# BeagleBone_Blue_3D.net
KiCad netlist of a schematic drawn in EAGLE
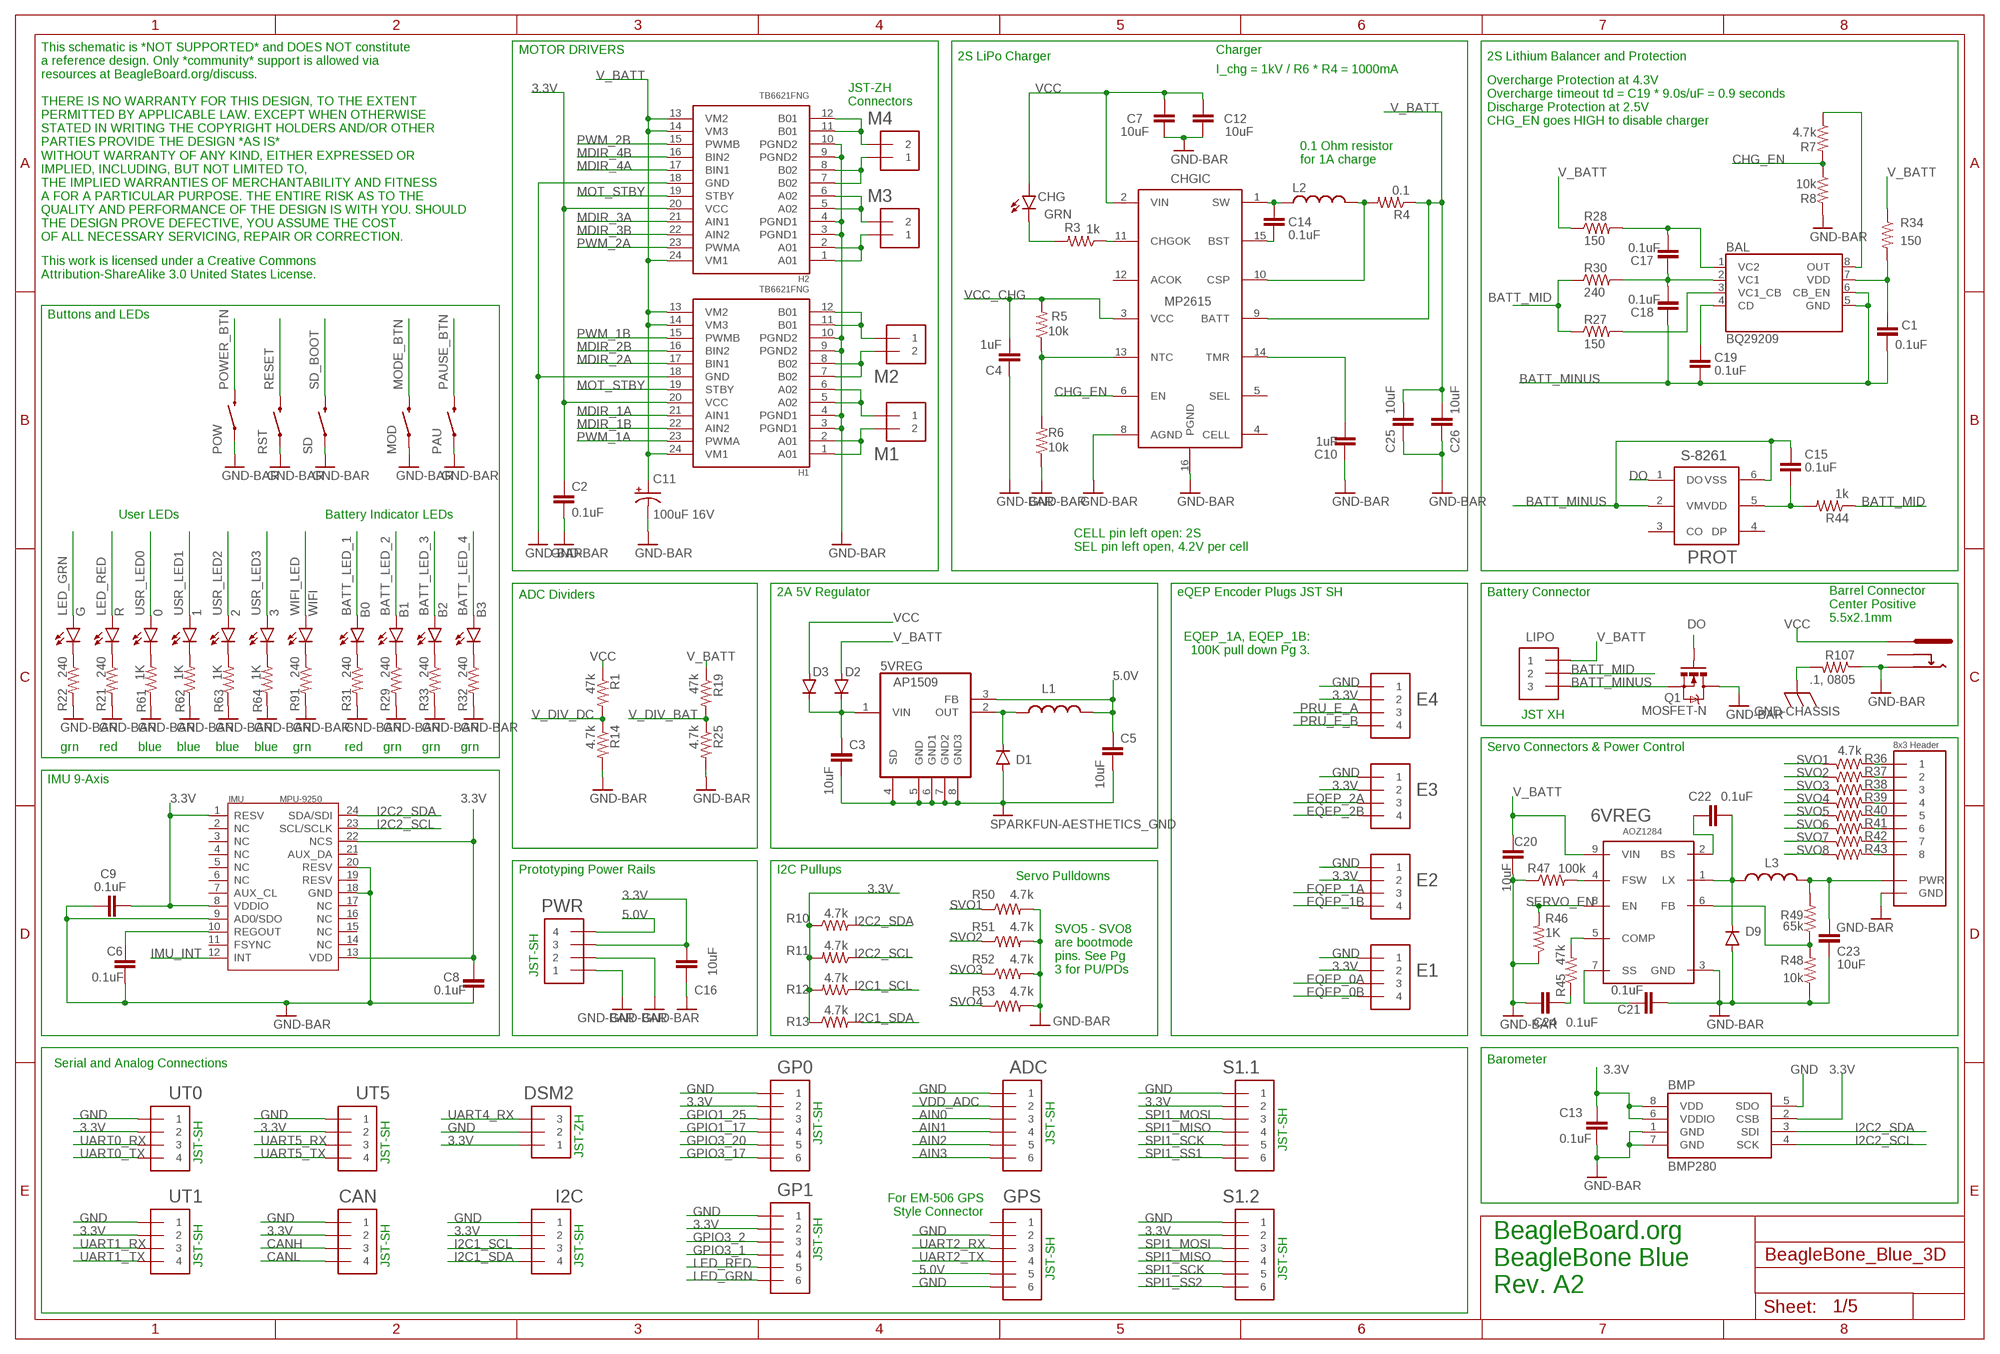
[diagram p0: schematic, sheet 1]
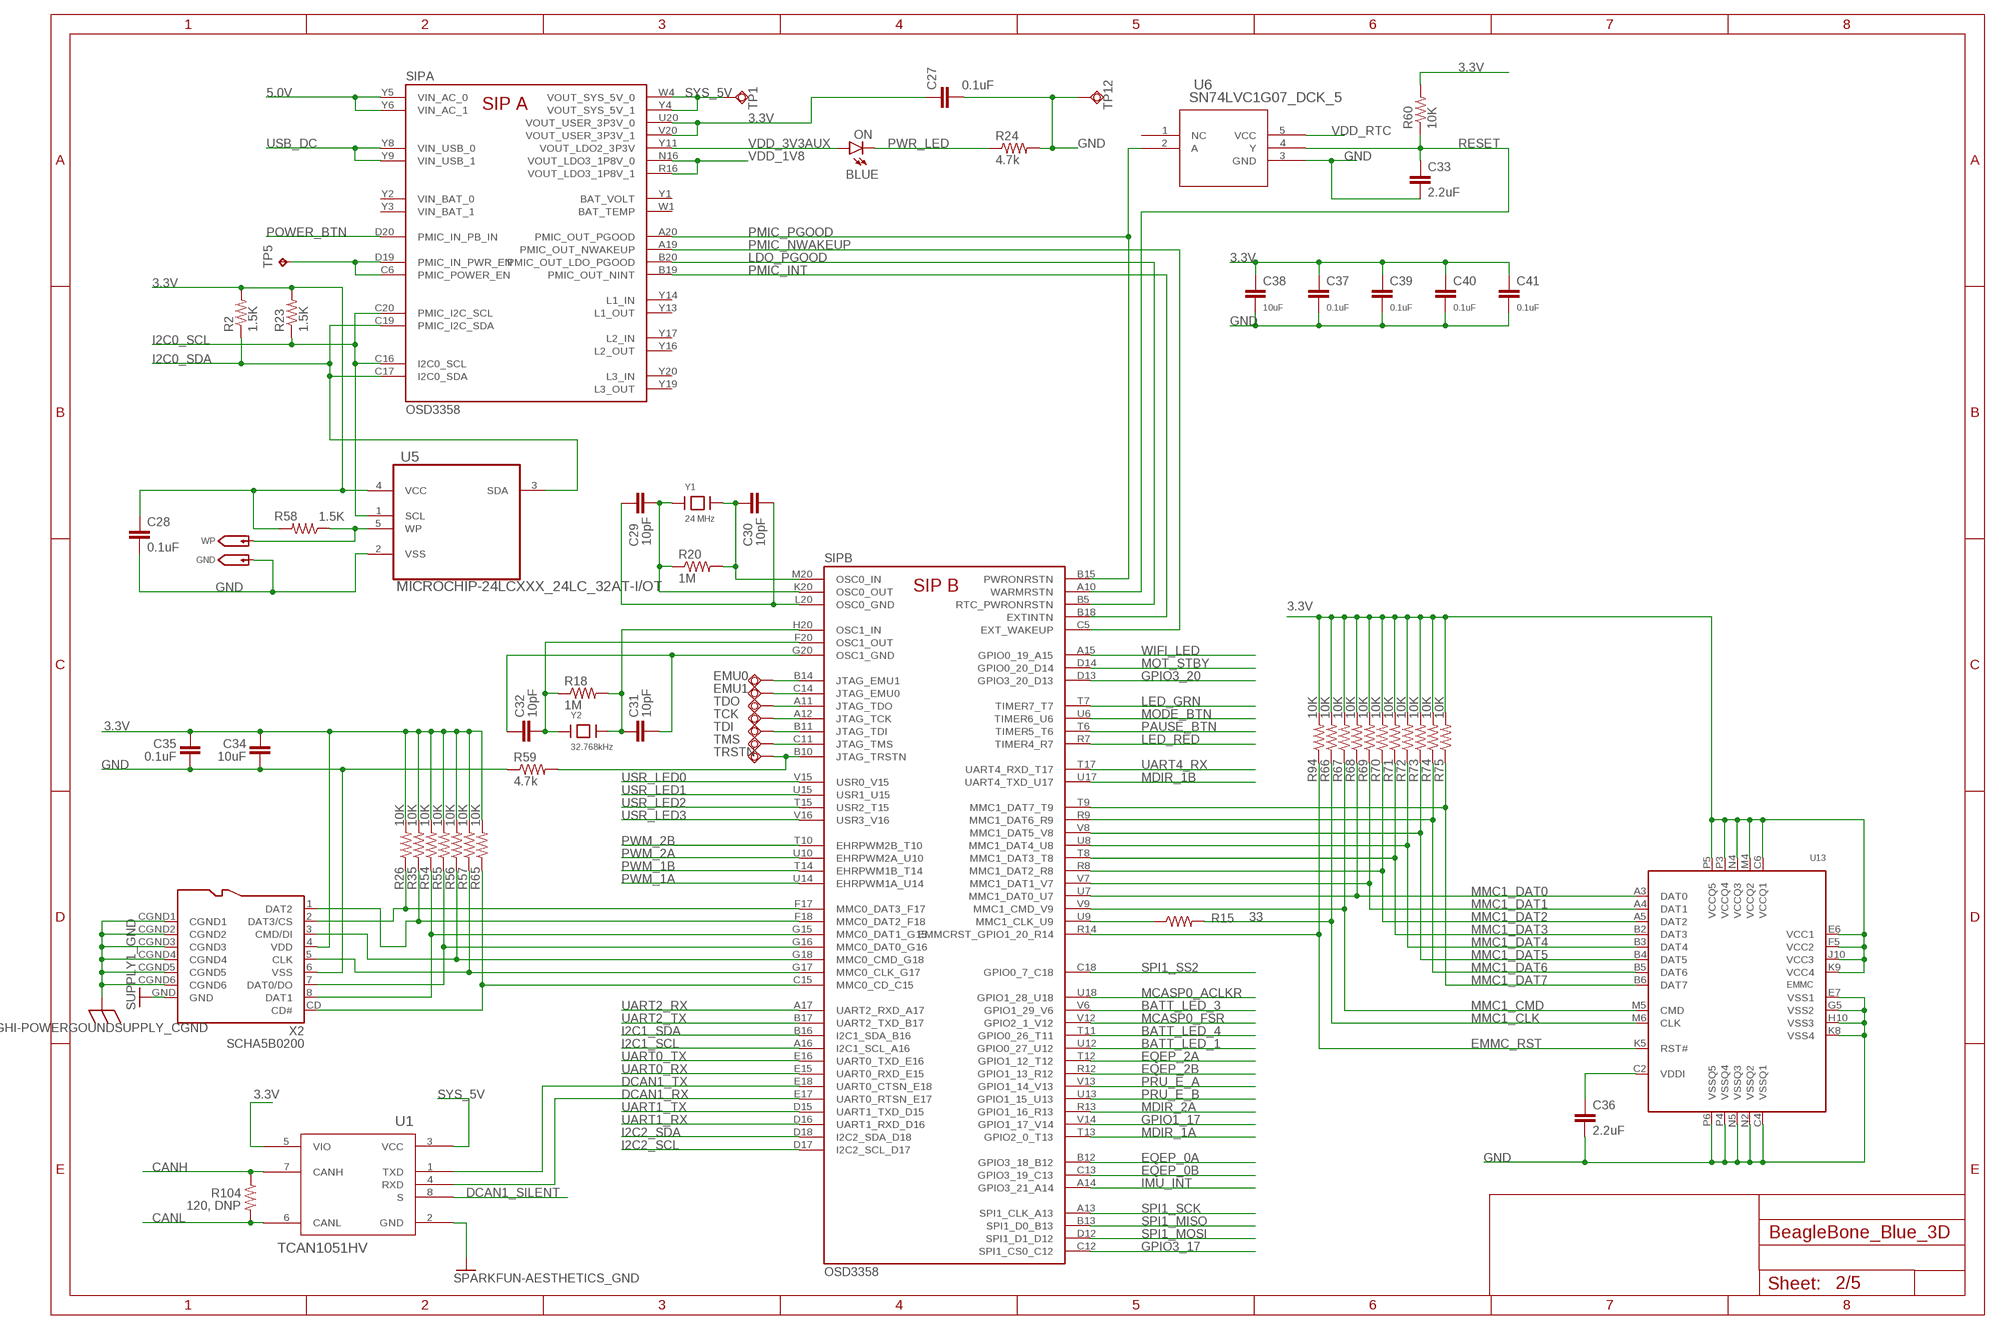
[diagram p1: schematic, sheet 2]
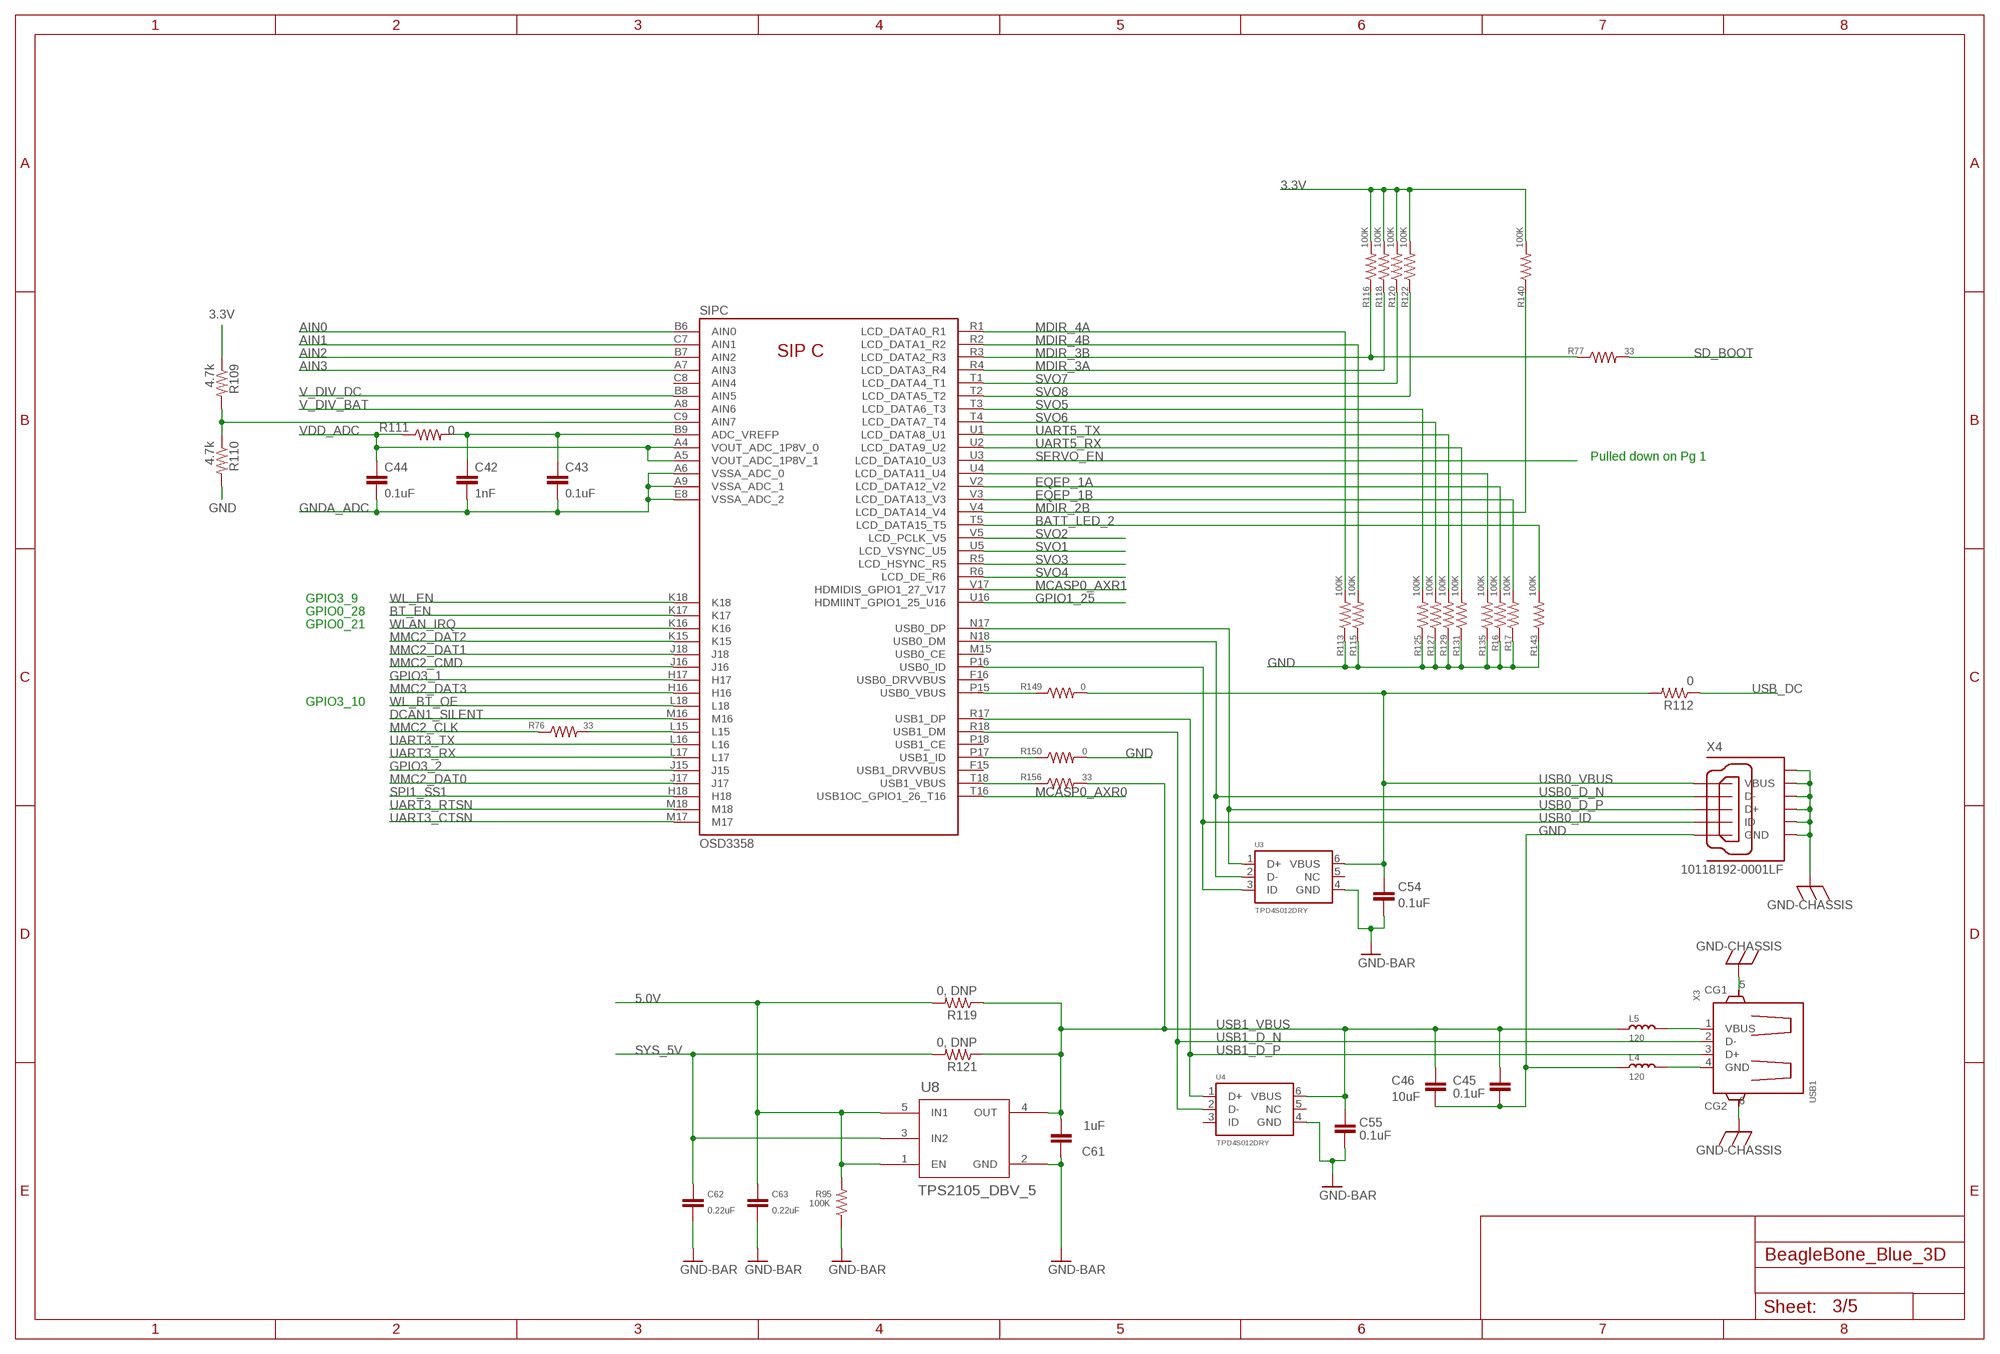
[diagram p2: schematic, sheet 3]
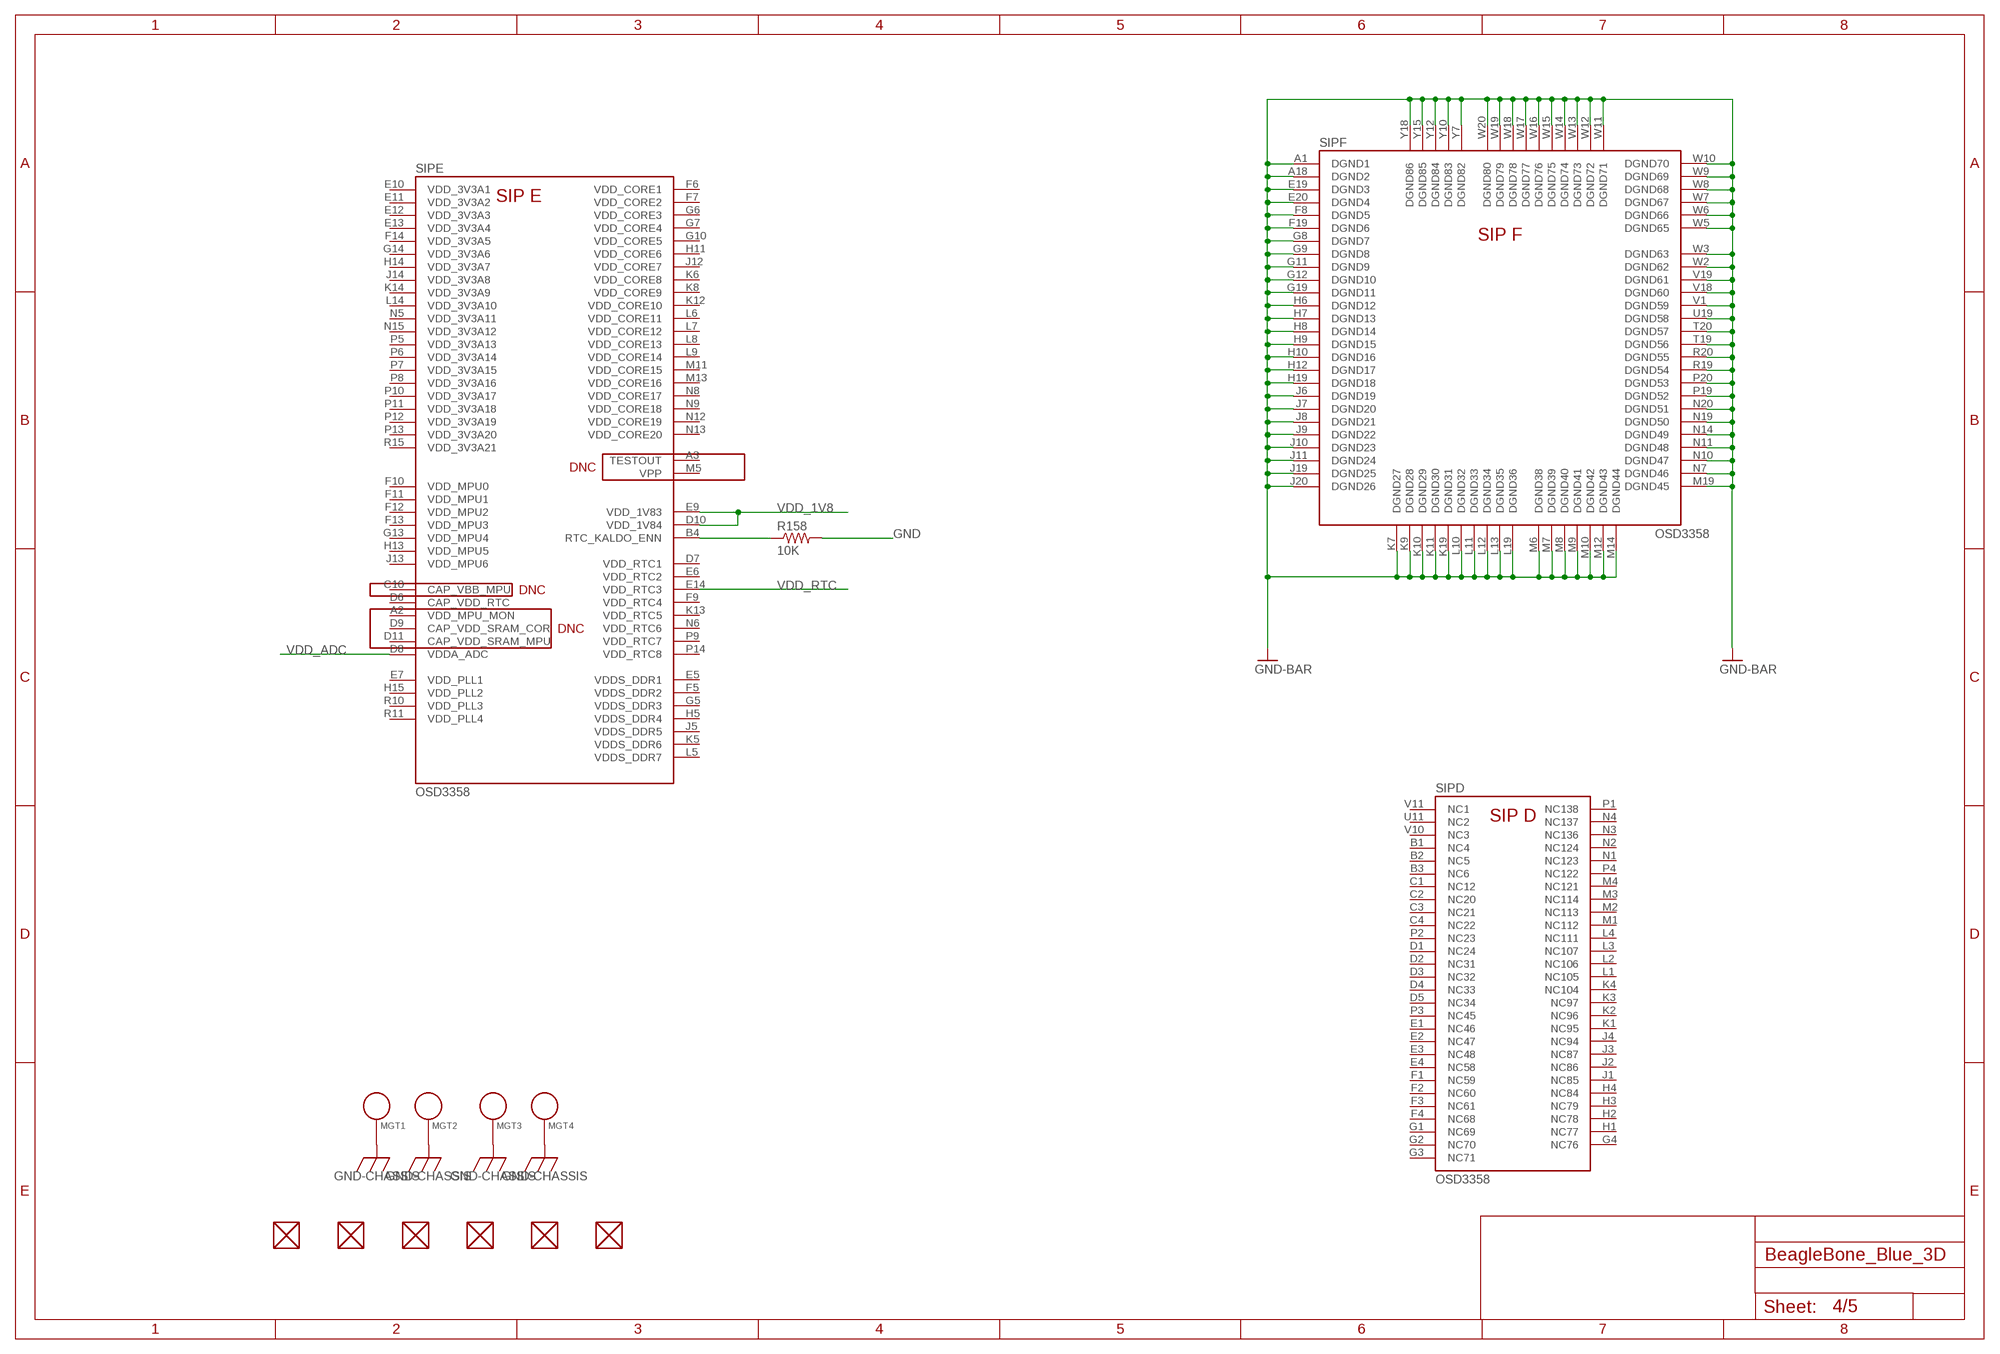
[diagram p3: schematic, sheet 4]
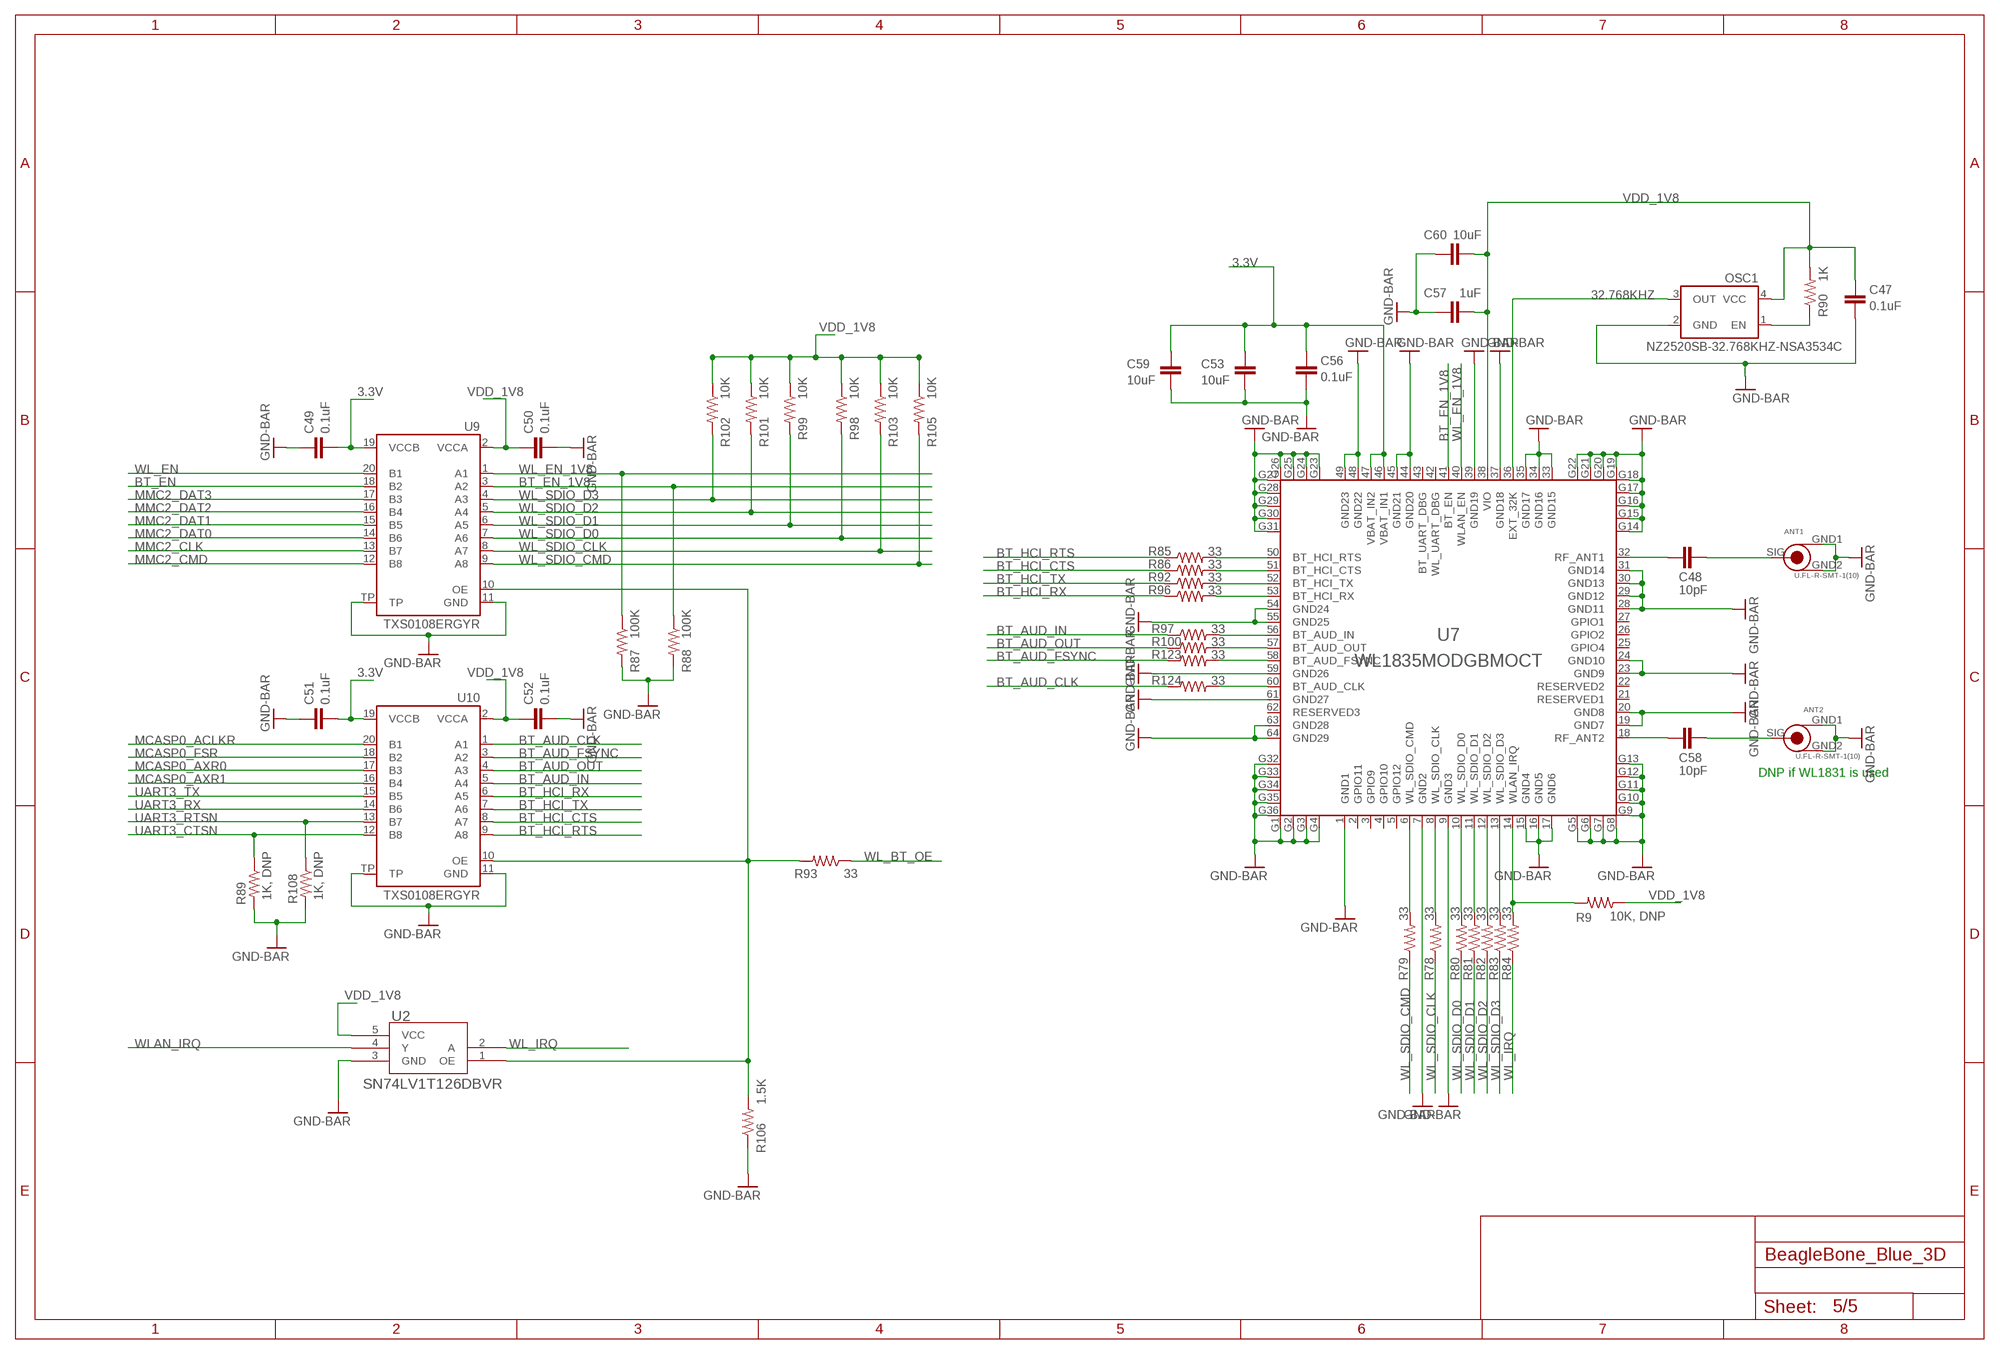
[diagram p4: schematic, sheet 5]

(export (version "E")
  (design (tool "Eeschema 10.0.6"))
  (components
    (comp (ref "FUD1")
      (value "FIDUCIAL")
      (footprint "eagle-import:GHI_FIDUCIAL_40MIL")
      (libsource (lib "eagle-import") (part "FIDUCIAL"))
    )
    (comp (ref "FUD2")
      (value "FIDUCIAL")
      (footprint "eagle-import:GHI_FIDUCIAL_40MIL")
      (libsource (lib "eagle-import") (part "FIDUCIAL"))
    )
    (comp (ref "FUD3")
      (value "FIDUCIAL")
      (footprint "eagle-import:GHI_FIDUCIAL_40MIL")
      (libsource (lib "eagle-import") (part "FIDUCIAL"))
    )
    (comp (ref "FUD4")
      (value "FIDUCIAL")
      (footprint "eagle-import:GHI_FIDUCIAL_40MIL")
      (libsource (lib "eagle-import") (part "FIDUCIAL"))
    )
    (comp (ref "FUD5")
      (value "FIDUCIAL")
      (footprint "eagle-import:GHI_FIDUCIAL_40MIL")
      (libsource (lib "eagle-import") (part "FIDUCIAL"))
    )
    (comp (ref "FUD6")
      (value "FIDUCIAL")
      (footprint "eagle-import:GHI_FIDUCIAL_40MIL")
      (libsource (lib "eagle-import") (part "FIDUCIAL"))
    )
    (comp (ref "MGT1")
      (value "MOUNTING_HOLE")
      (footprint "eagle-import:BEAGLEBONEBLACK_MOUNTING_HOLE")
      (libsource (lib "eagle-import") (part "MOUNTING_HOLE"))
    )
    (comp (ref "MGT2")
      (value "MOUNTING_HOLE")
      (footprint "eagle-import:BEAGLEBONEBLACK_MOUNTING_HOLE")
      (libsource (lib "eagle-import") (part "MOUNTING_HOLE"))
    )
    (comp (ref "MGT3")
      (value "MOUNTING_HOLE")
      (footprint "eagle-import:BEAGLEBONEBLACK_MOUNTING_HOLE")
      (libsource (lib "eagle-import") (part "MOUNTING_HOLE"))
    )
    (comp (ref "MGT4")
      (value "MOUNTING_HOLE")
      (footprint "eagle-import:BEAGLEBONEBLACK_MOUNTING_HOLE")
      (libsource (lib "eagle-import") (part "MOUNTING_HOLE"))
    )
    (comp (ref "R158")
      (value "10K")
      (footprint "eagle-import:0402-RES")
      (libsource (lib "eagle-import") (part "RESISTOR0402"))
    )
    (comp (ref "SIP")
      (value "OSD3358")
      (footprint "eagle-import:OSD3358")
      (libsource (lib "eagle-import") (part "OSD3358"))
    )
    (comp (ref "ANT1")
      (value "U.FL-R-SMT-1(10)")
      (footprint "eagle-import:GHI-CONNECTORS_U.FL-R-SMT-1")
      (libsource (lib "eagle-import") (part "U.FL-R-SMT-1"))
    )
    (comp (ref "ANT2")
      (value "U.FL-R-SMT-1(10)")
      (footprint "eagle-import:GHI-CONNECTORS_U.FL-R-SMT-1")
      (libsource (lib "eagle-import") (part "U.FL-R-SMT-1"))
    )
    (comp (ref "C47")
      (value "0.1uF")
      (footprint "eagle-import:0402-CAP")
      (libsource (lib "eagle-import") (part "CAPACITOR-N0402"))
    )
    (comp (ref "C48")
      (value "10pF")
      (footprint "eagle-import:0402-CAP")
      (libsource (lib "eagle-import") (part "CAPACITOR-N0402"))
    )
    (comp (ref "C49")
      (value "0.1uF")
      (footprint "eagle-import:0402-CAP")
      (libsource (lib "eagle-import") (part "CAPACITOR-N0402"))
    )
    (comp (ref "C50")
      (value "0.1uF")
      (footprint "eagle-import:0402-CAP")
      (libsource (lib "eagle-import") (part "CAPACITOR-N0402"))
    )
    (comp (ref "C51")
      (value "0.1uF")
      (footprint "eagle-import:0402-CAP")
      (libsource (lib "eagle-import") (part "CAPACITOR-N0402"))
    )
    (comp (ref "C52")
      (value "0.1uF")
      (footprint "eagle-import:0402-CAP")
      (libsource (lib "eagle-import") (part "CAPACITOR-N0402"))
    )
    (comp (ref "C53")
      (value "10uF")
      (footprint "eagle-import:0805")
      (libsource (lib "eagle-import") (part "CAPACITOR-N0805"))
    )
    (comp (ref "C56")
      (value "0.1uF")
      (footprint "eagle-import:0402-CAP")
      (libsource (lib "eagle-import") (part "CAPACITOR-N0402"))
    )
    (comp (ref "C57")
      (value "1uF")
      (footprint "eagle-import:0402-CAP")
      (libsource (lib "eagle-import") (part "CAPACITOR-N0402"))
    )
    (comp (ref "C58")
      (value "10pF")
      (footprint "eagle-import:0402-CAP")
      (libsource (lib "eagle-import") (part "CAPACITOR-N0402"))
    )
    (comp (ref "C59")
      (value "10uF")
      (footprint "eagle-import:0805")
      (libsource (lib "eagle-import") (part "CAPACITOR-N0805"))
    )
    (comp (ref "C60")
      (value "10uF")
      (footprint "eagle-import:0805")
      (libsource (lib "eagle-import") (part "CAPACITOR-N0805"))
    )
    (comp (ref "OSC1")
      (value "NZ2520SB-32.768KHZ-NSA3534C")
      (footprint "eagle-import:NZ2520S")
      (libsource (lib "eagle-import") (part "OSCILLATOR"))
    )
    (comp (ref "R9")
      (value "10K, DNP")
      (footprint "eagle-import:0402-RES")
      (libsource (lib "eagle-import") (part "RESISTOR0402"))
    )
    (comp (ref "R78")
      (value "33")
      (footprint "eagle-import:0402-RES")
      (libsource (lib "eagle-import") (part "RESISTOR0402"))
    )
    (comp (ref "R79")
      (value "33")
      (footprint "eagle-import:0402-RES")
      (libsource (lib "eagle-import") (part "RESISTOR0402"))
    )
    (comp (ref "R80")
      (value "33")
      (footprint "eagle-import:0402-RES")
      (libsource (lib "eagle-import") (part "RESISTOR0402"))
    )
    (comp (ref "R81")
      (value "33")
      (footprint "eagle-import:0402-RES")
      (libsource (lib "eagle-import") (part "RESISTOR0402"))
    )
    (comp (ref "R82")
      (value "33")
      (footprint "eagle-import:0402-RES")
      (libsource (lib "eagle-import") (part "RESISTOR0402"))
    )
    (comp (ref "R83")
      (value "33")
      (footprint "eagle-import:0402-RES")
      (libsource (lib "eagle-import") (part "RESISTOR0402"))
    )
    (comp (ref "R84")
      (value "33")
      (footprint "eagle-import:0402-RES")
      (libsource (lib "eagle-import") (part "RESISTOR0402"))
    )
    (comp (ref "R85")
      (value "33")
      (footprint "eagle-import:0402-RES")
      (libsource (lib "eagle-import") (part "RESISTOR0402"))
    )
    (comp (ref "R86")
      (value "33")
      (footprint "eagle-import:0402-RES")
      (libsource (lib "eagle-import") (part "RESISTOR0402"))
    )
    (comp (ref "R87")
      (value "100K")
      (footprint "eagle-import:0402-RES")
      (libsource (lib "eagle-import") (part "RESISTOR0402"))
    )
    (comp (ref "R88")
      (value "100K")
      (footprint "eagle-import:0402-RES")
      (libsource (lib "eagle-import") (part "RESISTOR0402"))
    )
    (comp (ref "R89")
      (value "1K, DNP")
      (footprint "eagle-import:0402-RES")
      (libsource (lib "eagle-import") (part "RESISTOR0402"))
    )
    (comp (ref "R90")
      (value "1K")
      (footprint "eagle-import:0402-RES")
      (libsource (lib "eagle-import") (part "RESISTOR0402"))
    )
    (comp (ref "R92")
      (value "33")
      (footprint "eagle-import:0402-RES")
      (libsource (lib "eagle-import") (part "RESISTOR0402"))
    )
    (comp (ref "R93")
      (value "33")
      (footprint "eagle-import:0402-RES")
      (libsource (lib "eagle-import") (part "RESISTOR0402"))
    )
    (comp (ref "R96")
      (value "33")
      (footprint "eagle-import:0402-RES")
      (libsource (lib "eagle-import") (part "RESISTOR0402"))
    )
    (comp (ref "R97")
      (value "33")
      (footprint "eagle-import:0402-RES")
      (libsource (lib "eagle-import") (part "RESISTOR0402"))
    )
    (comp (ref "R98")
      (value "10K")
      (footprint "eagle-import:0402-RES")
      (libsource (lib "eagle-import") (part "RESISTOR0402"))
    )
    (comp (ref "R99")
      (value "10K")
      (footprint "eagle-import:0402-RES")
      (libsource (lib "eagle-import") (part "RESISTOR0402"))
    )
    (comp (ref "R100")
      (value "33")
      (footprint "eagle-import:0402-RES")
      (libsource (lib "eagle-import") (part "RESISTOR0402"))
    )
    (comp (ref "R101")
      (value "10K")
      (footprint "eagle-import:0402-RES")
      (libsource (lib "eagle-import") (part "RESISTOR0402"))
    )
    (comp (ref "R102")
      (value "10K")
      (footprint "eagle-import:0402-RES")
      (libsource (lib "eagle-import") (part "RESISTOR0402"))
    )
    (comp (ref "R103")
      (value "10K")
      (footprint "eagle-import:0402-RES")
      (libsource (lib "eagle-import") (part "RESISTOR0402"))
    )
    (comp (ref "R105")
      (value "10K")
      (footprint "eagle-import:0402-RES")
      (libsource (lib "eagle-import") (part "RESISTOR0402"))
    )
    (comp (ref "R106")
      (value "1.5K")
      (footprint "eagle-import:0402-RES")
      (libsource (lib "eagle-import") (part "RESISTOR0402"))
    )
    (comp (ref "R108")
      (value "1K, DNP")
      (footprint "eagle-import:0402-RES")
      (libsource (lib "eagle-import") (part "RESISTOR0402"))
    )
    (comp (ref "R123")
      (value "33")
      (footprint "eagle-import:0402-RES")
      (libsource (lib "eagle-import") (part "RESISTOR0402"))
    )
    (comp (ref "R124")
      (value "33")
      (footprint "eagle-import:0402-RES")
      (libsource (lib "eagle-import") (part "RESISTOR0402"))
    )
    (comp (ref "U2")
      (value "SN74LV1T126DBVR")
      (footprint "eagle-import:SOT95P280X145-5")
      (libsource (lib "eagle-import") (part "SN74LV1T126DBVR"))
    )
    (comp (ref "U7")
      (value "WL1835MODGBMOCT")
      (footprint "eagle-import:MOC-100(TI)")
      (libsource (lib "eagle-import") (part "WL1835MOD"))
    )
    (comp (ref "U9")
      (value "TXS0108ERGYR")
      (footprint "eagle-import:R-PVQFN-N20(TI)")
      (libsource (lib "eagle-import") (part "TXS0108ERGYR"))
    )
    (comp (ref "U10")
      (value "TXS0108ERGYR")
      (footprint "eagle-import:R-PVQFN-N20(TI)")
      (libsource (lib "eagle-import") (part "TXS0108ERGYR"))
    )
    (comp (ref "C42")
      (value "1nF")
      (footprint "eagle-import:0402-CAP")
      (libsource (lib "eagle-import") (part "CAPACITOR-N0402"))
    )
    (comp (ref "C43")
      (value "0.1uF")
      (footprint "eagle-import:0402-CAP")
      (libsource (lib "eagle-import") (part "CAPACITOR-N0402"))
    )
    (comp (ref "C44")
      (value "0.1uF")
      (footprint "eagle-import:0402-CAP")
      (libsource (lib "eagle-import") (part "CAPACITOR-N0402"))
    )
    (comp (ref "C45")
      (value "0.1uF")
      (footprint "eagle-import:0402-CAP")
      (libsource (lib "eagle-import") (part "CAPACITOR-N0402"))
    )
    (comp (ref "C46")
      (value "10uF")
      (footprint "eagle-import:0805")
      (libsource (lib "eagle-import") (part "CAPACITOR-N0805"))
    )
    (comp (ref "C54")
      (value "0.1uF")
      (footprint "eagle-import:0402-CAP")
      (libsource (lib "eagle-import") (part "CAPACITOR-N0402"))
    )
    (comp (ref "C55")
      (value "0.1uF")
      (footprint "eagle-import:0402-CAP")
      (libsource (lib "eagle-import") (part "CAPACITOR-N0402"))
    )
    (comp (ref "C61")
      (value "1uF")
      (footprint "eagle-import:0402-CAP")
      (libsource (lib "eagle-import") (part "CAPACITOR-N0402"))
    )
    (comp (ref "C62")
      (value "0.22uF")
      (footprint "eagle-import:0402-CAP")
      (libsource (lib "eagle-import") (part "CAPACITOR-N0402"))
    )
    (comp (ref "C63")
      (value "0.22uF")
      (footprint "eagle-import:0402-CAP")
      (libsource (lib "eagle-import") (part "CAPACITOR-N0402"))
    )
    (comp (ref "L4")
      (value "120")
      (footprint "eagle-import:INDUCTOR_L0603")
      (libsource (lib "eagle-import") (part "INDUCTOR/FERRITE-BEAD0603"))
    )
    (comp (ref "L5")
      (value "120")
      (footprint "eagle-import:INDUCTOR_L0603")
      (libsource (lib "eagle-import") (part "INDUCTOR/FERRITE-BEAD0603"))
    )
    (comp (ref "R16")
      (value "100K")
      (footprint "eagle-import:0402-RES")
      (libsource (lib "eagle-import") (part "RESISTOR0402"))
    )
    (comp (ref "R17")
      (value "100K")
      (footprint "eagle-import:0402-RES")
      (libsource (lib "eagle-import") (part "RESISTOR0402"))
    )
    (comp (ref "R76")
      (value "33")
      (footprint "eagle-import:0402-RES")
      (libsource (lib "eagle-import") (part "RESISTOR0402"))
    )
    (comp (ref "R77")
      (value "33")
      (footprint "eagle-import:0402-RES")
      (libsource (lib "eagle-import") (part "RESISTOR0402"))
    )
    (comp (ref "R95")
      (value "100K")
      (footprint "eagle-import:0402-RES")
      (libsource (lib "eagle-import") (part "RESISTOR0402"))
    )
    (comp (ref "R109")
      (value "4.7k")
      (footprint "eagle-import:0402-RES")
      (libsource (lib "eagle-import") (part "RESISTOR0402"))
    )
    (comp (ref "R110")
      (value "4.7k")
      (footprint "eagle-import:0402-RES")
      (libsource (lib "eagle-import") (part "RESISTOR0402"))
    )
    (comp (ref "R111")
      (value "0")
      (footprint "eagle-import:0402-RES")
      (libsource (lib "eagle-import") (part "RESISTOR0402"))
    )
    (comp (ref "R112")
      (value "0")
      (footprint "eagle-import:R0603")
      (libsource (lib "eagle-import") (part "RESISTOR0603"))
    )
    (comp (ref "R113")
      (value "100K")
      (footprint "eagle-import:0402-RES")
      (libsource (lib "eagle-import") (part "RESISTOR0402"))
    )
    (comp (ref "R115")
      (value "100K")
      (footprint "eagle-import:0402-RES")
      (libsource (lib "eagle-import") (part "RESISTOR0402"))
    )
    (comp (ref "R116")
      (value "100K")
      (footprint "eagle-import:0402-RES")
      (libsource (lib "eagle-import") (part "RESISTOR0402"))
    )
    (comp (ref "R118")
      (value "100K")
      (footprint "eagle-import:0402-RES")
      (libsource (lib "eagle-import") (part "RESISTOR0402"))
    )
    (comp (ref "R119")
      (value "0, DNP")
      (footprint "eagle-import:R0603")
      (libsource (lib "eagle-import") (part "RESISTOR0603"))
    )
    (comp (ref "R120")
      (value "100K")
      (footprint "eagle-import:0402-RES")
      (libsource (lib "eagle-import") (part "RESISTOR0402"))
    )
    (comp (ref "R121")
      (value "0, DNP")
      (footprint "eagle-import:R0603")
      (libsource (lib "eagle-import") (part "RESISTOR0603"))
    )
    (comp (ref "R122")
      (value "100K")
      (footprint "eagle-import:0402-RES")
      (libsource (lib "eagle-import") (part "RESISTOR0402"))
    )
    (comp (ref "R125")
      (value "100K")
      (footprint "eagle-import:0402-RES")
      (libsource (lib "eagle-import") (part "RESISTOR0402"))
    )
    (comp (ref "R127")
      (value "100K")
      (footprint "eagle-import:0402-RES")
      (libsource (lib "eagle-import") (part "RESISTOR0402"))
    )
    (comp (ref "R129")
      (value "100K")
      (footprint "eagle-import:0402-RES")
      (libsource (lib "eagle-import") (part "RESISTOR0402"))
    )
    (comp (ref "R131")
      (value "100K")
      (footprint "eagle-import:0402-RES")
      (libsource (lib "eagle-import") (part "RESISTOR0402"))
    )
    (comp (ref "R135")
      (value "100K")
      (footprint "eagle-import:0402-RES")
      (libsource (lib "eagle-import") (part "RESISTOR0402"))
    )
    (comp (ref "R140")
      (value "100K")
      (footprint "eagle-import:0402-RES")
      (libsource (lib "eagle-import") (part "RESISTOR0402"))
    )
    (comp (ref "R143")
      (value "100K")
      (footprint "eagle-import:0402-RES")
      (libsource (lib "eagle-import") (part "RESISTOR0402"))
    )
    (comp (ref "R149")
      (value "0")
      (footprint "eagle-import:0402-RES")
      (libsource (lib "eagle-import") (part "RESISTOR0402"))
    )
    (comp (ref "R150")
      (value "0")
      (footprint "eagle-import:0402-RES")
      (libsource (lib "eagle-import") (part "RESISTOR0402"))
    )
    (comp (ref "R156")
      (value "33")
      (footprint "eagle-import:0402-RES")
      (libsource (lib "eagle-import") (part "RESISTOR0402"))
    )
    (comp (ref "U3")
      (value "TPD4S012DRY")
      (footprint "eagle-import:SON-6(TI)-DRY")
      (libsource (lib "eagle-import") (part "TPD4S012DRYR"))
    )
    (comp (ref "U4")
      (value "TPD4S012DRY")
      (footprint "eagle-import:SON-6(TI)-DRY")
      (libsource (lib "eagle-import") (part "TPD4S012DRYR"))
    )
    (comp (ref "U8")
      (value "TPS2105_DBV_5")
      (footprint "eagle-import:DIODE_DBV5")
      (fields
        (field (name "GENERIC_PART_NUMBER") "TPS2105")
        (field (name "MANUFACTURER") "Texas Instruments")
        (field (name "MANUFACTURER_PART_NUMBER") "tps2105_dbv_5")
      )
      (libsource (lib "eagle-import") (part "TPS2105_DBV_5"))
    )
    (comp (ref "X3")
      (value "USB1")
      (footprint "eagle-import:GHI2_USB_HOST_HORIZONTAL_W_CHASSIS_GND")
      (libsource (lib "eagle-import") (part "USB_HOST_W/CHASSIS_GND"))
    )
    (comp (ref "X4")
      (value "10118192-0001LF")
      (footprint "eagle-import:GHI-CONNECTORS_10118192-0001LF(MICRO-USB-B-AMPHENOL-FCI)")
      (libsource (lib "eagle-import") (part "10118192-0001LF"))
    )
    (comp (ref "C27")
      (value "0.1uF")
      (footprint "eagle-import:0402-CAP")
      (libsource (lib "eagle-import") (part "CAPACITOR-N0402"))
    )
    (comp (ref "C28")
      (value "0.1uF")
      (footprint "eagle-import:0402-CAP")
      (libsource (lib "eagle-import") (part "CAPACITOR-N0402"))
    )
    (comp (ref "C29")
      (value "10pF")
      (footprint "eagle-import:0402-CAP")
      (libsource (lib "eagle-import") (part "CAPACITOR-N0402"))
    )
    (comp (ref "C30")
      (value "10pF")
      (footprint "eagle-import:0402-CAP")
      (libsource (lib "eagle-import") (part "CAPACITOR-N0402"))
    )
    (comp (ref "C31")
      (value "10pF")
      (footprint "eagle-import:0402-CAP")
      (libsource (lib "eagle-import") (part "CAPACITOR-N0402"))
    )
    (comp (ref "C32")
      (value "10pF")
      (footprint "eagle-import:0402-CAP")
      (libsource (lib "eagle-import") (part "CAPACITOR-N0402"))
    )
    (comp (ref "C33")
      (value "2.2uF")
      (footprint "eagle-import:0402-CAP")
      (libsource (lib "eagle-import") (part "CAPACITOR-N0402"))
    )
    (comp (ref "C34")
      (value "10uF")
      (footprint "eagle-import:0805")
      (libsource (lib "eagle-import") (part "CAPACITOR-N0805"))
    )
    (comp (ref "C35")
      (value "0.1uF")
      (footprint "eagle-import:0402-CAP")
      (libsource (lib "eagle-import") (part "CAPACITOR-N0402"))
    )
    (comp (ref "C36")
      (value "2.2uF")
      (footprint "eagle-import:0402-CAP")
      (libsource (lib "eagle-import") (part "CAPACITOR-N0402"))
    )
    (comp (ref "C37")
      (value "0.1uF")
      (footprint "eagle-import:0402-CAP")
      (libsource (lib "eagle-import") (part "CAPACITOR-N0402"))
    )
    (comp (ref "C38")
      (value "10uF")
      (footprint "eagle-import:0805")
      (libsource (lib "eagle-import") (part "CAPACITOR-N0805"))
    )
    (comp (ref "C39")
      (value "0.1uF")
      (footprint "eagle-import:0402-CAP")
      (libsource (lib "eagle-import") (part "CAPACITOR-N0402"))
    )
    (comp (ref "C40")
      (value "0.1uF")
      (footprint "eagle-import:0402-CAP")
      (libsource (lib "eagle-import") (part "CAPACITOR-N0402"))
    )
    (comp (ref "C41")
      (value "0.1uF")
      (footprint "eagle-import:0402-CAP")
      (libsource (lib "eagle-import") (part "CAPACITOR-N0402"))
    )
    (comp (ref "EMU0")
      (value "TESTPAD_TPSQB1,27")
      (footprint "eagle-import:TESTPAD_B1,27")
      (libsource (lib "eagle-import") (part "TESTPAD_TPSQB1,27"))
    )
    (comp (ref "EMU1")
      (value "TESTPAD_TPSQB1,27")
      (footprint "eagle-import:TESTPAD_B1,27")
      (libsource (lib "eagle-import") (part "TESTPAD_TPSQB1,27"))
    )
    (comp (ref "GND")
      (value "TESTPAD/W_HOLE_1X1")
      (footprint "eagle-import:DIODE_GHI2_TESTPAD_W_HOLE_1X1")
      (libsource (lib "eagle-import") (part "TESTPAD/W_HOLE_1X1"))
    )
    (comp (ref "ON")
      (value "BLUE")
      (footprint "eagle-import:BEAGLEBONE_BLUE_BEAGLEBONE_BLUE_LED-0603")
      (libsource (lib "eagle-import") (part "BEAGLEBONE_BLUE_LED0603"))
    )
    (comp (ref "R2")
      (value "1.5K")
      (footprint "eagle-import:0402-RES")
      (libsource (lib "eagle-import") (part "RESISTOR0402"))
    )
    (comp (ref "R15")
      (value "33")
      (footprint "eagle-import:0402-RES")
      (libsource (lib "eagle-import") (part "RESISTOR0402"))
    )
    (comp (ref "R18")
      (value "1M")
      (footprint "eagle-import:0402-RES")
      (libsource (lib "eagle-import") (part "RESISTOR0402"))
    )
    (comp (ref "R20")
      (value "1M")
      (footprint "eagle-import:0402-RES")
      (libsource (lib "eagle-import") (part "RESISTOR0402"))
    )
    (comp (ref "R23")
      (value "1.5K")
      (footprint "eagle-import:0402-RES")
      (libsource (lib "eagle-import") (part "RESISTOR0402"))
    )
    (comp (ref "R24")
      (value "4.7k")
      (footprint "eagle-import:0402-RES")
      (libsource (lib "eagle-import") (part "RESISTOR0402"))
    )
    (comp (ref "R26")
      (value "10K")
      (footprint "eagle-import:0402-RES")
      (libsource (lib "eagle-import") (part "RESISTOR0402"))
    )
    (comp (ref "R35")
      (value "10K")
      (footprint "eagle-import:0402-RES")
      (libsource (lib "eagle-import") (part "RESISTOR0402"))
    )
    (comp (ref "R54")
      (value "10K")
      (footprint "eagle-import:0402-RES")
      (libsource (lib "eagle-import") (part "RESISTOR0402"))
    )
    (comp (ref "R55")
      (value "10K")
      (footprint "eagle-import:0402-RES")
      (libsource (lib "eagle-import") (part "RESISTOR0402"))
    )
    (comp (ref "R56")
      (value "10K")
      (footprint "eagle-import:0402-RES")
      (libsource (lib "eagle-import") (part "RESISTOR0402"))
    )
    (comp (ref "R57")
      (value "10K")
      (footprint "eagle-import:0402-RES")
      (libsource (lib "eagle-import") (part "RESISTOR0402"))
    )
    (comp (ref "R58")
      (value "1.5K")
      (footprint "eagle-import:0402-RES")
      (libsource (lib "eagle-import") (part "RESISTOR0402"))
    )
    (comp (ref "R59")
      (value "4.7k")
      (footprint "eagle-import:0402-RES")
      (libsource (lib "eagle-import") (part "RESISTOR0402"))
    )
    (comp (ref "R60")
      (value "10K")
      (footprint "eagle-import:0402-RES")
      (libsource (lib "eagle-import") (part "RESISTOR0402"))
    )
    (comp (ref "R65")
      (value "10K")
      (footprint "eagle-import:0402-RES")
      (libsource (lib "eagle-import") (part "RESISTOR0402"))
    )
    (comp (ref "R66")
      (value "10K")
      (footprint "eagle-import:0402-RES")
      (libsource (lib "eagle-import") (part "RESISTOR0402"))
    )
    (comp (ref "R67")
      (value "10K")
      (footprint "eagle-import:0402-RES")
      (libsource (lib "eagle-import") (part "RESISTOR0402"))
    )
    (comp (ref "R68")
      (value "10K")
      (footprint "eagle-import:0402-RES")
      (libsource (lib "eagle-import") (part "RESISTOR0402"))
    )
    (comp (ref "R69")
      (value "10K")
      (footprint "eagle-import:0402-RES")
      (libsource (lib "eagle-import") (part "RESISTOR0402"))
    )
    (comp (ref "R70")
      (value "10K")
      (footprint "eagle-import:0402-RES")
      (libsource (lib "eagle-import") (part "RESISTOR0402"))
    )
    (comp (ref "R71")
      (value "10K")
      (footprint "eagle-import:0402-RES")
      (libsource (lib "eagle-import") (part "RESISTOR0402"))
    )
    (comp (ref "R72")
      (value "10K")
      (footprint "eagle-import:0402-RES")
      (libsource (lib "eagle-import") (part "RESISTOR0402"))
    )
    (comp (ref "R73")
      (value "10K")
      (footprint "eagle-import:0402-RES")
      (libsource (lib "eagle-import") (part "RESISTOR0402"))
    )
    (comp (ref "R74")
      (value "10K")
      (footprint "eagle-import:0402-RES")
      (libsource (lib "eagle-import") (part "RESISTOR0402"))
    )
    (comp (ref "R75")
      (value "10K")
      (footprint "eagle-import:0402-RES")
      (libsource (lib "eagle-import") (part "RESISTOR0402"))
    )
    (comp (ref "R94")
      (value "10K")
      (footprint "eagle-import:0402-RES")
      (libsource (lib "eagle-import") (part "RESISTOR0402"))
    )
    (comp (ref "R104")
      (value "120, DNP")
      (footprint "eagle-import:R0603")
      (libsource (lib "eagle-import") (part "RESISTOR0603"))
    )
    (comp (ref "TCK")
      (value "TESTPAD_TPSQB1,27")
      (footprint "eagle-import:TESTPAD_B1,27")
      (libsource (lib "eagle-import") (part "TESTPAD_TPSQB1,27"))
    )
    (comp (ref "TDI")
      (value "TESTPAD_TPSQB1,27")
      (footprint "eagle-import:TESTPAD_B1,27")
      (libsource (lib "eagle-import") (part "TESTPAD_TPSQB1,27"))
    )
    (comp (ref "TDO")
      (value "TESTPAD_TPSQB1,27")
      (footprint "eagle-import:TESTPAD_B1,27")
      (libsource (lib "eagle-import") (part "TESTPAD_TPSQB1,27"))
    )
    (comp (ref "TMS")
      (value "TESTPAD_TPSQB1,27")
      (footprint "eagle-import:TESTPAD_B1,27")
      (libsource (lib "eagle-import") (part "TESTPAD_TPSQB1,27"))
    )
    (comp (ref "TP1")
      (value "TESTPAD_TPSQB1,27")
      (footprint "eagle-import:TESTPAD_B1,27")
      (libsource (lib "eagle-import") (part "TESTPAD_TPSQB1,27"))
    )
    (comp (ref "TP5")
      (value "TPB0,65")
      (footprint "eagle-import:B0,65")
      (libsource (lib "eagle-import") (part "TPB0,65"))
    )
    (comp (ref "TP12")
      (value "TESTPAD_TPSQB1,27")
      (footprint "eagle-import:TESTPAD_B1,27")
      (libsource (lib "eagle-import") (part "TESTPAD_TPSQB1,27"))
    )
    (comp (ref "TRSTN")
      (value "TESTPAD_TPSQB1,27")
      (footprint "eagle-import:TESTPAD_B1,27")
      (libsource (lib "eagle-import") (part "TESTPAD_TPSQB1,27"))
    )
    (comp (ref "U1")
      (value "TCAN1051HV")
      (footprint "eagle-import:D8")
      (fields
        (field (name "MANUFACTURER") "Texas Instruments")
        (field (name "MANUFACTURER_PART_NUMBER") "TCAN1051HVD")
      )
      (libsource (lib "eagle-import") (part "TCAN1051HV"))
    )
    (comp (ref "U5")
      (value "MICROCHIP-24LCXXX_24LC_32AT-I/OT")
      (footprint "eagle-import:MICROCHIP-24LCXXX_SOT95P290X145-5N")
      (fields (field (name "MPN") "24LC32AT-I/OT"))
      (libsource (lib "eagle-import") (part "MICROCHIP-24LCXXX_24LC_32AT-I/OT"))
    )
    (comp (ref "U6")
      (value "SN74LVC1G07_DCK_5")
      (footprint "eagle-import:DCK5")
      (fields
        (field (name "GENERIC_PART_NUMBER") "SN74LVC1G07")
        (field (name "MANUFACTURER") "Texas Instruments")
        (field (name "MANUFACTURER_PART_NUMBER") "sn74lvc1g07_dck_5")
      )
      (libsource (lib "eagle-import") (part "SN74LVC1G07_DCK_5"))
    )
    (comp (ref "U13")
      (value "EMMC")
      (footprint "eagle-import:MICRON_EMMC_153")
      (libsource (lib "eagle-import") (part "EMMC04G-S100-B08U"))
    )
    (comp (ref "WP")
      (value "TESTPAD/W_HOLE_1X1")
      (footprint "eagle-import:DIODE_GHI2_TESTPAD_W_HOLE_1X1")
      (libsource (lib "eagle-import") (part "TESTPAD/W_HOLE_1X1"))
    )
    (comp (ref "X2")
      (value "SCHA5B0200")
      (footprint "eagle-import:GHI-CONNECTORS_SCHA5B0200")
      (libsource (lib "eagle-import") (part "SCHA5B0200(ALPS_USD)"))
    )
    (comp (ref "Y1")
      (value "24 MHz")
      (footprint "eagle-import:GHI2_CRYSTAL_5X3.2MM")
      (libsource (lib "eagle-import") (part "CRYSTAL_5X3.2MM"))
    )
    (comp (ref "Y2")
      (value "32.768kHz")
      (footprint "eagle-import:GHI2_CRYSTAL_3.2X1.5")
      (libsource (lib "eagle-import") (part "CRYSTAL_3.2X1.5"))
    )
    (comp (ref "0")
      (value "BLUE")
      (footprint "eagle-import:0603-BLUE")
      (libsource (lib "eagle-import") (part "LED-BLUE0603"))
    )
    (comp (ref "1")
      (value "BLUE")
      (footprint "eagle-import:0603-BLUE")
      (libsource (lib "eagle-import") (part "LED-BLUE0603"))
    )
    (comp (ref "2")
      (value "BLUE")
      (footprint "eagle-import:0603-BLUE")
      (libsource (lib "eagle-import") (part "LED-BLUE0603"))
    )
    (comp (ref "3")
      (value "BLUE")
      (footprint "eagle-import:0603-BLUE")
      (libsource (lib "eagle-import") (part "LED-BLUE0603"))
    )
    (comp (ref "5VREG")
      (value "AP1509SOIC-8-TIGHT")
      (footprint "eagle-import:SO08-H")
      (libsource (lib "eagle-import") (part "AP1509SOIC-8-TIGHT"))
    )
    (comp (ref "6VREG")
      (value "AOZ1284")
      (footprint "eagle-import:SO08-EXPOSED")
      (libsource (lib "eagle-import") (part "AOZ1284"))
    )
    (comp (ref "12V")
      (value "PJ-102B_POWER_CON")
      (footprint "eagle-import:GHI_PJ-102B_POWER_CON")
      (libsource (lib "eagle-import") (part "PJ-102B_POWER_CON"))
    )
    (comp (ref "ADC")
      (value "JST_SH_6")
      (footprint "eagle-import:JST_SH_6")
      (libsource (lib "eagle-import") (part "JST_SH_6"))
    )
    (comp (ref "B0")
      (value "RED")
      (footprint "eagle-import:LED-0603")
      (libsource (lib "eagle-import") (part "BLUE_LED0603"))
    )
    (comp (ref "B1")
      (value "GREEN")
      (footprint "eagle-import:LED-0603")
      (libsource (lib "eagle-import") (part "BLUE_LED0603"))
    )
    (comp (ref "B2")
      (value "GREEN")
      (footprint "eagle-import:LED-0603")
      (libsource (lib "eagle-import") (part "BLUE_LED0603"))
    )
    (comp (ref "B3")
      (value "GREEN")
      (footprint "eagle-import:LED-0603")
      (libsource (lib "eagle-import") (part "BLUE_LED0603"))
    )
    (comp (ref "BAL")
      (value "BQ29209")
      (footprint "eagle-import:8-SON_3X3MM")
      (libsource (lib "eagle-import") (part "BQ29209"))
    )
    (comp (ref "BMP")
      (value "BMP280")
      (footprint "eagle-import:BMP280")
      (libsource (lib "eagle-import") (part "BMP280"))
    )
    (comp (ref "C1")
      (value "0.1uF")
      (footprint "eagle-import:0402-CAP")
      (libsource (lib "eagle-import") (part "CAPACITOR-N0402"))
    )
    (comp (ref "C2")
      (value "0.1uF")
      (footprint "eagle-import:0402-CAP")
      (libsource (lib "eagle-import") (part "CAPACITOR-N0402"))
    )
    (comp (ref "C3")
      (value "10uF")
      (footprint "eagle-import:0805")
      (libsource (lib "eagle-import") (part "CAPACITOR-N0805"))
    )
    (comp (ref "C4")
      (value "1uF")
      (footprint "eagle-import:0402-CAP")
      (libsource (lib "eagle-import") (part "CAPACITOR-N0402"))
    )
    (comp (ref "C5")
      (value "10uF")
      (footprint "eagle-import:0805")
      (libsource (lib "eagle-import") (part "CAPACITOR-N0805"))
    )
    (comp (ref "C6")
      (value "0.1uF")
      (footprint "eagle-import:0402-CAP")
      (libsource (lib "eagle-import") (part "CAPACITOR-N0402"))
    )
    (comp (ref "C7")
      (value "10uF")
      (footprint "eagle-import:0805")
      (libsource (lib "eagle-import") (part "CAPACITOR-N0805"))
    )
    (comp (ref "C8")
      (value "0.1uF")
      (footprint "eagle-import:0402-CAP")
      (libsource (lib "eagle-import") (part "CAPACITOR-N0402"))
    )
    (comp (ref "C9")
      (value "0.1uF")
      (footprint "eagle-import:0402-CAP")
      (libsource (lib "eagle-import") (part "CAPACITOR-N0402"))
    )
    (comp (ref "C10")
      (value "1uF")
      (footprint "eagle-import:0402-CAP")
      (libsource (lib "eagle-import") (part "CAPACITOR-N0402"))
    )
    (comp (ref "C11")
      (value "100uF 16V")
      (footprint "eagle-import:PANASONIC_D")
      (libsource (lib "eagle-import") (part "CAPACITOR-PD"))
    )
    (comp (ref "C12")
      (value "10uF")
      (footprint "eagle-import:0805")
      (libsource (lib "eagle-import") (part "CAPACITOR-N0805"))
    )
    (comp (ref "C13")
      (value "0.1uF")
      (footprint "eagle-import:0402-CAP")
      (libsource (lib "eagle-import") (part "CAPACITOR-N0402"))
    )
    (comp (ref "C14")
      (value "0.1uF")
      (footprint "eagle-import:0402-CAP")
      (libsource (lib "eagle-import") (part "CAPACITOR-N0402"))
    )
    (comp (ref "C15")
      (value "0.1uF")
      (footprint "eagle-import:0402-CAP")
      (libsource (lib "eagle-import") (part "CAPACITOR-N0402"))
    )
    (comp (ref "C16")
      (value "10uF")
      (footprint "eagle-import:0805")
      (libsource (lib "eagle-import") (part "CAPACITOR-N0805"))
    )
    (comp (ref "C17")
      (value "0.1uF")
      (footprint "eagle-import:0402-CAP")
      (libsource (lib "eagle-import") (part "CAPACITOR-N0402"))
    )
    (comp (ref "C18")
      (value "0.1uF")
      (footprint "eagle-import:0402-CAP")
      (libsource (lib "eagle-import") (part "CAPACITOR-N0402"))
    )
    (comp (ref "C19")
      (value "0.1uF")
      (footprint "eagle-import:0402-CAP")
      (libsource (lib "eagle-import") (part "CAPACITOR-N0402"))
    )
    (comp (ref "C20")
      (value "10uF")
      (footprint "eagle-import:0805")
      (libsource (lib "eagle-import") (part "CAPACITOR-N0805"))
    )
    (comp (ref "C21")
      (value "0.1uF")
      (footprint "eagle-import:0402-CAP")
      (libsource (lib "eagle-import") (part "CAPACITOR-N0402"))
    )
    (comp (ref "C22")
      (value "0.1uF")
      (footprint "eagle-import:0402-CAP")
      (libsource (lib "eagle-import") (part "CAPACITOR-N0402"))
    )
    (comp (ref "C23")
      (value "10uF")
      (footprint "eagle-import:0805")
      (libsource (lib "eagle-import") (part "CAPACITOR-N0805"))
    )
    (comp (ref "C24")
      (value "0.1uF")
      (footprint "eagle-import:0402-CAP")
      (libsource (lib "eagle-import") (part "CAPACITOR-N0402"))
    )
    (comp (ref "C25")
      (value "10uF")
      (footprint "eagle-import:0805")
      (libsource (lib "eagle-import") (part "CAPACITOR-N0805"))
    )
    (comp (ref "C26")
      (value "10uF")
      (footprint "eagle-import:0805")
      (libsource (lib "eagle-import") (part "CAPACITOR-N0805"))
    )
    (comp (ref "CAN")
      (value "JST_SH_4")
      (footprint "eagle-import:JST_SH_4_SMD")
      (libsource (lib "eagle-import") (part "JST_SH_4"))
    )
    (comp (ref "CHG")
      (value "GRN")
      (footprint "eagle-import:LED-0603")
      (libsource (lib "eagle-import") (part "BLUE_LED0603"))
    )
    (comp (ref "CHGIC")
      (value "MP2615")
      (footprint "eagle-import:QFN50P300X300X100-16")
      (libsource (lib "eagle-import") (part "MP2615"))
    )
    (comp (ref "D1")
      (value "DIODEDIODE-123FL")
      (footprint "eagle-import:DIODE_SOD-123FL")
      (libsource (lib "eagle-import") (part "DIODEDIODE-123FL"))
    )
    (comp (ref "D2")
      (value "DIODEDIODE-123FL")
      (footprint "eagle-import:DIODE_SOD-123FL")
      (libsource (lib "eagle-import") (part "DIODEDIODE-123FL"))
    )
    (comp (ref "D3")
      (value "DIODEDIODE-123FL")
      (footprint "eagle-import:DIODE_SOD-123FL")
      (libsource (lib "eagle-import") (part "DIODEDIODE-123FL"))
    )
    (comp (ref "D9")
      (value "DIODEDO214AA")
      (footprint "eagle-import:DO-214AA")
      (libsource (lib "eagle-import") (part "DIODEDO214AA"))
    )
    (comp (ref "DSM2")
      (value "JST_ZH_3")
      (footprint "eagle-import:JST_ZH_3")
      (libsource (lib "eagle-import") (part "JST_ZH_3"))
    )
    (comp (ref "E1")
      (value "JST_SH_4")
      (footprint "eagle-import:JST_SH_4_SMD")
      (libsource (lib "eagle-import") (part "JST_SH_4"))
    )
    (comp (ref "E2")
      (value "JST_SH_4")
      (footprint "eagle-import:JST_SH_4_SMD")
      (libsource (lib "eagle-import") (part "JST_SH_4"))
    )
    (comp (ref "E3")
      (value "JST_SH_4")
      (footprint "eagle-import:JST_SH_4_SMD")
      (libsource (lib "eagle-import") (part "JST_SH_4"))
    )
    (comp (ref "E4")
      (value "JST_SH_4")
      (footprint "eagle-import:JST_SH_4_SMD")
      (libsource (lib "eagle-import") (part "JST_SH_4"))
    )
    (comp (ref "G")
      (value "GREEN")
      (footprint "eagle-import:0603-GREEN")
      (libsource (lib "eagle-import") (part "LED-GREEN0603"))
    )
    (comp (ref "GP0")
      (value "JST_SH_6")
      (footprint "eagle-import:JST_SH_6")
      (libsource (lib "eagle-import") (part "JST_SH_6"))
    )
    (comp (ref "GP1")
      (value "JST_SH_6")
      (footprint "eagle-import:JST_SH_6")
      (libsource (lib "eagle-import") (part "JST_SH_6"))
    )
    (comp (ref "GPS")
      (value "JST_SH_6")
      (footprint "eagle-import:JST_SH_6")
      (libsource (lib "eagle-import") (part "JST_SH_6"))
    )
    (comp (ref "H1")
      (value "TB6621FNG")
      (footprint "eagle-import:SOP65P760X140-24")
      (libsource (lib "eagle-import") (part "TB6621FNG"))
    )
    (comp (ref "H2")
      (value "TB6621FNG")
      (footprint "eagle-import:SOP65P760X140-24")
      (libsource (lib "eagle-import") (part "TB6621FNG"))
    )
    (comp (ref "I2C")
      (value "JST_SH_4")
      (footprint "eagle-import:JST_SH_4_SMD")
      (libsource (lib "eagle-import") (part "JST_SH_4"))
    )
    (comp (ref "IMU")
      (value "MPU-9250")
      (footprint "eagle-import:QFN24G-0.4-3X3MM")
      (libsource (lib "eagle-import") (part "MPU-9250"))
    )
    (comp (ref "J2")
      (value "SERVO_HEADERS_8X")
      (footprint "eagle-import:DIODE_3X8_0.1__HEADER")
      (libsource (lib "eagle-import") (part "SERVO_HEADERS_8X"))
    )
    (comp (ref "L1")
      (value "6.8uH")
      (footprint "eagle-import:SRN6045")
      (libsource (lib "eagle-import") (part "INDUCTORSRN6045"))
    )
    (comp (ref "L2")
      (value "6.8uH")
      (footprint "eagle-import:SRN6045")
      (libsource (lib "eagle-import") (part "INDUCTORSRN6045"))
    )
    (comp (ref "L3")
      (value "3.6 uH")
      (footprint "eagle-import:INDUCTOR-8X8MM")
      (libsource (lib "eagle-import") (part "INDUCTOR8X8MM"))
    )
    (comp (ref "LIPO")
      (value "BATTERY")
      (footprint "eagle-import:JST_XH_3-PIN")
      (libsource (lib "eagle-import") (part "JST_XH_3-PIN"))
    )
    (comp (ref "M1")
      (value "JST_ZH_2")
      (footprint "eagle-import:JST_ZH_2")
      (libsource (lib "eagle-import") (part "JST_ZH_2"))
    )
    (comp (ref "M2")
      (value "JST_ZH_2")
      (footprint "eagle-import:JST_ZH_2")
      (libsource (lib "eagle-import") (part "JST_ZH_2"))
    )
    (comp (ref "M3")
      (value "JST_ZH_2")
      (footprint "eagle-import:JST_ZH_2")
      (libsource (lib "eagle-import") (part "JST_ZH_2"))
    )
    (comp (ref "M4")
      (value "JST_ZH_2")
      (footprint "eagle-import:JST_ZH_2")
      (libsource (lib "eagle-import") (part "JST_ZH_2"))
    )
    (comp (ref "MOD")
      (value "RS032G05A3SM-SPST-MOMENTARY-SWSMD-1101NE")
      (footprint "eagle-import:TACTILE-SWITCH-1101NE")
      (libsource (lib "eagle-import") (part "RS032G05A3SM-SPST-MOMENTARY-SWSMD-1101NE"))
    )
    (comp (ref "PAU")
      (value "RS032G05A3SM-SPST-MOMENTARY-SWSMD-1101NE")
      (footprint "eagle-import:TACTILE-SWITCH-1101NE")
      (libsource (lib "eagle-import") (part "RS032G05A3SM-SPST-MOMENTARY-SWSMD-1101NE"))
    )
    (comp (ref "POW")
      (value "RS032G05A3SM-SPST-MOMENTARY-SWSMD-1101NE")
      (footprint "eagle-import:TACTILE-SWITCH-1101NE")
      (libsource (lib "eagle-import") (part "RS032G05A3SM-SPST-MOMENTARY-SWSMD-1101NE"))
    )
    (comp (ref "PROT")
      (value "S-8261")
      (footprint "eagle-import:SOT-236")
      (libsource (lib "eagle-import") (part "S-8261"))
    )
    (comp (ref "PWR")
      (value "JST_SH_4")
      (footprint "eagle-import:JST_SH_4_SMD")
      (libsource (lib "eagle-import") (part "JST_SH_4"))
    )
    (comp (ref "Q1")
      (value "MOSFET-N")
      (footprint "eagle-import:SO08-TIGHT")
      (libsource (lib "eagle-import") (part "MOSFET-NCHANNEL"))
    )
    (comp (ref "R")
      (value "RED")
      (footprint "eagle-import:0603-RED")
      (libsource (lib "eagle-import") (part "LED-RED0603"))
    )
    (comp (ref "R1")
      (value "47k")
      (footprint "eagle-import:0402-RES")
      (libsource (lib "eagle-import") (part "RESISTOR0402"))
    )
    (comp (ref "R3")
      (value "1k")
      (footprint "eagle-import:0402-RES")
      (libsource (lib "eagle-import") (part "RESISTOR0402"))
    )
    (comp (ref "R4")
      (value "0.1")
      (footprint "eagle-import:0402-RES")
      (libsource (lib "eagle-import") (part "RESISTOR0402"))
    )
    (comp (ref "R5")
      (value "10k")
      (footprint "eagle-import:0402-RES")
      (libsource (lib "eagle-import") (part "RESISTOR0402"))
    )
    (comp (ref "R6")
      (value "10k")
      (footprint "eagle-import:0402-RES")
      (libsource (lib "eagle-import") (part "RESISTOR0402"))
    )
    (comp (ref "R7")
      (value "4.7k")
      (footprint "eagle-import:0402-RES")
      (libsource (lib "eagle-import") (part "RESISTOR0402"))
    )
    (comp (ref "R8")
      (value "10k")
      (footprint "eagle-import:0402-RES")
      (libsource (lib "eagle-import") (part "RESISTOR0402"))
    )
    (comp (ref "R10")
      (value "4.7k")
      (footprint "eagle-import:0402-RES")
      (libsource (lib "eagle-import") (part "RESISTOR0402"))
    )
    (comp (ref "R11")
      (value "4.7k")
      (footprint "eagle-import:0402-RES")
      (libsource (lib "eagle-import") (part "RESISTOR0402"))
    )
    (comp (ref "R12")
      (value "4.7k")
      (footprint "eagle-import:0402-RES")
      (libsource (lib "eagle-import") (part "RESISTOR0402"))
    )
    (comp (ref "R13")
      (value "4.7k")
      (footprint "eagle-import:0402-RES")
      (libsource (lib "eagle-import") (part "RESISTOR0402"))
    )
    (comp (ref "R14")
      (value "4.7k")
      (footprint "eagle-import:0402-RES")
      (libsource (lib "eagle-import") (part "RESISTOR0402"))
    )
    (comp (ref "R19")
      (value "47k")
      (footprint "eagle-import:0402-RES")
      (libsource (lib "eagle-import") (part "RESISTOR0402"))
    )
    (comp (ref "R21")
      (value "240")
      (footprint "eagle-import:0402-RES")
      (libsource (lib "eagle-import") (part "RESISTOR0402"))
    )
    (comp (ref "R22")
      (value "240")
      (footprint "eagle-import:0402-RES")
      (libsource (lib "eagle-import") (part "RESISTOR0402"))
    )
    (comp (ref "R25")
      (value "4.7k")
      (footprint "eagle-import:0402-RES")
      (libsource (lib "eagle-import") (part "RESISTOR0402"))
    )
    (comp (ref "R27")
      (value "150")
      (footprint "eagle-import:0402-RES")
      (libsource (lib "eagle-import") (part "RESISTOR0402"))
    )
    (comp (ref "R28")
      (value "150")
      (footprint "eagle-import:0402-RES")
      (libsource (lib "eagle-import") (part "RESISTOR0402"))
    )
    (comp (ref "R29")
      (value "240")
      (footprint "eagle-import:0402-RES")
      (libsource (lib "eagle-import") (part "RESISTOR0402"))
    )
    (comp (ref "R30")
      (value "240")
      (footprint "eagle-import:0402-RES")
      (libsource (lib "eagle-import") (part "RESISTOR0402"))
    )
    (comp (ref "R31")
      (value "240")
      (footprint "eagle-import:0402-RES")
      (libsource (lib "eagle-import") (part "RESISTOR0402"))
    )
    (comp (ref "R32")
      (value "240")
      (footprint "eagle-import:0402-RES")
      (libsource (lib "eagle-import") (part "RESISTOR0402"))
    )
    (comp (ref "R33")
      (value "240")
      (footprint "eagle-import:0402-RES")
      (libsource (lib "eagle-import") (part "RESISTOR0402"))
    )
    (comp (ref "R34")
      (value "150")
      (footprint "eagle-import:0402-RES")
      (libsource (lib "eagle-import") (part "RESISTOR0402"))
    )
    (comp (ref "R36")
      (value "4.7k")
      (footprint "eagle-import:0402-RES")
      (libsource (lib "eagle-import") (part "RESISTOR0402"))
    )
    (comp (ref "R37")
      (value "4.7k")
      (footprint "eagle-import:0402-RES")
      (libsource (lib "eagle-import") (part "RESISTOR0402"))
    )
    (comp (ref "R38")
      (value "4.7k")
      (footprint "eagle-import:0402-RES")
      (libsource (lib "eagle-import") (part "RESISTOR0402"))
    )
    (comp (ref "R39")
      (value "4.7k")
      (footprint "eagle-import:0402-RES")
      (libsource (lib "eagle-import") (part "RESISTOR0402"))
    )
    (comp (ref "R40")
      (value "4.7k")
      (footprint "eagle-import:0402-RES")
      (libsource (lib "eagle-import") (part "RESISTOR0402"))
    )
    (comp (ref "R41")
      (value "4.7k")
      (footprint "eagle-import:0402-RES")
      (libsource (lib "eagle-import") (part "RESISTOR0402"))
    )
    (comp (ref "R42")
      (value "4.7k")
      (footprint "eagle-import:0402-RES")
      (libsource (lib "eagle-import") (part "RESISTOR0402"))
    )
    (comp (ref "R43")
      (value "4.7k")
      (footprint "eagle-import:0402-RES")
      (libsource (lib "eagle-import") (part "RESISTOR0402"))
    )
    (comp (ref "R44")
      (value "1k")
      (footprint "eagle-import:0402-RES")
      (libsource (lib "eagle-import") (part "RESISTOR0402"))
    )
    (comp (ref "R45")
      (value "47k")
      (footprint "eagle-import:0402-RES")
      (libsource (lib "eagle-import") (part "RESISTOR0402"))
    )
    (comp (ref "R46")
      (value "1K")
      (footprint "eagle-import:0402-RES")
      (libsource (lib "eagle-import") (part "RESISTOR0402"))
    )
    (comp (ref "R47")
      (value "100k")
      (footprint "eagle-import:0402-RES")
      (libsource (lib "eagle-import") (part "RESISTOR0402"))
    )
    (comp (ref "R48")
      (value "10k")
      (footprint "eagle-import:0402-RES")
      (libsource (lib "eagle-import") (part "RESISTOR0402"))
    )
    (comp (ref "R49")
      (value "65k")
      (footprint "eagle-import:0402-RES")
      (libsource (lib "eagle-import") (part "RESISTOR0402"))
    )
    (comp (ref "R50")
      (value "4.7k")
      (footprint "eagle-import:0402-RES")
      (libsource (lib "eagle-import") (part "RESISTOR0402"))
    )
    (comp (ref "R51")
      (value "4.7k")
      (footprint "eagle-import:0402-RES")
      (libsource (lib "eagle-import") (part "RESISTOR0402"))
    )
    (comp (ref "R52")
      (value "4.7k")
      (footprint "eagle-import:0402-RES")
      (libsource (lib "eagle-import") (part "RESISTOR0402"))
    )
    (comp (ref "R53")
      (value "4.7k")
      (footprint "eagle-import:0402-RES")
      (libsource (lib "eagle-import") (part "RESISTOR0402"))
    )
    (comp (ref "R61")
      (value "1K")
      (footprint "eagle-import:0402-RES")
      (libsource (lib "eagle-import") (part "RESISTOR0402"))
    )
    (comp (ref "R62")
      (value "1K")
      (footprint "eagle-import:0402-RES")
      (libsource (lib "eagle-import") (part "RESISTOR0402"))
    )
    (comp (ref "R63")
      (value "1K")
      (footprint "eagle-import:0402-RES")
      (libsource (lib "eagle-import") (part "RESISTOR0402"))
    )
    (comp (ref "R64")
      (value "1K")
      (footprint "eagle-import:0402-RES")
      (libsource (lib "eagle-import") (part "RESISTOR0402"))
    )
    (comp (ref "R91")
      (value "240")
      (footprint "eagle-import:0402-RES")
      (libsource (lib "eagle-import") (part "RESISTOR0402"))
    )
    (comp (ref "R107")
      (value ".1, 0805")
      (footprint "eagle-import:R0805")
      (libsource (lib "eagle-import") (part "RESISTOR0805"))
    )
    (comp (ref "RST")
      (value "RS032G05A3SM-SPST-MOMENTARY-SWSMD-1101NE")
      (footprint "eagle-import:TACTILE-SWITCH-1101NE")
      (libsource (lib "eagle-import") (part "RS032G05A3SM-SPST-MOMENTARY-SWSMD-1101NE"))
    )
    (comp (ref "S1.1")
      (value "JST_SH_6")
      (footprint "eagle-import:JST_SH_6")
      (libsource (lib "eagle-import") (part "JST_SH_6"))
    )
    (comp (ref "S1.2")
      (value "JST_SH_6")
      (footprint "eagle-import:JST_SH_6")
      (libsource (lib "eagle-import") (part "JST_SH_6"))
    )
    (comp (ref "SD")
      (value "RS032G05A3SM-SPST-MOMENTARY-SWSMD-1101NE")
      (footprint "eagle-import:TACTILE-SWITCH-1101NE")
      (libsource (lib "eagle-import") (part "RS032G05A3SM-SPST-MOMENTARY-SWSMD-1101NE"))
    )
    (comp (ref "UT0")
      (value "JST_SH_4")
      (footprint "eagle-import:JST_SH_4_SMD")
      (libsource (lib "eagle-import") (part "JST_SH_4"))
    )
    (comp (ref "UT1")
      (value "JST_SH_4")
      (footprint "eagle-import:JST_SH_4_SMD")
      (libsource (lib "eagle-import") (part "JST_SH_4"))
    )
    (comp (ref "UT5")
      (value "JST_SH_4")
      (footprint "eagle-import:JST_SH_4_SMD")
      (libsource (lib "eagle-import") (part "JST_SH_4"))
    )
    (comp (ref "WIFI")
      (value "GREEN")
      (footprint "eagle-import:0603-GREEN")
      (libsource (lib "eagle-import") (part "LED-GREEN0603"))
    )
  )
  (nets
    (net (code "1") (name "3.3V") (class "Default")
      (node (ref "BMP") (pin "2") (pinfunction "CSB_2") (pintype "input"))
      (node (ref "BMP") (pin "6") (pinfunction "VDDIO_6") (pintype "input"))
      (node (ref "BMP") (pin "8") (pinfunction "VDD_8") (pintype "power_in"))
      (node (ref "C13") (pin "1") (pinfunction "1_1") (pintype "passive"))
      (node (ref "C16") (pin "1") (pinfunction "1_1") (pintype "passive"))
      (node (ref "C2") (pin "2") (pinfunction "2_2") (pintype "passive"))
      (node (ref "C27") (pin "1") (pinfunction "1_1") (pintype "passive"))
      (node (ref "C28") (pin "1") (pinfunction "1_1") (pintype "passive"))
      (node (ref "C34") (pin "2") (pinfunction "2_2") (pintype "passive"))
      (node (ref "C35") (pin "2") (pinfunction "2_2") (pintype "passive"))
      (node (ref "C37") (pin "1") (pinfunction "1_1") (pintype "passive"))
      (node (ref "C38") (pin "1") (pinfunction "1_1") (pintype "passive"))
      (node (ref "C39") (pin "1") (pinfunction "1_1") (pintype "passive"))
      (node (ref "C40") (pin "1") (pinfunction "1_1") (pintype "passive"))
      (node (ref "C41") (pin "1") (pinfunction "1_1") (pintype "passive"))
      (node (ref "C49") (pin "2") (pinfunction "2_2") (pintype "passive"))
      (node (ref "C51") (pin "2") (pinfunction "2_2") (pintype "passive"))
      (node (ref "C53") (pin "1") (pinfunction "1_1") (pintype "passive"))
      (node (ref "C56") (pin "1") (pinfunction "1_1") (pintype "passive"))
      (node (ref "C59") (pin "1") (pinfunction "1_1") (pintype "passive"))
      (node (ref "C8") (pin "1") (pinfunction "1_1") (pintype "passive"))
      (node (ref "C9") (pin "2") (pinfunction "2_2") (pintype "passive"))
      (node (ref "CAN") (pin "2") (pinfunction "2_2") (pintype "bidirectional"))
      (node (ref "DSM2") (pin "P$1") (pinfunction "1_P$1") (pintype "bidirectional"))
      (node (ref "E1") (pin "2") (pinfunction "2_2") (pintype "bidirectional"))
      (node (ref "E2") (pin "2") (pinfunction "2_2") (pintype "bidirectional"))
      (node (ref "E3") (pin "2") (pinfunction "2_2") (pintype "bidirectional"))
      (node (ref "E4") (pin "2") (pinfunction "2_2") (pintype "bidirectional"))
      (node (ref "GP0") (pin "2") (pinfunction "2_2") (pintype "bidirectional"))
      (node (ref "GP1") (pin "2") (pinfunction "2_2") (pintype "bidirectional"))
      (node (ref "H1") (pin "20") (pinfunction "VCC_20") (pintype "bidirectional"))
      (node (ref "H2") (pin "20") (pinfunction "VCC_20") (pintype "bidirectional"))
      (node (ref "I2C") (pin "2") (pinfunction "2_2") (pintype "bidirectional"))
      (node (ref "IMU") (pin "1") (pinfunction "RESV_1") (pintype "bidirectional"))
      (node (ref "IMU") (pin "13") (pinfunction "VDD_13") (pintype "bidirectional"))
      (node (ref "IMU") (pin "22") (pinfunction "NCS_22") (pintype "bidirectional"))
      (node (ref "IMU") (pin "8") (pinfunction "VDDIO_8") (pintype "bidirectional"))
      (node (ref "PWR") (pin "3") (pinfunction "3_3") (pintype "bidirectional"))
      (node (ref "R10") (pin "1") (pinfunction "1_1") (pintype "passive"))
      (node (ref "R109") (pin "1") (pinfunction "1_1") (pintype "passive"))
      (node (ref "R11") (pin "2") (pinfunction "2_2") (pintype "passive"))
      (node (ref "R116") (pin "2") (pinfunction "2_2") (pintype "passive"))
      (node (ref "R118") (pin "2") (pinfunction "2_2") (pintype "passive"))
      (node (ref "R12") (pin "2") (pinfunction "2_2") (pintype "passive"))
      (node (ref "R120") (pin "2") (pinfunction "2_2") (pintype "passive"))
      (node (ref "R122") (pin "2") (pinfunction "2_2") (pintype "passive"))
      (node (ref "R13") (pin "1") (pinfunction "1_1") (pintype "passive"))
      (node (ref "R140") (pin "2") (pinfunction "2_2") (pintype "passive"))
      (node (ref "R2") (pin "2") (pinfunction "2_2") (pintype "passive"))
      (node (ref "R23") (pin "2") (pinfunction "2_2") (pintype "passive"))
      (node (ref "R26") (pin "2") (pinfunction "2_2") (pintype "passive"))
      (node (ref "R35") (pin "2") (pinfunction "2_2") (pintype "passive"))
      (node (ref "R54") (pin "2") (pinfunction "2_2") (pintype "passive"))
      (node (ref "R55") (pin "2") (pinfunction "2_2") (pintype "passive"))
      (node (ref "R56") (pin "2") (pinfunction "2_2") (pintype "passive"))
      (node (ref "R57") (pin "2") (pinfunction "2_2") (pintype "passive"))
      (node (ref "R58") (pin "2") (pinfunction "2_2") (pintype "passive"))
      (node (ref "R60") (pin "2") (pinfunction "2_2") (pintype "passive"))
      (node (ref "R65") (pin "2") (pinfunction "2_2") (pintype "passive"))
      (node (ref "R66") (pin "2") (pinfunction "2_2") (pintype "passive"))
      (node (ref "R67") (pin "2") (pinfunction "2_2") (pintype "passive"))
      (node (ref "R68") (pin "2") (pinfunction "2_2") (pintype "passive"))
      (node (ref "R69") (pin "2") (pinfunction "2_2") (pintype "passive"))
      (node (ref "R70") (pin "2") (pinfunction "2_2") (pintype "passive"))
      (node (ref "R71") (pin "2") (pinfunction "2_2") (pintype "passive"))
      (node (ref "R72") (pin "2") (pinfunction "2_2") (pintype "passive"))
      (node (ref "R73") (pin "2") (pinfunction "2_2") (pintype "passive"))
      (node (ref "R74") (pin "2") (pinfunction "2_2") (pintype "passive"))
      (node (ref "R75") (pin "2") (pinfunction "2_2") (pintype "passive"))
      (node (ref "R94") (pin "2") (pinfunction "2_2") (pintype "passive"))
      (node (ref "S1.1") (pin "2") (pinfunction "2_2") (pintype "bidirectional"))
      (node (ref "S1.2") (pin "2") (pinfunction "2_2") (pintype "bidirectional"))
      (node (ref "SIP") (pin "U20") (pinfunction "VOUT_USER_3P3V_0_U20") (pintype "power_in"))
      (node (ref "SIP") (pin "V20") (pinfunction "VOUT_USER_3P3V_1_V20") (pintype "power_in"))
      (node (ref "U1") (pin "5") (pinfunction "VIO_5") (pintype "power_in"))
      (node (ref "U10") (pin "19") (pinfunction "VCCB_19") (pintype "bidirectional"))
      (node (ref "U13") (pin "C6") (pinfunction "VCCQ1_C6") (pintype "bidirectional"))
      (node (ref "U13") (pin "E6") (pinfunction "VCC1_E6") (pintype "bidirectional"))
      (node (ref "U13") (pin "F5") (pinfunction "VCC2_F5") (pintype "bidirectional"))
      (node (ref "U13") (pin "J10") (pinfunction "VCC3_J10") (pintype "bidirectional"))
      (node (ref "U13") (pin "K9") (pinfunction "VCC4_K9") (pintype "bidirectional"))
      (node (ref "U13") (pin "M4") (pinfunction "VCCQ2_M4") (pintype "bidirectional"))
      (node (ref "U13") (pin "N4") (pinfunction "VCCQ3_N4") (pintype "bidirectional"))
      (node (ref "U13") (pin "P3") (pinfunction "VCCQ4_P3") (pintype "bidirectional"))
      (node (ref "U13") (pin "P5") (pinfunction "VCCQ5_P5") (pintype "bidirectional"))
      (node (ref "U5") (pin "4") (pinfunction "VCC_4") (pintype "power_in"))
      (node (ref "U7") (pin "46") (pinfunction "VBAT_IN1_46") (pintype "bidirectional"))
      (node (ref "U7") (pin "47") (pinfunction "VBAT_IN2_47") (pintype "bidirectional"))
      (node (ref "U9") (pin "19") (pinfunction "VCCB_19") (pintype "bidirectional"))
      (node (ref "UT0") (pin "2") (pinfunction "2_2") (pintype "bidirectional"))
      (node (ref "UT1") (pin "2") (pinfunction "2_2") (pintype "bidirectional"))
      (node (ref "UT5") (pin "2") (pinfunction "2_2") (pintype "bidirectional"))
      (node (ref "X2") (pin "4") (pinfunction "VDD_4") (pintype "bidirectional"))
    )
    (net (code "2") (name "5.0V") (class "Default")
      (node (ref "5VREG") (pin "3") (pinfunction "FB_3") (pintype "power_in"))
      (node (ref "C5") (pin "1") (pinfunction "1_1") (pintype "passive"))
      (node (ref "C63") (pin "1") (pinfunction "1_1") (pintype "passive"))
      (node (ref "GPS") (pin "5") (pinfunction "5_5") (pintype "bidirectional"))
      (node (ref "L1") (pin "2") (pinfunction "2_2") (pintype "passive"))
      (node (ref "PWR") (pin "4") (pinfunction "4_4") (pintype "bidirectional"))
      (node (ref "R119") (pin "2") (pinfunction "2_2") (pintype "passive"))
      (node (ref "R95") (pin "2") (pinfunction "2_2") (pintype "passive"))
      (node (ref "SIP") (pin "Y5") (pinfunction "VIN_AC_0_Y5") (pintype "power_in"))
      (node (ref "SIP") (pin "Y6") (pinfunction "VIN_AC_1_Y6") (pintype "power_in"))
      (node (ref "U8") (pin "1") (pinfunction "EN_1") (pintype "input"))
      (node (ref "U8") (pin "5") (pinfunction "IN1_5") (pintype "input"))
    )
    (net (code "3") (name "32.768KHZ") (class "Default")
      (node (ref "OSC1") (pin "3") (pinfunction "OUT_3") (pintype "bidirectional"))
      (node (ref "U7") (pin "36") (pinfunction "EXT_32K_36") (pintype "bidirectional"))
    )
    (net (code "4") (name "AIN0") (class "Default")
      (node (ref "ADC") (pin "3") (pinfunction "3_3") (pintype "bidirectional"))
      (node (ref "SIP") (pin "B6") (pinfunction "AIN0_B6") (pintype "bidirectional"))
    )
    (net (code "5") (name "AIN1") (class "Default")
      (node (ref "ADC") (pin "4") (pinfunction "4_4") (pintype "bidirectional"))
      (node (ref "SIP") (pin "C7") (pinfunction "AIN1_C7") (pintype "bidirectional"))
    )
    (net (code "6") (name "AIN2") (class "Default")
      (node (ref "ADC") (pin "5") (pinfunction "5_5") (pintype "bidirectional"))
      (node (ref "SIP") (pin "B7") (pinfunction "AIN2_B7") (pintype "bidirectional"))
    )
    (net (code "7") (name "AIN3") (class "Default")
      (node (ref "ADC") (pin "6") (pinfunction "6_6") (pintype "bidirectional"))
      (node (ref "SIP") (pin "A7") (pinfunction "AIN3_A7") (pintype "bidirectional"))
    )
    (net (code "8") (name "BATT_LED_1") (class "Default")
      (node (ref "B0") (pin "A") (pinfunction "A_A") (pintype "passive"))
      (node (ref "SIP") (pin "U12") (pinfunction "GPIO0_27_U12_U12") (pintype "bidirectional"))
    )
    (net (code "9") (name "BATT_LED_2") (class "Default")
      (node (ref "B1") (pin "A") (pinfunction "A_A") (pintype "passive"))
      (node (ref "R143") (pin "2") (pinfunction "2_2") (pintype "passive"))
      (node (ref "SIP") (pin "T5") (pinfunction "LCD_DATA15_T5_T5") (pintype "bidirectional"))
    )
    (net (code "10") (name "BATT_LED_3") (class "Default")
      (node (ref "B2") (pin "A") (pinfunction "A_A") (pintype "passive"))
      (node (ref "SIP") (pin "V6") (pinfunction "GPIO1_29_V6_V6") (pintype "bidirectional"))
    )
    (net (code "11") (name "BATT_LED_4") (class "Default")
      (node (ref "B3") (pin "A") (pinfunction "A_A") (pintype "passive"))
      (node (ref "SIP") (pin "T11") (pinfunction "GPIO0_26_T11_T11") (pintype "bidirectional"))
    )
    (net (code "12") (name "BATT_MID") (class "Default")
      (node (ref "LIPO") (pin "P$2") (pinfunction "2_P$2") (pintype "passive"))
      (node (ref "R27") (pin "1") (pinfunction "1_1") (pintype "passive"))
      (node (ref "R30") (pin "1") (pinfunction "1_1") (pintype "passive"))
      (node (ref "R44") (pin "1") (pinfunction "1_1") (pintype "passive"))
    )
    (net (code "13") (name "BATT_MINUS") (class "Default")
      (node (ref "BAL") (pin "5") (pinfunction "GND_5") (pintype "bidirectional"))
      (node (ref "BAL") (pin "6") (pinfunction "CB_EN_6") (pintype "bidirectional"))
      (node (ref "C1") (pin "2") (pinfunction "2_2") (pintype "passive"))
      (node (ref "C15") (pin "1") (pinfunction "1_1") (pintype "passive"))
      (node (ref "C18") (pin "1") (pinfunction "1_1") (pintype "passive"))
      (node (ref "C19") (pin "2") (pinfunction "2_2") (pintype "passive"))
      (node (ref "LIPO") (pin "P$3") (pinfunction "3_P$3") (pintype "passive"))
      (node (ref "PROT") (pin "2") (pinfunction "VM_2") (pintype "bidirectional"))
      (node (ref "PROT") (pin "6") (pinfunction "VSS_6") (pintype "bidirectional"))
      (node (ref "Q1") (pin "1") (pinfunction "S_1") (pintype "passive"))
      (node (ref "Q1") (pin "2") (pinfunction "S_2") (pintype "passive"))
      (node (ref "Q1") (pin "3") (pinfunction "S_3") (pintype "passive"))
    )
    (net (code "14") (name "BT_AUD_CLK") (class "Default")
      (node (ref "R124") (pin "1") (pinfunction "1_1") (pintype "passive"))
      (node (ref "U10") (pin "1") (pinfunction "A1_1") (pintype "bidirectional"))
    )
    (net (code "15") (name "BT_AUD_FSYNC") (class "Default")
      (node (ref "R123") (pin "1") (pinfunction "1_1") (pintype "passive"))
      (node (ref "U10") (pin "3") (pinfunction "A2_3") (pintype "bidirectional"))
    )
    (net (code "16") (name "BT_AUD_IN") (class "Default")
      (node (ref "R97") (pin "1") (pinfunction "1_1") (pintype "passive"))
      (node (ref "U10") (pin "5") (pinfunction "A4_5") (pintype "bidirectional"))
    )
    (net (code "17") (name "BT_AUD_OUT") (class "Default")
      (node (ref "R100") (pin "1") (pinfunction "1_1") (pintype "passive"))
      (node (ref "U10") (pin "4") (pinfunction "A3_4") (pintype "bidirectional"))
    )
    (net (code "18") (name "BT_EN") (class "Default")
      (node (ref "SIP") (pin "K17") (pinfunction "K17_K17") (pintype "bidirectional"))
      (node (ref "U9") (pin "18") (pinfunction "B2_18") (pintype "bidirectional"))
    )
    (net (code "19") (name "BT_EN_1V8") (class "Default")
      (node (ref "R88") (pin "1") (pinfunction "1_1") (pintype "passive"))
      (node (ref "U7") (pin "41") (pinfunction "BT_EN_41") (pintype "bidirectional"))
      (node (ref "U9") (pin "3") (pinfunction "A2_3") (pintype "bidirectional"))
    )
    (net (code "20") (name "BT_HCI_CTS") (class "Default")
      (node (ref "R86") (pin "1") (pinfunction "1_1") (pintype "passive"))
      (node (ref "U10") (pin "8") (pinfunction "A7_8") (pintype "bidirectional"))
    )
    (net (code "21") (name "BT_HCI_RTS") (class "Default")
      (node (ref "R85") (pin "1") (pinfunction "1_1") (pintype "passive"))
      (node (ref "U10") (pin "9") (pinfunction "A8_9") (pintype "bidirectional"))
    )
    (net (code "22") (name "BT_HCI_RX") (class "Default")
      (node (ref "R96") (pin "1") (pinfunction "1_1") (pintype "passive"))
      (node (ref "U10") (pin "6") (pinfunction "A5_6") (pintype "bidirectional"))
    )
    (net (code "23") (name "BT_HCI_TX") (class "Default")
      (node (ref "R92") (pin "1") (pinfunction "1_1") (pintype "passive"))
      (node (ref "U10") (pin "7") (pinfunction "A6_7") (pintype "bidirectional"))
    )
    (net (code "24") (name "CANH") (class "Default")
      (node (ref "CAN") (pin "3") (pinfunction "3_3") (pintype "bidirectional"))
      (node (ref "R104") (pin "1") (pinfunction "1_1") (pintype "passive"))
      (node (ref "U1") (pin "7") (pinfunction "CANH_7") (pintype "bidirectional"))
    )
    (net (code "25") (name "CANL") (class "Default")
      (node (ref "CAN") (pin "4") (pinfunction "4_4") (pintype "bidirectional"))
      (node (ref "R104") (pin "2") (pinfunction "2_2") (pintype "passive"))
      (node (ref "U1") (pin "6") (pinfunction "CANL_6") (pintype "bidirectional"))
    )
    (net (code "26") (name "CGND") (class "Default")
      (node (ref "MGT1") (pin "P$1") (pinfunction "P$1_P$1") (pintype "bidirectional"))
      (node (ref "MGT2") (pin "P$1") (pinfunction "P$1_P$1") (pintype "bidirectional"))
      (node (ref "MGT3") (pin "P$1") (pinfunction "P$1_P$1") (pintype "bidirectional"))
      (node (ref "MGT4") (pin "P$1") (pinfunction "P$1_P$1") (pintype "bidirectional"))
      (node (ref "R107") (pin "2") (pinfunction "2_2") (pintype "passive"))
      (node (ref "X2") (pin "CGND1") (pinfunction "CGND1_CGND1") (pintype "bidirectional"))
      (node (ref "X2") (pin "CGND2") (pinfunction "CGND2_CGND2") (pintype "bidirectional"))
      (node (ref "X2") (pin "CGND3") (pinfunction "CGND3_CGND3") (pintype "bidirectional"))
      (node (ref "X2") (pin "CGND4") (pinfunction "CGND4_CGND4") (pintype "bidirectional"))
      (node (ref "X2") (pin "CGND5") (pinfunction "CGND5_CGND5") (pintype "bidirectional"))
      (node (ref "X2") (pin "CGND6") (pinfunction "CGND6_CGND6") (pintype "bidirectional"))
      (node (ref "X3") (pin "5") (pinfunction "CG1_5") (pintype "bidirectional"))
      (node (ref "X3") (pin "6") (pinfunction "CG2_6") (pintype "bidirectional"))
      (node (ref "X4") (pin "CGND1") (pinfunction "SGND1_CGND1") (pintype "bidirectional"))
      (node (ref "X4") (pin "CGND2") (pinfunction "SGND2_CGND2") (pintype "bidirectional"))
      (node (ref "X4") (pin "CGND3") (pinfunction "SGND3_CGND3") (pintype "bidirectional"))
      (node (ref "X4") (pin "CGND4") (pinfunction "SGND4_CGND4") (pintype "bidirectional"))
      (node (ref "X4") (pin "CGND5") (pinfunction "SGND5_CGND5") (pintype "bidirectional"))
      (node (ref "X4") (pin "CGND6") (pinfunction "SGND6_CGND6") (pintype "bidirectional"))
    )
    (net (code "27") (name "CHG_EN") (class "Default")
      (node (ref "CHGIC") (pin "6") (pinfunction "EN_6") (pintype "bidirectional"))
      (node (ref "R7") (pin "2") (pinfunction "2_2") (pintype "passive"))
      (node (ref "R8") (pin "1") (pinfunction "1_1") (pintype "passive"))
    )
    (net (code "28") (name "DCAN1_RX") (class "Default")
      (node (ref "SIP") (pin "E17") (pinfunction "UART0_RTSN_E17_E17") (pintype "bidirectional"))
      (node (ref "U1") (pin "4") (pinfunction "RXD_4") (pintype "output"))
    )
    (net (code "29") (name "DCAN1_SILENT") (class "Default")
      (node (ref "SIP") (pin "M16") (pinfunction "M16_M16") (pintype "bidirectional"))
      (node (ref "U1") (pin "8") (pinfunction "S_8") (pintype "input"))
    )
    (net (code "30") (name "DCAN1_TX") (class "Default")
      (node (ref "SIP") (pin "E18") (pinfunction "UART0_CTSN_E18_E18") (pintype "bidirectional"))
      (node (ref "U1") (pin "1") (pinfunction "TXD_1") (pintype "input"))
    )
    (net (code "31") (name "DO") (class "Default")
      (node (ref "PROT") (pin "1") (pinfunction "DO_1") (pintype "bidirectional"))
      (node (ref "Q1") (pin "4") (pinfunction "G_4") (pintype "passive"))
    )
    (net (code "32") (name "EMMC_RST") (class "Default")
      (node (ref "R94") (pin "1") (pinfunction "1_1") (pintype "passive"))
      (node (ref "SIP") (pin "R14") (pinfunction "EMMCRST_GPIO1_20_R14_R14") (pintype "bidirectional"))
      (node (ref "U13") (pin "K5") (pinfunction "RST#_K5") (pintype "bidirectional"))
    )
    (net (code "33") (name "EQEP_0A") (class "Default")
      (node (ref "E1") (pin "3") (pinfunction "3_3") (pintype "bidirectional"))
      (node (ref "SIP") (pin "B12") (pinfunction "GPIO3_18_B12_B12") (pintype "bidirectional"))
    )
    (net (code "34") (name "EQEP_0B") (class "Default")
      (node (ref "E1") (pin "4") (pinfunction "4_4") (pintype "bidirectional"))
      (node (ref "SIP") (pin "C13") (pinfunction "GPIO3_19_C13_C13") (pintype "bidirectional"))
    )
    (net (code "35") (name "EQEP_1A") (class "Default")
      (node (ref "E2") (pin "3") (pinfunction "3_3") (pintype "bidirectional"))
      (node (ref "R16") (pin "2") (pinfunction "2_2") (pintype "passive"))
      (node (ref "SIP") (pin "V2") (pinfunction "LCD_DATA12_V2_V2") (pintype "bidirectional"))
    )
    (net (code "36") (name "EQEP_1B") (class "Default")
      (node (ref "E2") (pin "4") (pinfunction "4_4") (pintype "bidirectional"))
      (node (ref "R17") (pin "2") (pinfunction "2_2") (pintype "passive"))
      (node (ref "SIP") (pin "V3") (pinfunction "LCD_DATA13_V3_V3") (pintype "bidirectional"))
    )
    (net (code "37") (name "EQEP_2A") (class "Default")
      (node (ref "E3") (pin "3") (pinfunction "3_3") (pintype "bidirectional"))
      (node (ref "SIP") (pin "T12") (pinfunction "GPIO1_12_T12_T12") (pintype "bidirectional"))
    )
    (net (code "38") (name "EQEP_2B") (class "Default")
      (node (ref "E3") (pin "4") (pinfunction "4_4") (pintype "bidirectional"))
      (node (ref "SIP") (pin "R12") (pinfunction "GPIO1_13_R12_R12") (pintype "bidirectional"))
    )
    (net (code "39") (name "GND") (class "Default")
      (node (ref "12V") (pin "OUT") (pinfunction "OUT_OUT") (pintype "bidirectional"))
      (node (ref "5VREG") (pin "4") (pinfunction "SD_4") (pintype "input"))
      (node (ref "5VREG") (pin "5") (pinfunction "GND_5") (pintype "power_in"))
      (node (ref "5VREG") (pin "6") (pinfunction "GND1_6") (pintype "input"))
      (node (ref "5VREG") (pin "7") (pinfunction "GND2_7") (pintype "passive"))
      (node (ref "5VREG") (pin "8") (pinfunction "GND3_8") (pintype "power_in"))
      (node (ref "6VREG") (pin "3") (pinfunction "GND_3") (pintype "bidirectional"))
      (node (ref "ADC") (pin "1") (pinfunction "1_1") (pintype "bidirectional"))
      (node (ref "ANT1") (pin "GND1") (pinfunction "GND1_GND1") (pintype "bidirectional"))
      (node (ref "ANT1") (pin "GND2") (pinfunction "GND2_GND2") (pintype "bidirectional"))
      (node (ref "ANT2") (pin "GND1") (pinfunction "GND1_GND1") (pintype "bidirectional"))
      (node (ref "ANT2") (pin "GND2") (pinfunction "GND2_GND2") (pintype "bidirectional"))
      (node (ref "BMP") (pin "1") (pinfunction "GND_1") (pintype "power_in"))
      (node (ref "BMP") (pin "5") (pinfunction "SDO_5") (pintype "bidirectional"))
      (node (ref "BMP") (pin "7") (pinfunction "GND_7") (pintype "power_in"))
      (node (ref "C10") (pin "1") (pinfunction "1_1") (pintype "passive"))
      (node (ref "C11") (pin "-") (pinfunction "-_-") (pintype "passive"))
      (node (ref "C12") (pin "2") (pinfunction "2_2") (pintype "passive"))
      (node (ref "C13") (pin "2") (pinfunction "2_2") (pintype "passive"))
      (node (ref "C16") (pin "2") (pinfunction "2_2") (pintype "passive"))
      (node (ref "C2") (pin "1") (pinfunction "1_1") (pintype "passive"))
      (node (ref "C20") (pin "1") (pinfunction "1_1") (pintype "passive"))
      (node (ref "C21") (pin "1") (pinfunction "1_1") (pintype "passive"))
      (node (ref "C23") (pin "1") (pinfunction "1_1") (pintype "passive"))
      (node (ref "C24") (pin "1") (pinfunction "1_1") (pintype "passive"))
      (node (ref "C25") (pin "2") (pinfunction "2_2") (pintype "passive"))
      (node (ref "C26") (pin "2") (pinfunction "2_2") (pintype "passive"))
      (node (ref "C27") (pin "2") (pinfunction "2_2") (pintype "passive"))
      (node (ref "C28") (pin "2") (pinfunction "2_2") (pintype "passive"))
      (node (ref "C3") (pin "2") (pinfunction "2_2") (pintype "passive"))
      (node (ref "C33") (pin "2") (pinfunction "2_2") (pintype "passive"))
      (node (ref "C34") (pin "1") (pinfunction "1_1") (pintype "passive"))
      (node (ref "C35") (pin "1") (pinfunction "1_1") (pintype "passive"))
      (node (ref "C36") (pin "2") (pinfunction "2_2") (pintype "passive"))
      (node (ref "C37") (pin "2") (pinfunction "2_2") (pintype "passive"))
      (node (ref "C38") (pin "2") (pinfunction "2_2") (pintype "passive"))
      (node (ref "C39") (pin "2") (pinfunction "2_2") (pintype "passive"))
      (node (ref "C4") (pin "1") (pinfunction "1_1") (pintype "passive"))
      (node (ref "C40") (pin "2") (pinfunction "2_2") (pintype "passive"))
      (node (ref "C41") (pin "2") (pinfunction "2_2") (pintype "passive"))
      (node (ref "C45") (pin "2") (pinfunction "2_2") (pintype "passive"))
      (node (ref "C46") (pin "2") (pinfunction "2_2") (pintype "passive"))
      (node (ref "C47") (pin "2") (pinfunction "2_2") (pintype "passive"))
      (node (ref "C49") (pin "1") (pinfunction "1_1") (pintype "passive"))
      (node (ref "C5") (pin "2") (pinfunction "2_2") (pintype "passive"))
      (node (ref "C50") (pin "2") (pinfunction "2_2") (pintype "passive"))
      (node (ref "C51") (pin "1") (pinfunction "1_1") (pintype "passive"))
      (node (ref "C52") (pin "2") (pinfunction "2_2") (pintype "passive"))
      (node (ref "C53") (pin "2") (pinfunction "2_2") (pintype "passive"))
      (node (ref "C54") (pin "2") (pinfunction "2_2") (pintype "passive"))
      (node (ref "C55") (pin "2") (pinfunction "2_2") (pintype "passive"))
      (node (ref "C56") (pin "2") (pinfunction "2_2") (pintype "passive"))
      (node (ref "C57") (pin "1") (pinfunction "1_1") (pintype "passive"))
      (node (ref "C59") (pin "2") (pinfunction "2_2") (pintype "passive"))
      (node (ref "C6") (pin "2") (pinfunction "2_2") (pintype "passive"))
      (node (ref "C60") (pin "1") (pinfunction "1_1") (pintype "passive"))
      (node (ref "C61") (pin "1") (pinfunction "1_1") (pintype "passive"))
      (node (ref "C62") (pin "2") (pinfunction "2_2") (pintype "passive"))
      (node (ref "C63") (pin "2") (pinfunction "2_2") (pintype "passive"))
      (node (ref "C7") (pin "2") (pinfunction "2_2") (pintype "passive"))
      (node (ref "C8") (pin "2") (pinfunction "2_2") (pintype "passive"))
      (node (ref "C9") (pin "1") (pinfunction "1_1") (pintype "passive"))
      (node (ref "CAN") (pin "1") (pinfunction "1_1") (pintype "bidirectional"))
      (node (ref "CHGIC") (pin "16") (pinfunction "PGND_16") (pintype "bidirectional"))
      (node (ref "CHGIC") (pin "8") (pinfunction "AGND_8") (pintype "bidirectional"))
      (node (ref "D1") (pin "A") (pinfunction "A_A") (pintype "passive"))
      (node (ref "D9") (pin "A") (pinfunction "A_A") (pintype "passive"))
      (node (ref "DSM2") (pin "P$2") (pinfunction "2_P$2") (pintype "bidirectional"))
      (node (ref "E1") (pin "1") (pinfunction "1_1") (pintype "bidirectional"))
      (node (ref "E2") (pin "1") (pinfunction "1_1") (pintype "bidirectional"))
      (node (ref "E3") (pin "1") (pinfunction "1_1") (pintype "bidirectional"))
      (node (ref "E4") (pin "1") (pinfunction "1_1") (pintype "bidirectional"))
      (node (ref "GND") (pin "P$1") (pinfunction "TP_P$1") (pintype "bidirectional"))
      (node (ref "GP0") (pin "1") (pinfunction "1_1") (pintype "bidirectional"))
      (node (ref "GP1") (pin "1") (pinfunction "1_1") (pintype "bidirectional"))
      (node (ref "GPS") (pin "2") (pinfunction "2_2") (pintype "bidirectional"))
      (node (ref "GPS") (pin "6") (pinfunction "6_6") (pintype "bidirectional"))
      (node (ref "H1") (pin "10") (pinfunction "PGND2_10") (pintype "bidirectional"))
      (node (ref "H1") (pin "18") (pinfunction "GND_18") (pintype "bidirectional"))
      (node (ref "H1") (pin "3") (pinfunction "PGND1_3") (pintype "bidirectional"))
      (node (ref "H1") (pin "4") (pinfunction "PGND1_4") (pintype "bidirectional"))
      (node (ref "H1") (pin "9") (pinfunction "PGND2_9") (pintype "bidirectional"))
      (node (ref "H2") (pin "10") (pinfunction "PGND2_10") (pintype "bidirectional"))
      (node (ref "H2") (pin "18") (pinfunction "GND_18") (pintype "bidirectional"))
      (node (ref "H2") (pin "3") (pinfunction "PGND1_3") (pintype "bidirectional"))
      (node (ref "H2") (pin "4") (pinfunction "PGND1_4") (pintype "bidirectional"))
      (node (ref "H2") (pin "9") (pinfunction "PGND2_9") (pintype "bidirectional"))
      (node (ref "I2C") (pin "1") (pinfunction "1_1") (pintype "bidirectional"))
      (node (ref "IMU") (pin "18") (pinfunction "GND_18") (pintype "bidirectional"))
      (node (ref "IMU") (pin "20") (pinfunction "RESV_20") (pintype "bidirectional"))
      (node (ref "IMU") (pin "9") (pinfunction "AD0/SDO_9") (pintype "bidirectional"))
      (node (ref "J2") (pin "P$13") (pinfunction "GND_P$13") (pintype "bidirectional"))
      (node (ref "J2") (pin "P$14") (pinfunction "GND_P$14") (pintype "bidirectional"))
      (node (ref "J2") (pin "P$15") (pinfunction "GND_P$15") (pintype "bidirectional"))
      (node (ref "J2") (pin "P$16") (pinfunction "GND_P$16") (pintype "bidirectional"))
      (node (ref "J2") (pin "P$17") (pinfunction "GND_P$17") (pintype "bidirectional"))
      (node (ref "J2") (pin "P$18") (pinfunction "GND_P$18") (pintype "bidirectional"))
      (node (ref "J2") (pin "P$23") (pinfunction "GND_P$23") (pintype "bidirectional"))
      (node (ref "J2") (pin "P$24") (pinfunction "GND_P$24") (pintype "bidirectional"))
      (node (ref "L4") (pin "1") (pinfunction "1_1") (pintype "passive"))
      (node (ref "MOD") (pin "1") (pinfunction "1_1") (pintype "passive"))
      (node (ref "OSC1") (pin "2") (pinfunction "GND_2") (pintype "bidirectional"))
      (node (ref "PAU") (pin "1") (pinfunction "1_1") (pintype "passive"))
      (node (ref "POW") (pin "1") (pinfunction "1_1") (pintype "passive"))
      (node (ref "PWR") (pin "1") (pinfunction "1_1") (pintype "bidirectional"))
      (node (ref "PWR") (pin "2") (pinfunction "2_2") (pintype "bidirectional"))
      (node (ref "Q1") (pin "5") (pinfunction "D_5") (pintype "passive"))
      (node (ref "Q1") (pin "6") (pinfunction "D_6") (pintype "passive"))
      (node (ref "Q1") (pin "7") (pinfunction "D_7") (pintype "passive"))
      (node (ref "Q1") (pin "8") (pinfunction "D_8") (pintype "passive"))
      (node (ref "R106") (pin "1") (pinfunction "1_1") (pintype "passive"))
      (node (ref "R107") (pin "1") (pinfunction "1_1") (pintype "passive"))
      (node (ref "R108") (pin "2") (pinfunction "2_2") (pintype "passive"))
      (node (ref "R110") (pin "2") (pinfunction "2_2") (pintype "passive"))
      (node (ref "R113") (pin "1") (pinfunction "1_1") (pintype "passive"))
      (node (ref "R115") (pin "1") (pinfunction "1_1") (pintype "passive"))
      (node (ref "R125") (pin "1") (pinfunction "1_1") (pintype "passive"))
      (node (ref "R127") (pin "1") (pinfunction "1_1") (pintype "passive"))
      (node (ref "R129") (pin "1") (pinfunction "1_1") (pintype "passive"))
      (node (ref "R131") (pin "1") (pinfunction "1_1") (pintype "passive"))
      (node (ref "R135") (pin "1") (pinfunction "1_1") (pintype "passive"))
      (node (ref "R14") (pin "2") (pinfunction "2_2") (pintype "passive"))
      (node (ref "R143") (pin "1") (pinfunction "1_1") (pintype "passive"))
      (node (ref "R150") (pin "2") (pinfunction "2_2") (pintype "passive"))
      (node (ref "R158") (pin "2") (pinfunction "2_2") (pintype "passive"))
      (node (ref "R16") (pin "1") (pinfunction "1_1") (pintype "passive"))
      (node (ref "R17") (pin "1") (pinfunction "1_1") (pintype "passive"))
      (node (ref "R21") (pin "2") (pinfunction "2_2") (pintype "passive"))
      (node (ref "R22") (pin "2") (pinfunction "2_2") (pintype "passive"))
      (node (ref "R24") (pin "2") (pinfunction "2_2") (pintype "passive"))
      (node (ref "R25") (pin "2") (pinfunction "2_2") (pintype "passive"))
      (node (ref "R29") (pin "2") (pinfunction "2_2") (pintype "passive"))
      (node (ref "R31") (pin "2") (pinfunction "2_2") (pintype "passive"))
      (node (ref "R32") (pin "2") (pinfunction "2_2") (pintype "passive"))
      (node (ref "R33") (pin "2") (pinfunction "2_2") (pintype "passive"))
      (node (ref "R46") (pin "1") (pinfunction "1_1") (pintype "passive"))
      (node (ref "R47") (pin "1") (pinfunction "1_1") (pintype "passive"))
      (node (ref "R48") (pin "1") (pinfunction "1_1") (pintype "passive"))
      (node (ref "R50") (pin "2") (pinfunction "2_2") (pintype "passive"))
      (node (ref "R51") (pin "2") (pinfunction "2_2") (pintype "passive"))
      (node (ref "R52") (pin "2") (pinfunction "2_2") (pintype "passive"))
      (node (ref "R53") (pin "2") (pinfunction "2_2") (pintype "passive"))
      (node (ref "R59") (pin "1") (pinfunction "1_1") (pintype "passive"))
      (node (ref "R6") (pin "1") (pinfunction "1_1") (pintype "passive"))
      (node (ref "R61") (pin "1") (pinfunction "1_1") (pintype "passive"))
      (node (ref "R62") (pin "1") (pinfunction "1_1") (pintype "passive"))
      (node (ref "R63") (pin "1") (pinfunction "1_1") (pintype "passive"))
      (node (ref "R64") (pin "1") (pinfunction "1_1") (pintype "passive"))
      (node (ref "R8") (pin "2") (pinfunction "2_2") (pintype "passive"))
      (node (ref "R87") (pin "2") (pinfunction "2_2") (pintype "passive"))
      (node (ref "R88") (pin "2") (pinfunction "2_2") (pintype "passive"))
      (node (ref "R89") (pin "2") (pinfunction "2_2") (pintype "passive"))
      (node (ref "R91") (pin "2") (pinfunction "2_2") (pintype "passive"))
      (node (ref "R95") (pin "1") (pinfunction "1_1") (pintype "passive"))
      (node (ref "RST") (pin "1") (pinfunction "1_1") (pintype "passive"))
      (node (ref "S1.1") (pin "1") (pinfunction "1_1") (pintype "bidirectional"))
      (node (ref "S1.2") (pin "1") (pinfunction "1_1") (pintype "bidirectional"))
      (node (ref "SD") (pin "1") (pinfunction "1_1") (pintype "passive"))
      (node (ref "SIP") (pin "A1") (pinfunction "DGND1_A1") (pintype "bidirectional"))
      (node (ref "SIP") (pin "A18") (pinfunction "DGND2_A18") (pintype "bidirectional"))
      (node (ref "SIP") (pin "E19") (pinfunction "DGND3_E19") (pintype "bidirectional"))
      (node (ref "SIP") (pin "E20") (pinfunction "DGND4_E20") (pintype "bidirectional"))
      (node (ref "SIP") (pin "F19") (pinfunction "DGND6_F19") (pintype "bidirectional"))
      (node (ref "SIP") (pin "F8") (pinfunction "DGND5_F8") (pintype "bidirectional"))
      (node (ref "SIP") (pin "G11") (pinfunction "DGND9_G11") (pintype "bidirectional"))
      (node (ref "SIP") (pin "G12") (pinfunction "DGND10_G12") (pintype "bidirectional"))
      (node (ref "SIP") (pin "G19") (pinfunction "DGND11_G19") (pintype "bidirectional"))
      (node (ref "SIP") (pin "G8") (pinfunction "DGND7_G8") (pintype "bidirectional"))
      (node (ref "SIP") (pin "G9") (pinfunction "DGND8_G9") (pintype "bidirectional"))
      (node (ref "SIP") (pin "H10") (pinfunction "DGND16_H10") (pintype "bidirectional"))
      (node (ref "SIP") (pin "H12") (pinfunction "DGND17_H12") (pintype "bidirectional"))
      (node (ref "SIP") (pin "H19") (pinfunction "DGND18_H19") (pintype "bidirectional"))
      (node (ref "SIP") (pin "H6") (pinfunction "DGND12_H6") (pintype "bidirectional"))
      (node (ref "SIP") (pin "H7") (pinfunction "DGND13_H7") (pintype "bidirectional"))
      (node (ref "SIP") (pin "H8") (pinfunction "DGND14_H8") (pintype "bidirectional"))
      (node (ref "SIP") (pin "H9") (pinfunction "DGND15_H9") (pintype "bidirectional"))
      (node (ref "SIP") (pin "J10") (pinfunction "DGND23_J10") (pintype "bidirectional"))
      (node (ref "SIP") (pin "J11") (pinfunction "DGND24_J11") (pintype "bidirectional"))
      (node (ref "SIP") (pin "J19") (pinfunction "DGND25_J19") (pintype "bidirectional"))
      (node (ref "SIP") (pin "J20") (pinfunction "DGND26_J20") (pintype "bidirectional"))
      (node (ref "SIP") (pin "J6") (pinfunction "DGND19_J6") (pintype "bidirectional"))
      (node (ref "SIP") (pin "J7") (pinfunction "DGND20_J7") (pintype "bidirectional"))
      (node (ref "SIP") (pin "J8") (pinfunction "DGND21_J8") (pintype "bidirectional"))
      (node (ref "SIP") (pin "J9") (pinfunction "DGND22_J9") (pintype "bidirectional"))
      (node (ref "SIP") (pin "K10") (pinfunction "DGND29_K10") (pintype "bidirectional"))
      (node (ref "SIP") (pin "K11") (pinfunction "DGND30_K11") (pintype "bidirectional"))
      (node (ref "SIP") (pin "K19") (pinfunction "DGND31_K19") (pintype "bidirectional"))
      (node (ref "SIP") (pin "K7") (pinfunction "DGND27_K7") (pintype "bidirectional"))
      (node (ref "SIP") (pin "K9") (pinfunction "DGND28_K9") (pintype "bidirectional"))
      (node (ref "SIP") (pin "L10") (pinfunction "DGND32_L10") (pintype "bidirectional"))
      (node (ref "SIP") (pin "L11") (pinfunction "DGND33_L11") (pintype "bidirectional"))
      (node (ref "SIP") (pin "L12") (pinfunction "DGND34_L12") (pintype "bidirectional"))
      (node (ref "SIP") (pin "L13") (pinfunction "DGND35_L13") (pintype "bidirectional"))
      (node (ref "SIP") (pin "L19") (pinfunction "DGND36_L19") (pintype "bidirectional"))
      (node (ref "SIP") (pin "M10") (pinfunction "DGND42_M10") (pintype "bidirectional"))
      (node (ref "SIP") (pin "M12") (pinfunction "DGND43_M12") (pintype "bidirectional"))
      (node (ref "SIP") (pin "M14") (pinfunction "DGND44_M14") (pintype "bidirectional"))
      (node (ref "SIP") (pin "M19") (pinfunction "DGND45_M19") (pintype "bidirectional"))
      (node (ref "SIP") (pin "M6") (pinfunction "DGND38_M6") (pintype "bidirectional"))
      (node (ref "SIP") (pin "M7") (pinfunction "DGND39_M7") (pintype "bidirectional"))
      (node (ref "SIP") (pin "M8") (pinfunction "DGND40_M8") (pintype "bidirectional"))
      (node (ref "SIP") (pin "M9") (pinfunction "DGND41_M9") (pintype "bidirectional"))
      (node (ref "SIP") (pin "N10") (pinfunction "DGND47_N10") (pintype "bidirectional"))
      (node (ref "SIP") (pin "N11") (pinfunction "DGND48_N11") (pintype "bidirectional"))
      (node (ref "SIP") (pin "N14") (pinfunction "DGND49_N14") (pintype "bidirectional"))
      (node (ref "SIP") (pin "N19") (pinfunction "DGND50_N19") (pintype "bidirectional"))
      (node (ref "SIP") (pin "N20") (pinfunction "DGND51_N20") (pintype "bidirectional"))
      (node (ref "SIP") (pin "N7") (pinfunction "DGND46_N7") (pintype "bidirectional"))
      (node (ref "SIP") (pin "P19") (pinfunction "DGND52_P19") (pintype "bidirectional"))
      (node (ref "SIP") (pin "P20") (pinfunction "DGND53_P20") (pintype "bidirectional"))
      (node (ref "SIP") (pin "R19") (pinfunction "DGND54_R19") (pintype "bidirectional"))
      (node (ref "SIP") (pin "R20") (pinfunction "DGND55_R20") (pintype "bidirectional"))
      (node (ref "SIP") (pin "T19") (pinfunction "DGND56_T19") (pintype "bidirectional"))
      (node (ref "SIP") (pin "T20") (pinfunction "DGND57_T20") (pintype "bidirectional"))
      (node (ref "SIP") (pin "U19") (pinfunction "DGND58_U19") (pintype "bidirectional"))
      (node (ref "SIP") (pin "V1") (pinfunction "DGND59_V1") (pintype "bidirectional"))
      (node (ref "SIP") (pin "V18") (pinfunction "DGND60_V18") (pintype "bidirectional"))
      (node (ref "SIP") (pin "V19") (pinfunction "DGND61_V19") (pintype "bidirectional"))
      (node (ref "SIP") (pin "W10") (pinfunction "DGND70_W10") (pintype "bidirectional"))
      (node (ref "SIP") (pin "W11") (pinfunction "DGND71_W11") (pintype "bidirectional"))
      (node (ref "SIP") (pin "W12") (pinfunction "DGND72_W12") (pintype "bidirectional"))
      (node (ref "SIP") (pin "W13") (pinfunction "DGND73_W13") (pintype "bidirectional"))
      (node (ref "SIP") (pin "W14") (pinfunction "DGND74_W14") (pintype "bidirectional"))
      (node (ref "SIP") (pin "W15") (pinfunction "DGND75_W15") (pintype "bidirectional"))
      (node (ref "SIP") (pin "W16") (pinfunction "DGND76_W16") (pintype "bidirectional"))
      (node (ref "SIP") (pin "W17") (pinfunction "DGND77_W17") (pintype "bidirectional"))
      (node (ref "SIP") (pin "W18") (pinfunction "DGND78_W18") (pintype "bidirectional"))
      (node (ref "SIP") (pin "W19") (pinfunction "DGND79_W19") (pintype "bidirectional"))
      (node (ref "SIP") (pin "W2") (pinfunction "DGND62_W2") (pintype "bidirectional"))
      (node (ref "SIP") (pin "W20") (pinfunction "DGND80_W20") (pintype "bidirectional"))
      (node (ref "SIP") (pin "W3") (pinfunction "DGND63_W3") (pintype "bidirectional"))
      (node (ref "SIP") (pin "W5") (pinfunction "DGND65_W5") (pintype "bidirectional"))
      (node (ref "SIP") (pin "W6") (pinfunction "DGND66_W6") (pintype "bidirectional"))
      (node (ref "SIP") (pin "W7") (pinfunction "DGND67_W7") (pintype "bidirectional"))
      (node (ref "SIP") (pin "W8") (pinfunction "DGND68_W8") (pintype "bidirectional"))
      (node (ref "SIP") (pin "W9") (pinfunction "DGND69_W9") (pintype "bidirectional"))
      (node (ref "SIP") (pin "Y10") (pinfunction "DGND83_Y10") (pintype "bidirectional"))
      (node (ref "SIP") (pin "Y12") (pinfunction "DGND84_Y12") (pintype "bidirectional"))
      (node (ref "SIP") (pin "Y15") (pinfunction "DGND85_Y15") (pintype "bidirectional"))
      (node (ref "SIP") (pin "Y18") (pinfunction "DGND86_Y18") (pintype "bidirectional"))
      (node (ref "SIP") (pin "Y7") (pinfunction "DGND82_Y7") (pintype "bidirectional"))
      (node (ref "TP12") (pin "TP") (pinfunction "TP_TP") (pintype "input"))
      (node (ref "U1") (pin "2") (pinfunction "GND_2") (pintype "power_in"))
      (node (ref "U10") (pin "11") (pinfunction "GND_11") (pintype "bidirectional"))
      (node (ref "U10") (pin "TP") (pinfunction "TP_TP") (pintype "bidirectional"))
      (node (ref "U13") (pin "C4") (pinfunction "VSSQ1_C4") (pintype "bidirectional"))
      (node (ref "U13") (pin "E7") (pinfunction "VSS1_E7") (pintype "bidirectional"))
      (node (ref "U13") (pin "G5") (pinfunction "VSS2_G5") (pintype "bidirectional"))
      (node (ref "U13") (pin "H10") (pinfunction "VSS3_H10") (pintype "bidirectional"))
      (node (ref "U13") (pin "K8") (pinfunction "VSS4_K8") (pintype "bidirectional"))
      (node (ref "U13") (pin "N2") (pinfunction "VSSQ2_N2") (pintype "bidirectional"))
      (node (ref "U13") (pin "N5") (pinfunction "VSSQ3_N5") (pintype "bidirectional"))
      (node (ref "U13") (pin "P4") (pinfunction "VSSQ4_P4") (pintype "bidirectional"))
      (node (ref "U13") (pin "P6") (pinfunction "VSSQ5_P6") (pintype "bidirectional"))
      (node (ref "U2") (pin "3") (pinfunction "GND_3") (pintype "power_in"))
      (node (ref "U3") (pin "4") (pinfunction "GND_4") (pintype "bidirectional"))
      (node (ref "U4") (pin "4") (pinfunction "GND_4") (pintype "bidirectional"))
      (node (ref "U5") (pin "2") (pinfunction "VSS_2") (pintype "passive"))
      (node (ref "U6") (pin "3") (pinfunction "GND_3") (pintype "power_in"))
      (node (ref "U7") (pin "1") (pinfunction "GND1_1") (pintype "bidirectional"))
      (node (ref "U7") (pin "15") (pinfunction "GND4_15") (pintype "bidirectional"))
      (node (ref "U7") (pin "16") (pinfunction "GND5_16") (pintype "bidirectional"))
      (node (ref "U7") (pin "17") (pinfunction "GND6_17") (pintype "bidirectional"))
      (node (ref "U7") (pin "19") (pinfunction "GND7_19") (pintype "bidirectional"))
      (node (ref "U7") (pin "20") (pinfunction "GND8_20") (pintype "bidirectional"))
      (node (ref "U7") (pin "23") (pinfunction "GND9_23") (pintype "bidirectional"))
      (node (ref "U7") (pin "24") (pinfunction "GND10_24") (pintype "bidirectional"))
      (node (ref "U7") (pin "28") (pinfunction "GND11_28") (pintype "bidirectional"))
      (node (ref "U7") (pin "29") (pinfunction "GND12_29") (pintype "bidirectional"))
      (node (ref "U7") (pin "30") (pinfunction "GND13_30") (pintype "bidirectional"))
      (node (ref "U7") (pin "31") (pinfunction "GND14_31") (pintype "bidirectional"))
      (node (ref "U7") (pin "33") (pinfunction "GND15_33") (pintype "bidirectional"))
      (node (ref "U7") (pin "34") (pinfunction "GND16_34") (pintype "bidirectional"))
      (node (ref "U7") (pin "35") (pinfunction "GND17_35") (pintype "bidirectional"))
      (node (ref "U7") (pin "37") (pinfunction "GND18_37") (pintype "bidirectional"))
      (node (ref "U7") (pin "39") (pinfunction "GND19_39") (pintype "bidirectional"))
      (node (ref "U7") (pin "44") (pinfunction "GND20_44") (pintype "bidirectional"))
      (node (ref "U7") (pin "45") (pinfunction "GND21_45") (pintype "bidirectional"))
      (node (ref "U7") (pin "48") (pinfunction "GND22_48") (pintype "bidirectional"))
      (node (ref "U7") (pin "49") (pinfunction "GND23_49") (pintype "bidirectional"))
      (node (ref "U7") (pin "54") (pinfunction "GND24_54") (pintype "bidirectional"))
      (node (ref "U7") (pin "55") (pinfunction "GND25_55") (pintype "bidirectional"))
      (node (ref "U7") (pin "59") (pinfunction "GND26_59") (pintype "bidirectional"))
      (node (ref "U7") (pin "61") (pinfunction "GND27_61") (pintype "bidirectional"))
      (node (ref "U7") (pin "63") (pinfunction "GND28_63") (pintype "bidirectional"))
      (node (ref "U7") (pin "64") (pinfunction "GND29_64") (pintype "bidirectional"))
      (node (ref "U7") (pin "7") (pinfunction "GND2_7") (pintype "bidirectional"))
      (node (ref "U7") (pin "9") (pinfunction "GND3_9") (pintype "bidirectional"))
      (node (ref "U7") (pin "G1") (pinfunction "G1_G1") (pintype "bidirectional"))
      (node (ref "U7") (pin "G10") (pinfunction "G10_G10") (pintype "bidirectional"))
      (node (ref "U7") (pin "G11") (pinfunction "G11_G11") (pintype "bidirectional"))
      (node (ref "U7") (pin "G12") (pinfunction "G12_G12") (pintype "bidirectional"))
      (node (ref "U7") (pin "G13") (pinfunction "G13_G13") (pintype "bidirectional"))
      (node (ref "U7") (pin "G14") (pinfunction "G14_G14") (pintype "bidirectional"))
      (node (ref "U7") (pin "G15") (pinfunction "G15_G15") (pintype "bidirectional"))
      (node (ref "U7") (pin "G16") (pinfunction "G16_G16") (pintype "bidirectional"))
      (node (ref "U7") (pin "G17") (pinfunction "G17_G17") (pintype "bidirectional"))
      (node (ref "U7") (pin "G18") (pinfunction "G18_G18") (pintype "bidirectional"))
      (node (ref "U7") (pin "G19") (pinfunction "G19_G19") (pintype "bidirectional"))
      (node (ref "U7") (pin "G2") (pinfunction "G2_G2") (pintype "bidirectional"))
      (node (ref "U7") (pin "G20") (pinfunction "G20_G20") (pintype "bidirectional"))
      (node (ref "U7") (pin "G21") (pinfunction "G21_G21") (pintype "bidirectional"))
      (node (ref "U7") (pin "G22") (pinfunction "G22_G22") (pintype "bidirectional"))
      (node (ref "U7") (pin "G23") (pinfunction "G23_G23") (pintype "bidirectional"))
      (node (ref "U7") (pin "G24") (pinfunction "G24_G24") (pintype "bidirectional"))
      (node (ref "U7") (pin "G25") (pinfunction "G25_G25") (pintype "bidirectional"))
      (node (ref "U7") (pin "G26") (pinfunction "G26_G26") (pintype "bidirectional"))
      (node (ref "U7") (pin "G27") (pinfunction "G27_G27") (pintype "bidirectional"))
      (node (ref "U7") (pin "G28") (pinfunction "G28_G28") (pintype "bidirectional"))
      (node (ref "U7") (pin "G29") (pinfunction "G29_G29") (pintype "bidirectional"))
      (node (ref "U7") (pin "G3") (pinfunction "G3_G3") (pintype "bidirectional"))
      (node (ref "U7") (pin "G30") (pinfunction "G30_G30") (pintype "bidirectional"))
      (node (ref "U7") (pin "G31") (pinfunction "G31_G31") (pintype "bidirectional"))
      (node (ref "U7") (pin "G32") (pinfunction "G32_G32") (pintype "bidirectional"))
      (node (ref "U7") (pin "G33") (pinfunction "G33_G33") (pintype "bidirectional"))
      (node (ref "U7") (pin "G34") (pinfunction "G34_G34") (pintype "bidirectional"))
      (node (ref "U7") (pin "G35") (pinfunction "G35_G35") (pintype "bidirectional"))
      (node (ref "U7") (pin "G36") (pinfunction "G36_G36") (pintype "bidirectional"))
      (node (ref "U7") (pin "G4") (pinfunction "G4_G4") (pintype "bidirectional"))
      (node (ref "U7") (pin "G5") (pinfunction "G5_G5") (pintype "bidirectional"))
      (node (ref "U7") (pin "G6") (pinfunction "G6_G6") (pintype "bidirectional"))
      (node (ref "U7") (pin "G7") (pinfunction "G7_G7") (pintype "bidirectional"))
      (node (ref "U7") (pin "G8") (pinfunction "G8_G8") (pintype "bidirectional"))
      (node (ref "U7") (pin "G9") (pinfunction "G9_G9") (pintype "bidirectional"))
      (node (ref "U8") (pin "2") (pinfunction "GND_2") (pintype "power_in"))
      (node (ref "U9") (pin "11") (pinfunction "GND_11") (pintype "bidirectional"))
      (node (ref "U9") (pin "TP") (pinfunction "TP_TP") (pintype "bidirectional"))
      (node (ref "UT0") (pin "1") (pinfunction "1_1") (pintype "bidirectional"))
      (node (ref "UT1") (pin "1") (pinfunction "1_1") (pintype "bidirectional"))
      (node (ref "UT5") (pin "1") (pinfunction "1_1") (pintype "bidirectional"))
      (node (ref "X2") (pin "6") (pinfunction "VSS_6") (pintype "bidirectional"))
      (node (ref "X2") (pin "GND") (pinfunction "GND_GND") (pintype "bidirectional"))
      (node (ref "X4") (pin "GND") (pinfunction "GND_GND") (pintype "input"))
    )
    (net (code "40") (name "GNDA_ADC") (class "Default")
      (node (ref "C42") (pin "2") (pinfunction "2_2") (pintype "passive"))
      (node (ref "C43") (pin "2") (pinfunction "2_2") (pintype "passive"))
      (node (ref "C44") (pin "2") (pinfunction "2_2") (pintype "passive"))
      (node (ref "SIP") (pin "A6") (pinfunction "VSSA_ADC_0_A6") (pintype "bidirectional"))
      (node (ref "SIP") (pin "A9") (pinfunction "VSSA_ADC_1_A9") (pintype "bidirectional"))
      (node (ref "SIP") (pin "E8") (pinfunction "VSSA_ADC_2_E8") (pintype "bidirectional"))
    )
    (net (code "41") (name "GPIO1_17") (class "Default")
      (node (ref "GP0") (pin "4") (pinfunction "4_4") (pintype "bidirectional"))
      (node (ref "SIP") (pin "V14") (pinfunction "GPIO1_17_V14_V14") (pintype "bidirectional"))
    )
    (net (code "42") (name "GPIO1_25") (class "Default")
      (node (ref "GP0") (pin "3") (pinfunction "3_3") (pintype "bidirectional"))
      (node (ref "SIP") (pin "U16") (pinfunction "HDMIINT_GPIO1_25_U16_U16") (pintype "bidirectional"))
    )
    (net (code "43") (name "GPIO3_1") (class "Default")
      (node (ref "GP1") (pin "4") (pinfunction "4_4") (pintype "bidirectional"))
      (node (ref "SIP") (pin "H17") (pinfunction "H17_H17") (pintype "bidirectional"))
    )
    (net (code "44") (name "GPIO3_2") (class "Default")
      (node (ref "GP1") (pin "3") (pinfunction "3_3") (pintype "bidirectional"))
      (node (ref "SIP") (pin "J15") (pinfunction "J15_J15") (pintype "bidirectional"))
    )
    (net (code "45") (name "GPIO3_17") (class "Default")
      (node (ref "GP0") (pin "6") (pinfunction "6_6") (pintype "bidirectional"))
      (node (ref "SIP") (pin "C12") (pinfunction "SPI1_CS0_C12_C12") (pintype "bidirectional"))
    )
    (net (code "46") (name "GPIO3_20") (class "Default")
      (node (ref "GP0") (pin "5") (pinfunction "5_5") (pintype "bidirectional"))
      (node (ref "SIP") (pin "D13") (pinfunction "GPIO3_20_D13_D13") (pintype "bidirectional"))
    )
    (net (code "47") (name "I2C0_SCL") (class "Default")
      (node (ref "R23") (pin "1") (pinfunction "1_1") (pintype "passive"))
      (node (ref "SIP") (pin "C16") (pinfunction "I2C0_SCL_C16") (pintype "bidirectional"))
      (node (ref "SIP") (pin "C20") (pinfunction "PMIC_I2C_SCL_C20") (pintype "bidirectional"))
      (node (ref "U5") (pin "1") (pinfunction "SCL_1") (pintype "input"))
    )
    (net (code "48") (name "I2C0_SDA") (class "Default")
      (node (ref "R2") (pin "1") (pinfunction "1_1") (pintype "passive"))
      (node (ref "SIP") (pin "C17") (pinfunction "I2C0_SDA_C17") (pintype "bidirectional"))
      (node (ref "SIP") (pin "C19") (pinfunction "PMIC_I2C_SDA_C19") (pintype "bidirectional"))
      (node (ref "U5") (pin "3") (pinfunction "SDA_3") (pintype "bidirectional"))
    )
    (net (code "49") (name "I2C1_SCL") (class "Default")
      (node (ref "I2C") (pin "3") (pinfunction "3_3") (pintype "bidirectional"))
      (node (ref "R12") (pin "1") (pinfunction "1_1") (pintype "passive"))
      (node (ref "SIP") (pin "A16") (pinfunction "I2C1_SCL_A16_A16") (pintype "bidirectional"))
    )
    (net (code "50") (name "I2C1_SDA") (class "Default")
      (node (ref "I2C") (pin "4") (pinfunction "4_4") (pintype "bidirectional"))
      (node (ref "R13") (pin "2") (pinfunction "2_2") (pintype "passive"))
      (node (ref "SIP") (pin "B16") (pinfunction "I2C1_SDA_B16_B16") (pintype "bidirectional"))
    )
    (net (code "51") (name "I2C2_SCL") (class "Default")
      (node (ref "BMP") (pin "4") (pinfunction "SCK_4") (pintype "input"))
      (node (ref "IMU") (pin "23") (pinfunction "SCL/SCLK_23") (pintype "bidirectional"))
      (node (ref "R11") (pin "1") (pinfunction "1_1") (pintype "passive"))
      (node (ref "SIP") (pin "D17") (pinfunction "I2C2_SCL_D17_D17") (pintype "bidirectional"))
    )
    (net (code "52") (name "I2C2_SDA") (class "Default")
      (node (ref "BMP") (pin "3") (pinfunction "SDI_3") (pintype "bidirectional"))
      (node (ref "IMU") (pin "24") (pinfunction "SDA/SDI_24") (pintype "bidirectional"))
      (node (ref "R10") (pin "2") (pinfunction "2_2") (pintype "passive"))
      (node (ref "SIP") (pin "D18") (pinfunction "I2C2_SDA_D18_D18") (pintype "bidirectional"))
    )
    (net (code "53") (name "IMU_INT") (class "Default")
      (node (ref "IMU") (pin "12") (pinfunction "INT_12") (pintype "bidirectional"))
      (node (ref "SIP") (pin "A14") (pinfunction "GPIO3_21_A14_A14") (pintype "bidirectional"))
    )
    (net (code "54") (name "LDO_PGOOD") (class "Default")
      (node (ref "SIP") (pin "B20") (pinfunction "PMIC_OUT_LDO_PGOOD_B20") (pintype "output"))
      (node (ref "SIP") (pin "B5") (pinfunction "RTC_PWRONRSTN_B5") (pintype "bidirectional"))
    )
    (net (code "55") (name "LED_GRN") (class "Default")
      (node (ref "G") (pin "A") (pinfunction "A_A") (pintype "passive"))
      (node (ref "GP1") (pin "6") (pinfunction "6_6") (pintype "bidirectional"))
      (node (ref "SIP") (pin "T7") (pinfunction "TIMER7_T7_T7") (pintype "bidirectional"))
    )
    (net (code "56") (name "LED_RED") (class "Default")
      (node (ref "GP1") (pin "5") (pinfunction "5_5") (pintype "bidirectional"))
      (node (ref "R") (pin "A") (pinfunction "A_A") (pintype "passive"))
      (node (ref "SIP") (pin "R7") (pinfunction "TIMER4_R7_R7") (pintype "bidirectional"))
    )
    (net (code "57") (name "MCASP0_ACLKR") (class "Default")
      (node (ref "SIP") (pin "U18") (pinfunction "GPIO1_28_U18_U18") (pintype "bidirectional"))
      (node (ref "U10") (pin "20") (pinfunction "B1_20") (pintype "bidirectional"))
    )
    (net (code "58") (name "MCASP0_AXR0") (class "Default")
      (node (ref "SIP") (pin "T16") (pinfunction "USB1OC_GPIO1_26_T16_T16") (pintype "bidirectional"))
      (node (ref "U10") (pin "17") (pinfunction "B3_17") (pintype "bidirectional"))
    )
    (net (code "59") (name "MCASP0_AXR1") (class "Default")
      (node (ref "SIP") (pin "V17") (pinfunction "HDMIDIS_GPIO1_27_V17_V17") (pintype "bidirectional"))
      (node (ref "U10") (pin "16") (pinfunction "B4_16") (pintype "bidirectional"))
    )
    (net (code "60") (name "MCASP0_FSR") (class "Default")
      (node (ref "SIP") (pin "V12") (pinfunction "GPIO2_1_V12_V12") (pintype "bidirectional"))
      (node (ref "U10") (pin "18") (pinfunction "B2_18") (pintype "bidirectional"))
    )
    (net (code "61") (name "MDIR_1A") (class "Default")
      (node (ref "H1") (pin "21") (pinfunction "AIN1_21") (pintype "bidirectional"))
      (node (ref "SIP") (pin "T13") (pinfunction "GPIO2_0_T13_T13") (pintype "bidirectional"))
    )
    (net (code "62") (name "MDIR_1B") (class "Default")
      (node (ref "H1") (pin "22") (pinfunction "AIN2_22") (pintype "bidirectional"))
      (node (ref "SIP") (pin "U17") (pinfunction "UART4_TXD_U17_U17") (pintype "bidirectional"))
    )
    (net (code "63") (name "MDIR_2A") (class "Default")
      (node (ref "H1") (pin "17") (pinfunction "BIN1_17") (pintype "bidirectional"))
      (node (ref "SIP") (pin "R13") (pinfunction "GPIO1_16_R13_R13") (pintype "bidirectional"))
    )
    (net (code "64") (name "MDIR_2B") (class "Default")
      (node (ref "H1") (pin "16") (pinfunction "BIN2_16") (pintype "bidirectional"))
      (node (ref "R140") (pin "1") (pinfunction "1_1") (pintype "passive"))
      (node (ref "SIP") (pin "V4") (pinfunction "LCD_DATA14_V4_V4") (pintype "bidirectional"))
    )
    (net (code "65") (name "MDIR_3A") (class "Default")
      (node (ref "H2") (pin "21") (pinfunction "AIN1_21") (pintype "bidirectional"))
      (node (ref "R118") (pin "1") (pinfunction "1_1") (pintype "passive"))
      (node (ref "SIP") (pin "R4") (pinfunction "LCD_DATA3_R4_R4") (pintype "bidirectional"))
    )
    (net (code "66") (name "MDIR_3B") (class "Default")
      (node (ref "H2") (pin "22") (pinfunction "AIN2_22") (pintype "bidirectional"))
      (node (ref "R116") (pin "1") (pinfunction "1_1") (pintype "passive"))
      (node (ref "R77") (pin "1") (pinfunction "1_1") (pintype "passive"))
      (node (ref "SIP") (pin "R3") (pinfunction "LCD_DATA2_R3_R3") (pintype "bidirectional"))
    )
    (net (code "67") (name "MDIR_4A") (class "Default")
      (node (ref "H2") (pin "17") (pinfunction "BIN1_17") (pintype "bidirectional"))
      (node (ref "R113") (pin "2") (pinfunction "2_2") (pintype "passive"))
      (node (ref "SIP") (pin "R1") (pinfunction "LCD_DATA0_R1_R1") (pintype "bidirectional"))
    )
    (net (code "68") (name "MDIR_4B") (class "Default")
      (node (ref "H2") (pin "16") (pinfunction "BIN2_16") (pintype "bidirectional"))
      (node (ref "R115") (pin "2") (pinfunction "2_2") (pintype "passive"))
      (node (ref "SIP") (pin "R2") (pinfunction "LCD_DATA1_R2_R2") (pintype "bidirectional"))
    )
    (net (code "69") (name "MMC1_CLK") (class "Default")
      (node (ref "R15") (pin "2") (pinfunction "2_2") (pintype "passive"))
      (node (ref "R66") (pin "1") (pinfunction "1_1") (pintype "passive"))
      (node (ref "U13") (pin "M6") (pinfunction "CLK_M6") (pintype "bidirectional"))
    )
    (net (code "70") (name "MMC1_CMD") (class "Default")
      (node (ref "R67") (pin "1") (pinfunction "1_1") (pintype "passive"))
      (node (ref "SIP") (pin "V9") (pinfunction "MMC1_CMD_V9_V9") (pintype "bidirectional"))
      (node (ref "U13") (pin "M5") (pinfunction "CMD_M5") (pintype "bidirectional"))
    )
    (net (code "71") (name "MMC1_DAT0") (class "Default")
      (node (ref "R68") (pin "1") (pinfunction "1_1") (pintype "passive"))
      (node (ref "SIP") (pin "U7") (pinfunction "MMC1_DAT0_U7_U7") (pintype "bidirectional"))
      (node (ref "U13") (pin "A3") (pinfunction "DAT0_A3") (pintype "bidirectional"))
    )
    (net (code "72") (name "MMC1_DAT1") (class "Default")
      (node (ref "R69") (pin "1") (pinfunction "1_1") (pintype "passive"))
      (node (ref "SIP") (pin "V7") (pinfunction "MMC1_DAT1_V7_V7") (pintype "bidirectional"))
      (node (ref "U13") (pin "A4") (pinfunction "DAT1_A4") (pintype "bidirectional"))
    )
    (net (code "73") (name "MMC1_DAT2") (class "Default")
      (node (ref "R70") (pin "1") (pinfunction "1_1") (pintype "passive"))
      (node (ref "SIP") (pin "R8") (pinfunction "MMC1_DAT2_R8_R8") (pintype "bidirectional"))
      (node (ref "U13") (pin "A5") (pinfunction "DAT2_A5") (pintype "bidirectional"))
    )
    (net (code "74") (name "MMC1_DAT3") (class "Default")
      (node (ref "R71") (pin "1") (pinfunction "1_1") (pintype "passive"))
      (node (ref "SIP") (pin "T8") (pinfunction "MMC1_DAT3_T8_T8") (pintype "bidirectional"))
      (node (ref "U13") (pin "B2") (pinfunction "DAT3_B2") (pintype "bidirectional"))
    )
    (net (code "75") (name "MMC1_DAT4") (class "Default")
      (node (ref "R72") (pin "1") (pinfunction "1_1") (pintype "passive"))
      (node (ref "SIP") (pin "U8") (pinfunction "MMC1_DAT4_U8_U8") (pintype "bidirectional"))
      (node (ref "U13") (pin "B3") (pinfunction "DAT4_B3") (pintype "bidirectional"))
    )
    (net (code "76") (name "MMC1_DAT5") (class "Default")
      (node (ref "R73") (pin "1") (pinfunction "1_1") (pintype "passive"))
      (node (ref "SIP") (pin "V8") (pinfunction "MMC1_DAT5_V8_V8") (pintype "bidirectional"))
      (node (ref "U13") (pin "B4") (pinfunction "DAT5_B4") (pintype "bidirectional"))
    )
    (net (code "77") (name "MMC1_DAT6") (class "Default")
      (node (ref "R74") (pin "1") (pinfunction "1_1") (pintype "passive"))
      (node (ref "SIP") (pin "R9") (pinfunction "MMC1_DAT6_R9_R9") (pintype "bidirectional"))
      (node (ref "U13") (pin "B5") (pinfunction "DAT6_B5") (pintype "bidirectional"))
    )
    (net (code "78") (name "MMC1_DAT7") (class "Default")
      (node (ref "R75") (pin "1") (pinfunction "1_1") (pintype "passive"))
      (node (ref "SIP") (pin "T9") (pinfunction "MMC1_DAT7_T9_T9") (pintype "bidirectional"))
      (node (ref "U13") (pin "B6") (pinfunction "DAT7_B6") (pintype "bidirectional"))
    )
    (net (code "79") (name "MMC2_CLK") (class "Default")
      (node (ref "R76") (pin "1") (pinfunction "1_1") (pintype "passive"))
      (node (ref "U9") (pin "13") (pinfunction "B7_13") (pintype "bidirectional"))
    )
    (net (code "80") (name "MMC2_CMD") (class "Default")
      (node (ref "SIP") (pin "J16") (pinfunction "J16_J16") (pintype "bidirectional"))
      (node (ref "U9") (pin "12") (pinfunction "B8_12") (pintype "bidirectional"))
    )
    (net (code "81") (name "MMC2_DAT0") (class "Default")
      (node (ref "SIP") (pin "J17") (pinfunction "J17_J17") (pintype "bidirectional"))
      (node (ref "U9") (pin "14") (pinfunction "B6_14") (pintype "bidirectional"))
    )
    (net (code "82") (name "MMC2_DAT1") (class "Default")
      (node (ref "SIP") (pin "J18") (pinfunction "J18_J18") (pintype "bidirectional"))
      (node (ref "U9") (pin "15") (pinfunction "B5_15") (pintype "bidirectional"))
    )
    (net (code "83") (name "MMC2_DAT2") (class "Default")
      (node (ref "SIP") (pin "K15") (pinfunction "K15_K15") (pintype "bidirectional"))
      (node (ref "U9") (pin "16") (pinfunction "B4_16") (pintype "bidirectional"))
    )
    (net (code "84") (name "MMC2_DAT3") (class "Default")
      (node (ref "SIP") (pin "H16") (pinfunction "H16_H16") (pintype "bidirectional"))
      (node (ref "U9") (pin "17") (pinfunction "B3_17") (pintype "bidirectional"))
    )
    (net (code "85") (name "MODE_BTN") (class "Default")
      (node (ref "MOD") (pin "2") (pinfunction "2_2") (pintype "passive"))
      (node (ref "SIP") (pin "U6") (pinfunction "TIMER6_U6_U6") (pintype "bidirectional"))
    )
    (net (code "86") (name "MOT_STBY") (class "Default")
      (node (ref "H1") (pin "19") (pinfunction "STBY_19") (pintype "bidirectional"))
      (node (ref "H2") (pin "19") (pinfunction "STBY_19") (pintype "bidirectional"))
      (node (ref "SIP") (pin "D14") (pinfunction "GPIO0_20_D14_D14") (pintype "bidirectional"))
    )
    (net (code "87") (name "Net-(0-PadC)") (class "Default")
      (node (ref "0") (pin "C") (pinfunction "C_C") (pintype "passive"))
      (node (ref "R61") (pin "2") (pinfunction "2_2") (pintype "passive"))
    )
    (net (code "88") (name "Net-(1-PadC)") (class "Default")
      (node (ref "1") (pin "C") (pinfunction "C_C") (pintype "passive"))
      (node (ref "R62") (pin "2") (pinfunction "2_2") (pintype "passive"))
    )
    (net (code "89") (name "Net-(2-PadC)") (class "Default")
      (node (ref "2") (pin "C") (pinfunction "C_C") (pintype "passive"))
      (node (ref "R63") (pin "2") (pinfunction "2_2") (pintype "passive"))
    )
    (net (code "90") (name "Net-(3-PadC)") (class "Default")
      (node (ref "3") (pin "C") (pinfunction "C_C") (pintype "passive"))
      (node (ref "R64") (pin "2") (pinfunction "2_2") (pintype "passive"))
    )
    (net (code "91") (name "Net-(5VREG-OUT)") (class "Default")
      (node (ref "5VREG") (pin "2") (pinfunction "OUT_2") (pintype "power_in"))
      (node (ref "D1") (pin "C") (pinfunction "C_C") (pintype "passive"))
      (node (ref "L1") (pin "1") (pinfunction "1_1") (pintype "passive"))
    )
    (net (code "92") (name "Net-(5VREG-VIN)") (class "Default")
      (node (ref "5VREG") (pin "1") (pinfunction "VIN_1") (pintype "input"))
      (node (ref "C3") (pin "1") (pinfunction "1_1") (pintype "passive"))
      (node (ref "D2") (pin "C") (pinfunction "C_C") (pintype "passive"))
      (node (ref "D3") (pin "C") (pinfunction "C_C") (pintype "passive"))
    )
    (net (code "93") (name "Net-(6VREG-BS)") (class "Default")
      (node (ref "6VREG") (pin "2") (pinfunction "BS_2") (pintype "bidirectional"))
      (node (ref "C22") (pin "1") (pinfunction "1_1") (pintype "passive"))
    )
    (net (code "94") (name "Net-(6VREG-COMP)") (class "Default")
      (node (ref "6VREG") (pin "5") (pinfunction "COMP_5") (pintype "bidirectional"))
      (node (ref "R45") (pin "2") (pinfunction "2_2") (pintype "passive"))
    )
    (net (code "95") (name "Net-(6VREG-FB)") (class "Default")
      (node (ref "6VREG") (pin "6") (pinfunction "FB_6") (pintype "bidirectional"))
      (node (ref "R48") (pin "2") (pinfunction "2_2") (pintype "passive"))
      (node (ref "R49") (pin "1") (pinfunction "1_1") (pintype "passive"))
    )
    (net (code "96") (name "Net-(6VREG-FSW)") (class "Default")
      (node (ref "6VREG") (pin "4") (pinfunction "FSW_4") (pintype "bidirectional"))
      (node (ref "R47") (pin "2") (pinfunction "2_2") (pintype "passive"))
    )
    (net (code "97") (name "Net-(6VREG-LX)") (class "Default")
      (node (ref "6VREG") (pin "1") (pinfunction "LX_1") (pintype "bidirectional"))
      (node (ref "C22") (pin "2") (pinfunction "2_2") (pintype "passive"))
      (node (ref "D9") (pin "C") (pinfunction "C_C") (pintype "passive"))
      (node (ref "L3") (pin "1") (pinfunction "1_1") (pintype "passive"))
    )
    (net (code "98") (name "Net-(6VREG-SS)") (class "Default")
      (node (ref "6VREG") (pin "7") (pinfunction "SS_7") (pintype "bidirectional"))
      (node (ref "C21") (pin "2") (pinfunction "2_2") (pintype "passive"))
    )
    (net (code "99") (name "Net-(ANT1-PadSIG)") (class "Default")
      (node (ref "ANT1") (pin "SIG") (pinfunction "SIG_SIG") (pintype "bidirectional"))
      (node (ref "C48") (pin "1") (pinfunction "1_1") (pintype "passive"))
    )
    (net (code "100") (name "Net-(ANT2-PadSIG)") (class "Default")
      (node (ref "ANT2") (pin "SIG") (pinfunction "SIG_SIG") (pintype "bidirectional"))
      (node (ref "C58") (pin "1") (pinfunction "1_1") (pintype "passive"))
    )
    (net (code "101") (name "Net-(B0-PadC)") (class "Default")
      (node (ref "B0") (pin "C") (pinfunction "C_C") (pintype "passive"))
      (node (ref "R31") (pin "1") (pinfunction "1_1") (pintype "passive"))
    )
    (net (code "102") (name "Net-(B1-PadC)") (class "Default")
      (node (ref "B1") (pin "C") (pinfunction "C_C") (pintype "passive"))
      (node (ref "R29") (pin "1") (pinfunction "1_1") (pintype "passive"))
    )
    (net (code "103") (name "Net-(B2-PadC)") (class "Default")
      (node (ref "B2") (pin "C") (pinfunction "C_C") (pintype "passive"))
      (node (ref "R33") (pin "1") (pinfunction "1_1") (pintype "passive"))
    )
    (net (code "104") (name "Net-(B3-PadC)") (class "Default")
      (node (ref "B3") (pin "C") (pinfunction "C_C") (pintype "passive"))
      (node (ref "R32") (pin "1") (pinfunction "1_1") (pintype "passive"))
    )
    (net (code "105") (name "Net-(BAL-CD)") (class "Default")
      (node (ref "BAL") (pin "4") (pinfunction "CD_4") (pintype "bidirectional"))
      (node (ref "C19") (pin "1") (pinfunction "1_1") (pintype "passive"))
    )
    (net (code "106") (name "Net-(BAL-OUT)") (class "Default")
      (node (ref "BAL") (pin "8") (pinfunction "OUT_8") (pintype "bidirectional"))
      (node (ref "R7") (pin "1") (pinfunction "1_1") (pintype "passive"))
    )
    (net (code "107") (name "Net-(BAL-VC1)") (class "Default")
      (node (ref "BAL") (pin "2") (pinfunction "VC1_2") (pintype "bidirectional"))
      (node (ref "C17") (pin "1") (pinfunction "1_1") (pintype "passive"))
      (node (ref "C18") (pin "2") (pinfunction "2_2") (pintype "passive"))
      (node (ref "R30") (pin "2") (pinfunction "2_2") (pintype "passive"))
    )
    (net (code "108") (name "Net-(BAL-VC1_CB)") (class "Default")
      (node (ref "BAL") (pin "3") (pinfunction "VC1_CB_3") (pintype "bidirectional"))
      (node (ref "R27") (pin "2") (pinfunction "2_2") (pintype "passive"))
    )
    (net (code "109") (name "Net-(BAL-VC2)") (class "Default")
      (node (ref "BAL") (pin "1") (pinfunction "VC2_1") (pintype "bidirectional"))
      (node (ref "C17") (pin "2") (pinfunction "2_2") (pintype "passive"))
      (node (ref "R28") (pin "2") (pinfunction "2_2") (pintype "passive"))
    )
    (net (code "110") (name "Net-(BAL-VDD)") (class "Default")
      (node (ref "BAL") (pin "7") (pinfunction "VDD_7") (pintype "bidirectional"))
      (node (ref "C1") (pin "1") (pinfunction "1_1") (pintype "passive"))
      (node (ref "R34") (pin "2") (pinfunction "2_2") (pintype "passive"))
    )
    (net (code "111") (name "Net-(C23-Pad2)") (class "Default")
      (node (ref "C23") (pin "2") (pinfunction "2_2") (pintype "passive"))
      (node (ref "J2") (pin "P$10") (pinfunction "PWR_P$10") (pintype "bidirectional"))
      (node (ref "J2") (pin "P$11") (pinfunction "PWR_P$11") (pintype "bidirectional"))
      (node (ref "J2") (pin "P$12") (pinfunction "PWR_P$12") (pintype "bidirectional"))
      (node (ref "J2") (pin "P$21") (pinfunction "PWR_P$21") (pintype "bidirectional"))
      (node (ref "J2") (pin "P$22") (pinfunction "PWR_P$22") (pintype "bidirectional"))
      (node (ref "J2") (pin "P$7") (pinfunction "PWR_P$7") (pintype "bidirectional"))
      (node (ref "J2") (pin "P$8") (pinfunction "PWR_P$8") (pintype "bidirectional"))
      (node (ref "J2") (pin "P$9") (pinfunction "PWR_P$9") (pintype "bidirectional"))
      (node (ref "L3") (pin "2") (pinfunction "2_2") (pintype "passive"))
      (node (ref "R49") (pin "2") (pinfunction "2_2") (pintype "passive"))
    )
    (net (code "112") (name "Net-(C24-Pad2)") (class "Default")
      (node (ref "C24") (pin "2") (pinfunction "2_2") (pintype "passive"))
      (node (ref "R45") (pin "1") (pinfunction "1_1") (pintype "passive"))
    )
    (net (code "113") (name "Net-(CHG-PadC)") (class "Default")
      (node (ref "CHG") (pin "C") (pinfunction "C_C") (pintype "passive"))
      (node (ref "R3") (pin "2") (pinfunction "2_2") (pintype "passive"))
    )
    (net (code "114") (name "Net-(CHGIC-BST)") (class "Default")
      (node (ref "C14") (pin "1") (pinfunction "1_1") (pintype "passive"))
      (node (ref "CHGIC") (pin "15") (pinfunction "BST_15") (pintype "bidirectional"))
    )
    (net (code "115") (name "Net-(CHGIC-CHGOK)") (class "Default")
      (node (ref "CHGIC") (pin "11") (pinfunction "CHGOK_11") (pintype "bidirectional"))
      (node (ref "R3") (pin "1") (pinfunction "1_1") (pintype "passive"))
    )
    (net (code "116") (name "Net-(CHGIC-CSP)") (class "Default")
      (node (ref "CHGIC") (pin "10") (pinfunction "CSP_10") (pintype "bidirectional"))
      (node (ref "L2") (pin "2") (pinfunction "2_2") (pintype "passive"))
      (node (ref "R4") (pin "2") (pinfunction "2_2") (pintype "passive"))
    )
    (net (code "117") (name "Net-(CHGIC-NTC)") (class "Default")
      (node (ref "CHGIC") (pin "13") (pinfunction "NTC_13") (pintype "bidirectional"))
      (node (ref "R5") (pin "1") (pinfunction "1_1") (pintype "passive"))
      (node (ref "R6") (pin "2") (pinfunction "2_2") (pintype "passive"))
    )
    (net (code "118") (name "Net-(CHGIC-SW)") (class "Default")
      (node (ref "C14") (pin "2") (pinfunction "2_2") (pintype "passive"))
      (node (ref "CHGIC") (pin "1") (pinfunction "SW_1") (pintype "bidirectional"))
      (node (ref "L2") (pin "1") (pinfunction "1_1") (pintype "passive"))
    )
    (net (code "119") (name "Net-(CHGIC-TMR)") (class "Default")
      (node (ref "C10") (pin "2") (pinfunction "2_2") (pintype "passive"))
      (node (ref "CHGIC") (pin "14") (pinfunction "TMR_14") (pintype "bidirectional"))
    )
    (net (code "120") (name "Net-(G-PadC)") (class "Default")
      (node (ref "G") (pin "C") (pinfunction "C_C") (pintype "passive"))
      (node (ref "R22") (pin "1") (pinfunction "1_1") (pintype "passive"))
    )
    (net (code "121") (name "Net-(IMU-REGOUT)") (class "Default")
      (node (ref "C6") (pin "1") (pinfunction "1_1") (pintype "passive"))
      (node (ref "IMU") (pin "10") (pinfunction "REGOUT_10") (pintype "bidirectional"))
    )
    (net (code "122") (name "Net-(J2-1)") (class "Default")
      (node (ref "J2") (pin "P$1") (pinfunction "1_P$1") (pintype "bidirectional"))
      (node (ref "R36") (pin "2") (pinfunction "2_2") (pintype "passive"))
    )
    (net (code "123") (name "Net-(J2-2)") (class "Default")
      (node (ref "J2") (pin "P$2") (pinfunction "2_P$2") (pintype "bidirectional"))
      (node (ref "R37") (pin "2") (pinfunction "2_2") (pintype "passive"))
    )
    (net (code "124") (name "Net-(J2-3)") (class "Default")
      (node (ref "J2") (pin "P$3") (pinfunction "3_P$3") (pintype "bidirectional"))
      (node (ref "R38") (pin "2") (pinfunction "2_2") (pintype "passive"))
    )
    (net (code "125") (name "Net-(J2-4)") (class "Default")
      (node (ref "J2") (pin "P$4") (pinfunction "4_P$4") (pintype "bidirectional"))
      (node (ref "R39") (pin "2") (pinfunction "2_2") (pintype "passive"))
    )
    (net (code "126") (name "Net-(J2-5)") (class "Default")
      (node (ref "J2") (pin "P$5") (pinfunction "5_P$5") (pintype "bidirectional"))
      (node (ref "R40") (pin "2") (pinfunction "2_2") (pintype "passive"))
    )
    (net (code "127") (name "Net-(J2-6)") (class "Default")
      (node (ref "J2") (pin "P$6") (pinfunction "6_P$6") (pintype "bidirectional"))
      (node (ref "R41") (pin "2") (pinfunction "2_2") (pintype "passive"))
    )
    (net (code "128") (name "Net-(J2-7)") (class "Default")
      (node (ref "J2") (pin "P$19") (pinfunction "7_P$19") (pintype "bidirectional"))
      (node (ref "R42") (pin "2") (pinfunction "2_2") (pintype "passive"))
    )
    (net (code "129") (name "Net-(J2-8)") (class "Default")
      (node (ref "J2") (pin "P$20") (pinfunction "8_P$20") (pintype "bidirectional"))
      (node (ref "R43") (pin "2") (pinfunction "2_2") (pintype "passive"))
    )
    (net (code "130") (name "Net-(M1-1)") (class "Default")
      (node (ref "H1") (pin "5") (pinfunction "A02_5") (pintype "bidirectional"))
      (node (ref "H1") (pin "6") (pinfunction "A02_6") (pintype "bidirectional"))
      (node (ref "M1") (pin "P$1") (pinfunction "1_P$1") (pintype "bidirectional"))
    )
    (net (code "131") (name "Net-(M1-2)") (class "Default")
      (node (ref "H1") (pin "1") (pinfunction "A01_1") (pintype "bidirectional"))
      (node (ref "H1") (pin "2") (pinfunction "A01_2") (pintype "bidirectional"))
      (node (ref "M1") (pin "P$2") (pinfunction "2_P$2") (pintype "bidirectional"))
    )
    (net (code "132") (name "Net-(M2-1)") (class "Default")
      (node (ref "H1") (pin "11") (pinfunction "B01_11") (pintype "bidirectional"))
      (node (ref "H1") (pin "12") (pinfunction "B01_12") (pintype "bidirectional"))
      (node (ref "M2") (pin "P$1") (pinfunction "1_P$1") (pintype "bidirectional"))
    )
    (net (code "133") (name "Net-(M2-2)") (class "Default")
      (node (ref "H1") (pin "7") (pinfunction "B02_7") (pintype "bidirectional"))
      (node (ref "H1") (pin "8") (pinfunction "B02_8") (pintype "bidirectional"))
      (node (ref "M2") (pin "P$2") (pinfunction "2_P$2") (pintype "bidirectional"))
    )
    (net (code "134") (name "Net-(M3-1)") (class "Default")
      (node (ref "H2") (pin "1") (pinfunction "A01_1") (pintype "bidirectional"))
      (node (ref "H2") (pin "2") (pinfunction "A01_2") (pintype "bidirectional"))
      (node (ref "M3") (pin "P$1") (pinfunction "1_P$1") (pintype "bidirectional"))
    )
    (net (code "135") (name "Net-(M3-2)") (class "Default")
      (node (ref "H2") (pin "5") (pinfunction "A02_5") (pintype "bidirectional"))
      (node (ref "H2") (pin "6") (pinfunction "A02_6") (pintype "bidirectional"))
      (node (ref "M3") (pin "P$2") (pinfunction "2_P$2") (pintype "bidirectional"))
    )
    (net (code "136") (name "Net-(M4-1)") (class "Default")
      (node (ref "H2") (pin "7") (pinfunction "B02_7") (pintype "bidirectional"))
      (node (ref "H2") (pin "8") (pinfunction "B02_8") (pintype "bidirectional"))
      (node (ref "M4") (pin "P$1") (pinfunction "1_P$1") (pintype "bidirectional"))
    )
    (net (code "137") (name "Net-(M4-2)") (class "Default")
      (node (ref "H2") (pin "11") (pinfunction "B01_11") (pintype "bidirectional"))
      (node (ref "H2") (pin "12") (pinfunction "B01_12") (pintype "bidirectional"))
      (node (ref "M4") (pin "P$2") (pinfunction "2_P$2") (pintype "bidirectional"))
    )
    (net (code "138") (name "Net-(OSC1-EN)") (class "Default")
      (node (ref "OSC1") (pin "1") (pinfunction "EN_1") (pintype "bidirectional"))
      (node (ref "R90") (pin "1") (pinfunction "1_1") (pintype "passive"))
    )
    (net (code "139") (name "Net-(PROT-VDD)") (class "Default")
      (node (ref "C15") (pin "2") (pinfunction "2_2") (pintype "passive"))
      (node (ref "PROT") (pin "5") (pinfunction "VDD_5") (pintype "bidirectional"))
      (node (ref "R44") (pin "2") (pinfunction "2_2") (pintype "passive"))
    )
    (net (code "140") (name "Net-(R-PadC)") (class "Default")
      (node (ref "R") (pin "C") (pinfunction "C_C") (pintype "passive"))
      (node (ref "R21") (pin "1") (pinfunction "1_1") (pintype "passive"))
    )
    (net (code "141") (name "Net-(R76-Pad2)") (class "Default")
      (node (ref "R76") (pin "2") (pinfunction "2_2") (pintype "passive"))
      (node (ref "SIP") (pin "L15") (pinfunction "L15_L15") (pintype "bidirectional"))
    )
    (net (code "142") (name "Net-(R91-Pad1)") (class "Default")
      (node (ref "R91") (pin "1") (pinfunction "1_1") (pintype "passive"))
      (node (ref "WIFI") (pin "C") (pinfunction "C_C") (pintype "passive"))
    )
    (net (code "143") (name "Net-(SIPA-PMIC_IN_PWR_EN)") (class "Default")
      (node (ref "SIP") (pin "C6") (pinfunction "PMIC_POWER_EN_C6") (pintype "output"))
      (node (ref "SIP") (pin "D19") (pinfunction "PMIC_IN_PWR_EN_D19") (pintype "input"))
      (node (ref "TP5") (pin "TP") (pinfunction "TP_TP") (pintype "input"))
    )
    (net (code "144") (name "Net-(SIPB-JTAG_EMU0)") (class "Default")
      (node (ref "EMU1") (pin "TP") (pinfunction "TP_TP") (pintype "input"))
      (node (ref "SIP") (pin "C14") (pinfunction "JTAG_EMU0_C14") (pintype "bidirectional"))
    )
    (net (code "145") (name "Net-(SIPB-JTAG_EMU1)") (class "Default")
      (node (ref "EMU0") (pin "TP") (pinfunction "TP_TP") (pintype "input"))
      (node (ref "SIP") (pin "B14") (pinfunction "JTAG_EMU1_B14") (pintype "bidirectional"))
    )
    (net (code "146") (name "Net-(SIPB-JTAG_TCK)") (class "Default")
      (node (ref "SIP") (pin "A12") (pinfunction "JTAG_TCK_A12") (pintype "bidirectional"))
      (node (ref "TCK") (pin "TP") (pinfunction "TP_TP") (pintype "input"))
    )
    (net (code "147") (name "Net-(SIPB-JTAG_TDI)") (class "Default")
      (node (ref "SIP") (pin "B11") (pinfunction "JTAG_TDI_B11") (pintype "bidirectional"))
      (node (ref "TDI") (pin "TP") (pinfunction "TP_TP") (pintype "input"))
    )
    (net (code "148") (name "Net-(SIPB-JTAG_TDO)") (class "Default")
      (node (ref "SIP") (pin "A11") (pinfunction "JTAG_TDO_A11") (pintype "bidirectional"))
      (node (ref "TDO") (pin "TP") (pinfunction "TP_TP") (pintype "input"))
    )
    (net (code "149") (name "Net-(SIPB-JTAG_TMS)") (class "Default")
      (node (ref "SIP") (pin "C11") (pinfunction "JTAG_TMS_C11") (pintype "bidirectional"))
      (node (ref "TMS") (pin "TP") (pinfunction "TP_TP") (pintype "input"))
    )
    (net (code "150") (name "Net-(SIPB-JTAG_TRSTN)") (class "Default")
      (node (ref "R59") (pin "2") (pinfunction "2_2") (pintype "passive"))
      (node (ref "SIP") (pin "B10") (pinfunction "JTAG_TRSTN_B10") (pintype "bidirectional"))
      (node (ref "TRSTN") (pin "TP") (pinfunction "TP_TP") (pintype "input"))
    )
    (net (code "151") (name "Net-(SIPB-MMC0_CD_C15)") (class "Default")
      (node (ref "R65") (pin "1") (pinfunction "1_1") (pintype "passive"))
      (node (ref "SIP") (pin "C15") (pinfunction "MMC0_CD_C15_C15") (pintype "bidirectional"))
      (node (ref "X2") (pin "CD") (pinfunction "CD#_CD") (pintype "bidirectional"))
    )
    (net (code "152") (name "Net-(SIPB-MMC0_CLK_G17)") (class "Default")
      (node (ref "R57") (pin "1") (pinfunction "1_1") (pintype "passive"))
      (node (ref "SIP") (pin "G17") (pinfunction "MMC0_CLK_G17_G17") (pintype "bidirectional"))
      (node (ref "X2") (pin "5") (pinfunction "CLK_5") (pintype "bidirectional"))
    )
    (net (code "153") (name "Net-(SIPB-MMC0_CMD_G18)") (class "Default")
      (node (ref "R56") (pin "1") (pinfunction "1_1") (pintype "passive"))
      (node (ref "SIP") (pin "G18") (pinfunction "MMC0_CMD_G18_G18") (pintype "bidirectional"))
      (node (ref "X2") (pin "3") (pinfunction "CMD/DI_3") (pintype "bidirectional"))
    )
    (net (code "154") (name "Net-(SIPB-MMC0_DAT0_G16)") (class "Default")
      (node (ref "R55") (pin "1") (pinfunction "1_1") (pintype "passive"))
      (node (ref "SIP") (pin "G16") (pinfunction "MMC0_DAT0_G16_G16") (pintype "bidirectional"))
      (node (ref "X2") (pin "7") (pinfunction "DAT0/DO_7") (pintype "bidirectional"))
    )
    (net (code "155") (name "Net-(SIPB-MMC0_DAT1_G15)") (class "Default")
      (node (ref "R54") (pin "1") (pinfunction "1_1") (pintype "passive"))
      (node (ref "SIP") (pin "G15") (pinfunction "MMC0_DAT1_G15_G15") (pintype "bidirectional"))
      (node (ref "X2") (pin "8") (pinfunction "DAT1_8") (pintype "bidirectional"))
    )
    (net (code "156") (name "Net-(SIPB-MMC0_DAT2_F18)") (class "Default")
      (node (ref "R35") (pin "1") (pinfunction "1_1") (pintype "passive"))
      (node (ref "SIP") (pin "F18") (pinfunction "MMC0_DAT2_F18_F18") (pintype "bidirectional"))
      (node (ref "X2") (pin "1") (pinfunction "DAT2_1") (pintype "bidirectional"))
    )
    (net (code "157") (name "Net-(SIPB-MMC0_DAT3_F17)") (class "Default")
      (node (ref "R26") (pin "1") (pinfunction "1_1") (pintype "passive"))
      (node (ref "SIP") (pin "F17") (pinfunction "MMC0_DAT3_F17_F17") (pintype "bidirectional"))
      (node (ref "X2") (pin "2") (pinfunction "DAT3/CS_2") (pintype "bidirectional"))
    )
    (net (code "158") (name "Net-(SIPB-MMC1_CLK_U9)") (class "Default")
      (node (ref "R15") (pin "1") (pinfunction "1_1") (pintype "passive"))
      (node (ref "SIP") (pin "U9") (pinfunction "MMC1_CLK_U9_U9") (pintype "bidirectional"))
    )
    (net (code "159") (name "Net-(SIPB-OSC0_GND)") (class "Default")
      (node (ref "C29") (pin "2") (pinfunction "2_2") (pintype "passive"))
      (node (ref "C30") (pin "2") (pinfunction "2_2") (pintype "passive"))
      (node (ref "SIP") (pin "L20") (pinfunction "OSC0_GND_L20") (pintype "bidirectional"))
    )
    (net (code "160") (name "Net-(SIPB-OSC0_IN)") (class "Default")
      (node (ref "C30") (pin "1") (pinfunction "1_1") (pintype "passive"))
      (node (ref "R20") (pin "2") (pinfunction "2_2") (pintype "passive"))
      (node (ref "SIP") (pin "M20") (pinfunction "OSC0_IN_M20") (pintype "bidirectional"))
      (node (ref "Y1") (pin "2") (pinfunction "P$2_2") (pintype "passive"))
    )
    (net (code "161") (name "Net-(SIPB-OSC0_OUT)") (class "Default")
      (node (ref "C29") (pin "1") (pinfunction "1_1") (pintype "passive"))
      (node (ref "R20") (pin "1") (pinfunction "1_1") (pintype "passive"))
      (node (ref "SIP") (pin "K20") (pinfunction "OSC0_OUT_K20") (pintype "bidirectional"))
      (node (ref "Y1") (pin "1") (pinfunction "P$1_1") (pintype "passive"))
    )
    (net (code "162") (name "Net-(SIPB-OSC1_GND)") (class "Default")
      (node (ref "C31") (pin "2") (pinfunction "2_2") (pintype "passive"))
      (node (ref "C32") (pin "1") (pinfunction "1_1") (pintype "passive"))
      (node (ref "SIP") (pin "G20") (pinfunction "OSC1_GND_G20") (pintype "bidirectional"))
    )
    (net (code "163") (name "Net-(SIPB-OSC1_IN)") (class "Default")
      (node (ref "C31") (pin "1") (pinfunction "1_1") (pintype "passive"))
      (node (ref "R18") (pin "2") (pinfunction "2_2") (pintype "passive"))
      (node (ref "SIP") (pin "H20") (pinfunction "OSC1_IN_H20") (pintype "bidirectional"))
      (node (ref "Y2") (pin "P$2") (pinfunction "P$2_P$2") (pintype "passive"))
    )
    (net (code "164") (name "Net-(SIPB-OSC1_OUT)") (class "Default")
      (node (ref "C32") (pin "2") (pinfunction "2_2") (pintype "passive"))
      (node (ref "R18") (pin "1") (pinfunction "1_1") (pintype "passive"))
      (node (ref "SIP") (pin "F20") (pinfunction "OSC1_OUT_F20") (pintype "bidirectional"))
      (node (ref "Y2") (pin "P$1") (pinfunction "P$1_P$1") (pintype "passive"))
    )
    (net (code "165") (name "Net-(SIPC-ADC_VREFP)") (class "Default")
      (node (ref "C42") (pin "1") (pinfunction "1_1") (pintype "passive"))
      (node (ref "C43") (pin "1") (pinfunction "1_1") (pintype "passive"))
      (node (ref "R111") (pin "2") (pinfunction "2_2") (pintype "passive"))
      (node (ref "SIP") (pin "B9") (pinfunction "ADC_VREFP_B9") (pintype "bidirectional"))
    )
    (net (code "166") (name "Net-(SIPC-AIN7)") (class "Default")
      (node (ref "R109") (pin "2") (pinfunction "2_2") (pintype "passive"))
      (node (ref "R110") (pin "1") (pinfunction "1_1") (pintype "passive"))
      (node (ref "SIP") (pin "C9") (pinfunction "AIN7_C9") (pintype "bidirectional"))
    )
    (net (code "167") (name "Net-(SIPC-LCD_DATA11_U4)") (class "Default")
      (node (ref "R135") (pin "2") (pinfunction "2_2") (pintype "passive"))
      (node (ref "SIP") (pin "U4") (pinfunction "LCD_DATA11_U4_U4") (pintype "bidirectional"))
    )
    (net (code "168") (name "Net-(SIPC-USB0_VBUS)") (class "Default")
      (node (ref "R149") (pin "1") (pinfunction "1_1") (pintype "passive"))
      (node (ref "SIP") (pin "P15") (pinfunction "USB0_VBUS_P15") (pintype "bidirectional"))
    )
    (net (code "169") (name "Net-(SIPC-USB1_ID)") (class "Default")
      (node (ref "R150") (pin "1") (pinfunction "1_1") (pintype "passive"))
      (node (ref "SIP") (pin "P17") (pinfunction "USB1_ID_P17") (pintype "bidirectional"))
    )
    (net (code "170") (name "Net-(SIPC-USB1_VBUS)") (class "Default")
      (node (ref "R156") (pin "1") (pinfunction "1_1") (pintype "passive"))
      (node (ref "SIP") (pin "T18") (pinfunction "USB1_VBUS_T18") (pintype "bidirectional"))
    )
    (net (code "171") (name "Net-(SIPE-RTC_KALDO_ENN)") (class "Default")
      (node (ref "R158") (pin "1") (pinfunction "1_1") (pintype "passive"))
      (node (ref "SIP") (pin "B4") (pinfunction "RTC_KALDO_ENN_B4") (pintype "bidirectional"))
    )
    (net (code "172") (name "Net-(U5-WP)") (class "Default")
      (node (ref "R58") (pin "1") (pinfunction "1_1") (pintype "passive"))
      (node (ref "U5") (pin "5") (pinfunction "WP_5") (pintype "input"))
      (node (ref "WP") (pin "P$1") (pinfunction "TP_P$1") (pintype "bidirectional"))
    )
    (net (code "173") (name "Net-(U7-BT_AUD_CLK)") (class "Default")
      (node (ref "R124") (pin "2") (pinfunction "2_2") (pintype "passive"))
      (node (ref "U7") (pin "60") (pinfunction "BT_AUD_CLK_60") (pintype "bidirectional"))
    )
    (net (code "174") (name "Net-(U7-BT_AUD_FSYNC)") (class "Default")
      (node (ref "R123") (pin "2") (pinfunction "2_2") (pintype "passive"))
      (node (ref "U7") (pin "58") (pinfunction "BT_AUD_FSYNC_58") (pintype "bidirectional"))
    )
    (net (code "175") (name "Net-(U7-BT_AUD_IN)") (class "Default")
      (node (ref "R97") (pin "2") (pinfunction "2_2") (pintype "passive"))
      (node (ref "U7") (pin "56") (pinfunction "BT_AUD_IN_56") (pintype "bidirectional"))
    )
    (net (code "176") (name "Net-(U7-BT_AUD_OUT)") (class "Default")
      (node (ref "R100") (pin "2") (pinfunction "2_2") (pintype "passive"))
      (node (ref "U7") (pin "57") (pinfunction "BT_AUD_OUT_57") (pintype "bidirectional"))
    )
    (net (code "177") (name "Net-(U7-BT_HCI_CTS)") (class "Default")
      (node (ref "R86") (pin "2") (pinfunction "2_2") (pintype "passive"))
      (node (ref "U7") (pin "51") (pinfunction "BT_HCI_CTS_51") (pintype "bidirectional"))
    )
    (net (code "178") (name "Net-(U7-BT_HCI_RTS)") (class "Default")
      (node (ref "R85") (pin "2") (pinfunction "2_2") (pintype "passive"))
      (node (ref "U7") (pin "50") (pinfunction "BT_HCI_RTS_50") (pintype "bidirectional"))
    )
    (net (code "179") (name "Net-(U7-BT_HCI_RX)") (class "Default")
      (node (ref "R96") (pin "2") (pinfunction "2_2") (pintype "passive"))
      (node (ref "U7") (pin "53") (pinfunction "BT_HCI_RX_53") (pintype "bidirectional"))
    )
    (net (code "180") (name "Net-(U7-BT_HCI_TX)") (class "Default")
      (node (ref "R92") (pin "2") (pinfunction "2_2") (pintype "passive"))
      (node (ref "U7") (pin "52") (pinfunction "BT_HCI_TX_52") (pintype "bidirectional"))
    )
    (net (code "181") (name "Net-(U7-RF_ANT1)") (class "Default")
      (node (ref "C48") (pin "2") (pinfunction "2_2") (pintype "passive"))
      (node (ref "U7") (pin "32") (pinfunction "RF_ANT1_32") (pintype "bidirectional"))
    )
    (net (code "182") (name "Net-(U7-RF_ANT2)") (class "Default")
      (node (ref "C58") (pin "2") (pinfunction "2_2") (pintype "passive"))
      (node (ref "U7") (pin "18") (pinfunction "RF_ANT2_18") (pintype "bidirectional"))
    )
    (net (code "183") (name "Net-(U7-WLAN_IRQ)") (class "Default")
      (node (ref "R84") (pin "2") (pinfunction "2_2") (pintype "passive"))
      (node (ref "R9") (pin "2") (pinfunction "2_2") (pintype "passive"))
      (node (ref "U7") (pin "14") (pinfunction "WLAN_IRQ_14") (pintype "bidirectional"))
    )
    (net (code "184") (name "Net-(U7-WL_SDIO_CLK)") (class "Default")
      (node (ref "R78") (pin "2") (pinfunction "2_2") (pintype "passive"))
      (node (ref "U7") (pin "8") (pinfunction "WL_SDIO_CLK_8") (pintype "bidirectional"))
    )
    (net (code "185") (name "Net-(U7-WL_SDIO_CMD)") (class "Default")
      (node (ref "R79") (pin "2") (pinfunction "2_2") (pintype "passive"))
      (node (ref "U7") (pin "6") (pinfunction "WL_SDIO_CMD_6") (pintype "bidirectional"))
    )
    (net (code "186") (name "Net-(U7-WL_SDIO_D0)") (class "Default")
      (node (ref "R80") (pin "2") (pinfunction "2_2") (pintype "passive"))
      (node (ref "U7") (pin "10") (pinfunction "WL_SDIO_D0_10") (pintype "bidirectional"))
    )
    (net (code "187") (name "Net-(U7-WL_SDIO_D1)") (class "Default")
      (node (ref "R81") (pin "2") (pinfunction "2_2") (pintype "passive"))
      (node (ref "U7") (pin "11") (pinfunction "WL_SDIO_D1_11") (pintype "bidirectional"))
    )
    (net (code "188") (name "Net-(U7-WL_SDIO_D2)") (class "Default")
      (node (ref "R82") (pin "2") (pinfunction "2_2") (pintype "passive"))
      (node (ref "U7") (pin "12") (pinfunction "WL_SDIO_D2_12") (pintype "bidirectional"))
    )
    (net (code "189") (name "Net-(U7-WL_SDIO_D3)") (class "Default")
      (node (ref "R83") (pin "2") (pinfunction "2_2") (pintype "passive"))
      (node (ref "U7") (pin "13") (pinfunction "WL_SDIO_D3_13") (pintype "bidirectional"))
    )
    (net (code "190") (name "Net-(U10-OE)") (class "Default")
      (node (ref "R106") (pin "2") (pinfunction "2_2") (pintype "passive"))
      (node (ref "R93") (pin "2") (pinfunction "2_2") (pintype "passive"))
      (node (ref "U10") (pin "10") (pinfunction "OE_10") (pintype "bidirectional"))
      (node (ref "U2") (pin "1") (pinfunction "OE_1") (pintype "input"))
      (node (ref "U9") (pin "10") (pinfunction "OE_10") (pintype "bidirectional"))
    )
    (net (code "191") (name "Net-(U13-VDDI)") (class "Default")
      (node (ref "C36") (pin "1") (pinfunction "1_1") (pintype "passive"))
      (node (ref "U13") (pin "C2") (pinfunction "VDDI_C2") (pintype "bidirectional"))
    )
    (net (code "192") (name "Net-(X3-GND)") (class "Default")
      (node (ref "L4") (pin "2") (pinfunction "2_2") (pintype "passive"))
      (node (ref "X3") (pin "4") (pinfunction "GND_4") (pintype "bidirectional"))
    )
    (net (code "193") (name "Net-(X3-VBUS)") (class "Default")
      (node (ref "L5") (pin "2") (pinfunction "2_2") (pintype "passive"))
      (node (ref "X3") (pin "1") (pinfunction "VBUS_1") (pintype "bidirectional"))
    )
    (net (code "194") (name "PAUSE_BTN") (class "Default")
      (node (ref "PAU") (pin "2") (pinfunction "2_2") (pintype "passive"))
      (node (ref "SIP") (pin "T6") (pinfunction "TIMER5_T6_T6") (pintype "bidirectional"))
    )
    (net (code "195") (name "PMIC_INT") (class "Default")
      (node (ref "SIP") (pin "B18") (pinfunction "EXTINTN_B18") (pintype "bidirectional"))
      (node (ref "SIP") (pin "B19") (pinfunction "PMIC_OUT_NINT_B19") (pintype "output"))
    )
    (net (code "196") (name "PMIC_NWAKEUP") (class "Default")
      (node (ref "SIP") (pin "A19") (pinfunction "PMIC_OUT_NWAKEUP_A19") (pintype "output"))
      (node (ref "SIP") (pin "C5") (pinfunction "EXT_WAKEUP_C5") (pintype "bidirectional"))
    )
    (net (code "197") (name "PMIC_PGOOD") (class "Default")
      (node (ref "SIP") (pin "A20") (pinfunction "PMIC_OUT_PGOOD_A20") (pintype "output"))
      (node (ref "SIP") (pin "B15") (pinfunction "PWRONRSTN_B15") (pintype "bidirectional"))
      (node (ref "U6") (pin "2") (pinfunction "A_2") (pintype "input"))
    )
    (net (code "198") (name "POWER_BTN") (class "Default")
      (node (ref "POW") (pin "2") (pinfunction "2_2") (pintype "passive"))
      (node (ref "SIP") (pin "D20") (pinfunction "PMIC_IN_PB_IN_D20") (pintype "bidirectional"))
    )
    (net (code "199") (name "PRU_E_A") (class "Default")
      (node (ref "E4") (pin "3") (pinfunction "3_3") (pintype "bidirectional"))
      (node (ref "SIP") (pin "V13") (pinfunction "GPIO1_14_V13_V13") (pintype "bidirectional"))
    )
    (net (code "200") (name "PRU_E_B") (class "Default")
      (node (ref "E4") (pin "4") (pinfunction "4_4") (pintype "bidirectional"))
      (node (ref "SIP") (pin "U13") (pinfunction "GPIO1_15_U13_U13") (pintype "bidirectional"))
    )
    (net (code "201") (name "PWM_1A") (class "Default")
      (node (ref "H1") (pin "23") (pinfunction "PWMA_23") (pintype "bidirectional"))
      (node (ref "SIP") (pin "U14") (pinfunction "EHRPWM1A_U14_U14") (pintype "bidirectional"))
    )
    (net (code "202") (name "PWM_1B") (class "Default")
      (node (ref "H1") (pin "15") (pinfunction "PWMB_15") (pintype "bidirectional"))
      (node (ref "SIP") (pin "T14") (pinfunction "EHRPWM1B_T14_T14") (pintype "bidirectional"))
    )
    (net (code "203") (name "PWM_2A") (class "Default")
      (node (ref "H2") (pin "23") (pinfunction "PWMA_23") (pintype "bidirectional"))
      (node (ref "SIP") (pin "U10") (pinfunction "EHRPWM2A_U10_U10") (pintype "bidirectional"))
    )
    (net (code "204") (name "PWM_2B") (class "Default")
      (node (ref "H2") (pin "15") (pinfunction "PWMB_15") (pintype "bidirectional"))
      (node (ref "SIP") (pin "T10") (pinfunction "EHRPWM2B_T10_T10") (pintype "bidirectional"))
    )
    (net (code "205") (name "PWR_LED") (class "Default")
      (node (ref "ON") (pin "C") (pinfunction "C_C") (pintype "passive"))
      (node (ref "R24") (pin "1") (pinfunction "1_1") (pintype "passive"))
    )
    (net (code "206") (name "RESET") (class "Default")
      (node (ref "C33") (pin "1") (pinfunction "1_1") (pintype "passive"))
      (node (ref "R60") (pin "1") (pinfunction "1_1") (pintype "passive"))
      (node (ref "RST") (pin "2") (pinfunction "2_2") (pintype "passive"))
      (node (ref "SIP") (pin "A10") (pinfunction "WARMRSTN_A10") (pintype "bidirectional"))
      (node (ref "U6") (pin "4") (pinfunction "Y_4") (pintype "output"))
    )
    (net (code "207") (name "SD_BOOT") (class "Default")
      (node (ref "R77") (pin "2") (pinfunction "2_2") (pintype "passive"))
      (node (ref "SD") (pin "2") (pinfunction "2_2") (pintype "passive"))
    )
    (net (code "208") (name "SERVO_EN") (class "Default")
      (node (ref "6VREG") (pin "8") (pinfunction "EN_8") (pintype "bidirectional"))
      (node (ref "R46") (pin "2") (pinfunction "2_2") (pintype "passive"))
      (node (ref "SIP") (pin "U3") (pinfunction "LCD_DATA10_U3_U3") (pintype "bidirectional"))
    )
    (net (code "209") (name "SPI1_MISO") (class "Default")
      (node (ref "S1.1") (pin "4") (pinfunction "4_4") (pintype "bidirectional"))
      (node (ref "S1.2") (pin "4") (pinfunction "4_4") (pintype "bidirectional"))
      (node (ref "SIP") (pin "B13") (pinfunction "SPI1_D0_B13_B13") (pintype "bidirectional"))
    )
    (net (code "210") (name "SPI1_MOSI") (class "Default")
      (node (ref "S1.1") (pin "3") (pinfunction "3_3") (pintype "bidirectional"))
      (node (ref "S1.2") (pin "3") (pinfunction "3_3") (pintype "bidirectional"))
      (node (ref "SIP") (pin "D12") (pinfunction "SPI1_D1_D12_D12") (pintype "bidirectional"))
    )
    (net (code "211") (name "SPI1_SCK") (class "Default")
      (node (ref "S1.1") (pin "5") (pinfunction "5_5") (pintype "bidirectional"))
      (node (ref "S1.2") (pin "5") (pinfunction "5_5") (pintype "bidirectional"))
      (node (ref "SIP") (pin "A13") (pinfunction "SPI1_CLK_A13_A13") (pintype "bidirectional"))
    )
    (net (code "212") (name "SPI1_SS1") (class "Default")
      (node (ref "S1.1") (pin "6") (pinfunction "6_6") (pintype "bidirectional"))
      (node (ref "SIP") (pin "H18") (pinfunction "H18_H18") (pintype "bidirectional"))
    )
    (net (code "213") (name "SPI1_SS2") (class "Default")
      (node (ref "S1.2") (pin "6") (pinfunction "6_6") (pintype "bidirectional"))
      (node (ref "SIP") (pin "C18") (pinfunction "GPIO0_7_C18_C18") (pintype "bidirectional"))
    )
    (net (code "214") (name "SVO1") (class "Default")
      (node (ref "R36") (pin "1") (pinfunction "1_1") (pintype "passive"))
      (node (ref "R50") (pin "1") (pinfunction "1_1") (pintype "passive"))
      (node (ref "SIP") (pin "U5") (pinfunction "LCD_VSYNC_U5_U5") (pintype "bidirectional"))
    )
    (net (code "215") (name "SVO2") (class "Default")
      (node (ref "R37") (pin "1") (pinfunction "1_1") (pintype "passive"))
      (node (ref "R51") (pin "1") (pinfunction "1_1") (pintype "passive"))
      (node (ref "SIP") (pin "V5") (pinfunction "LCD_PCLK_V5_V5") (pintype "bidirectional"))
    )
    (net (code "216") (name "SVO3") (class "Default")
      (node (ref "R38") (pin "1") (pinfunction "1_1") (pintype "passive"))
      (node (ref "R52") (pin "1") (pinfunction "1_1") (pintype "passive"))
      (node (ref "SIP") (pin "R5") (pinfunction "LCD_HSYNC_R5_R5") (pintype "bidirectional"))
    )
    (net (code "217") (name "SVO4") (class "Default")
      (node (ref "R39") (pin "1") (pinfunction "1_1") (pintype "passive"))
      (node (ref "R53") (pin "1") (pinfunction "1_1") (pintype "passive"))
      (node (ref "SIP") (pin "R6") (pinfunction "LCD_DE_R6_R6") (pintype "bidirectional"))
    )
    (net (code "218") (name "SVO5") (class "Default")
      (node (ref "R125") (pin "2") (pinfunction "2_2") (pintype "passive"))
      (node (ref "R40") (pin "1") (pinfunction "1_1") (pintype "passive"))
      (node (ref "SIP") (pin "T3") (pinfunction "LCD_DATA6_T3_T3") (pintype "bidirectional"))
    )
    (net (code "219") (name "SVO6") (class "Default")
      (node (ref "R127") (pin "2") (pinfunction "2_2") (pintype "passive"))
      (node (ref "R41") (pin "1") (pinfunction "1_1") (pintype "passive"))
      (node (ref "SIP") (pin "T4") (pinfunction "LCD_DATA7_T4_T4") (pintype "bidirectional"))
    )
    (net (code "220") (name "SVO7") (class "Default")
      (node (ref "R120") (pin "1") (pinfunction "1_1") (pintype "passive"))
      (node (ref "R42") (pin "1") (pinfunction "1_1") (pintype "passive"))
      (node (ref "SIP") (pin "T1") (pinfunction "LCD_DATA4_T1_T1") (pintype "bidirectional"))
    )
    (net (code "221") (name "SVO8") (class "Default")
      (node (ref "R122") (pin "1") (pinfunction "1_1") (pintype "passive"))
      (node (ref "R43") (pin "1") (pinfunction "1_1") (pintype "passive"))
      (node (ref "SIP") (pin "T2") (pinfunction "LCD_DATA5_T2_T2") (pintype "bidirectional"))
    )
    (net (code "222") (name "SYS_5V") (class "Default")
      (node (ref "C62") (pin "1") (pinfunction "1_1") (pintype "passive"))
      (node (ref "R121") (pin "2") (pinfunction "2_2") (pintype "passive"))
      (node (ref "SIP") (pin "W4") (pinfunction "VOUT_SYS_5V_0_W4") (pintype "power_in"))
      (node (ref "SIP") (pin "Y4") (pinfunction "VOUT_SYS_5V_1_Y4") (pintype "power_in"))
      (node (ref "TP1") (pin "TP") (pinfunction "TP_TP") (pintype "input"))
      (node (ref "U1") (pin "3") (pinfunction "VCC_3") (pintype "power_in"))
      (node (ref "U8") (pin "3") (pinfunction "IN2_3") (pintype "input"))
    )
    (net (code "223") (name "UART0_RX") (class "Default")
      (node (ref "SIP") (pin "E15") (pinfunction "UART0_RXD_E15_E15") (pintype "bidirectional"))
      (node (ref "UT0") (pin "3") (pinfunction "3_3") (pintype "bidirectional"))
    )
    (net (code "224") (name "UART0_TX") (class "Default")
      (node (ref "SIP") (pin "E16") (pinfunction "UART0_TXD_E16_E16") (pintype "bidirectional"))
      (node (ref "UT0") (pin "4") (pinfunction "4_4") (pintype "bidirectional"))
    )
    (net (code "225") (name "UART1_RX") (class "Default")
      (node (ref "SIP") (pin "D16") (pinfunction "UART1_RXD_D16_D16") (pintype "bidirectional"))
      (node (ref "UT1") (pin "3") (pinfunction "3_3") (pintype "bidirectional"))
    )
    (net (code "226") (name "UART1_TX") (class "Default")
      (node (ref "SIP") (pin "D15") (pinfunction "UART1_TXD_D15_D15") (pintype "bidirectional"))
      (node (ref "UT1") (pin "4") (pinfunction "4_4") (pintype "bidirectional"))
    )
    (net (code "227") (name "UART2_RX") (class "Default")
      (node (ref "GPS") (pin "3") (pinfunction "3_3") (pintype "bidirectional"))
      (node (ref "SIP") (pin "A17") (pinfunction "UART2_RXD_A17_A17") (pintype "bidirectional"))
    )
    (net (code "228") (name "UART2_TX") (class "Default")
      (node (ref "GPS") (pin "4") (pinfunction "4_4") (pintype "bidirectional"))
      (node (ref "SIP") (pin "B17") (pinfunction "UART2_TXD_B17_B17") (pintype "bidirectional"))
    )
    (net (code "229") (name "UART3_CTSN") (class "Default")
      (node (ref "R89") (pin "1") (pinfunction "1_1") (pintype "passive"))
      (node (ref "SIP") (pin "M17") (pinfunction "M17_M17") (pintype "bidirectional"))
      (node (ref "U10") (pin "12") (pinfunction "B8_12") (pintype "bidirectional"))
    )
    (net (code "230") (name "UART3_RTSN") (class "Default")
      (node (ref "R108") (pin "1") (pinfunction "1_1") (pintype "passive"))
      (node (ref "SIP") (pin "M18") (pinfunction "M18_M18") (pintype "bidirectional"))
      (node (ref "U10") (pin "13") (pinfunction "B7_13") (pintype "bidirectional"))
    )
    (net (code "231") (name "UART3_RX") (class "Default")
      (node (ref "SIP") (pin "L17") (pinfunction "L17_L17") (pintype "bidirectional"))
      (node (ref "U10") (pin "14") (pinfunction "B6_14") (pintype "bidirectional"))
    )
    (net (code "232") (name "UART3_TX") (class "Default")
      (node (ref "SIP") (pin "L16") (pinfunction "L16_L16") (pintype "bidirectional"))
      (node (ref "U10") (pin "15") (pinfunction "B5_15") (pintype "bidirectional"))
    )
    (net (code "233") (name "UART4_RX") (class "Default")
      (node (ref "DSM2") (pin "P$3") (pinfunction "3_P$3") (pintype "bidirectional"))
      (node (ref "SIP") (pin "T17") (pinfunction "UART4_RXD_T17_T17") (pintype "bidirectional"))
    )
    (net (code "234") (name "UART5_RX") (class "Default")
      (node (ref "R131") (pin "2") (pinfunction "2_2") (pintype "passive"))
      (node (ref "SIP") (pin "U2") (pinfunction "LCD_DATA9_U2_U2") (pintype "bidirectional"))
      (node (ref "UT5") (pin "3") (pinfunction "3_3") (pintype "bidirectional"))
    )
    (net (code "235") (name "UART5_TX") (class "Default")
      (node (ref "R129") (pin "2") (pinfunction "2_2") (pintype "passive"))
      (node (ref "SIP") (pin "U1") (pinfunction "LCD_DATA8_U1_U1") (pintype "bidirectional"))
      (node (ref "UT5") (pin "4") (pinfunction "4_4") (pintype "bidirectional"))
    )
    (net (code "236") (name "USB0_D_N") (class "Default")
      (node (ref "SIP") (pin "N18") (pinfunction "USB0_DM_N18") (pintype "bidirectional"))
      (node (ref "U3") (pin "2") (pinfunction "D-_2") (pintype "bidirectional"))
      (node (ref "X4") (pin "D-") (pinfunction "D-_D-") (pintype "input"))
    )
    (net (code "237") (name "USB0_D_P") (class "Default")
      (node (ref "SIP") (pin "N17") (pinfunction "USB0_DP_N17") (pintype "bidirectional"))
      (node (ref "U3") (pin "1") (pinfunction "D+_1") (pintype "bidirectional"))
      (node (ref "X4") (pin "D+") (pinfunction "D+_D+") (pintype "input"))
    )
    (net (code "238") (name "USB0_ID") (class "Default")
      (node (ref "SIP") (pin "P16") (pinfunction "USB0_ID_P16") (pintype "bidirectional"))
      (node (ref "U3") (pin "3") (pinfunction "ID_3") (pintype "bidirectional"))
      (node (ref "X4") (pin "ID") (pinfunction "ID_ID") (pintype "input"))
    )
    (net (code "239") (name "USB0_VBUS") (class "Default")
      (node (ref "C54") (pin "1") (pinfunction "1_1") (pintype "passive"))
      (node (ref "R112") (pin "2") (pinfunction "2_2") (pintype "passive"))
      (node (ref "R149") (pin "2") (pinfunction "2_2") (pintype "passive"))
      (node (ref "U3") (pin "6") (pinfunction "VBUS_6") (pintype "bidirectional"))
      (node (ref "X4") (pin "VBUS") (pinfunction "VBUS_VBUS") (pintype "input"))
    )
    (net (code "240") (name "USB1_D_N") (class "Default")
      (node (ref "SIP") (pin "R18") (pinfunction "USB1_DM_R18") (pintype "bidirectional"))
      (node (ref "U4") (pin "2") (pinfunction "D-_2") (pintype "bidirectional"))
      (node (ref "X3") (pin "2") (pinfunction "D-_2") (pintype "bidirectional"))
    )
    (net (code "241") (name "USB1_D_P") (class "Default")
      (node (ref "SIP") (pin "R17") (pinfunction "USB1_DP_R17") (pintype "bidirectional"))
      (node (ref "U4") (pin "1") (pinfunction "D+_1") (pintype "bidirectional"))
      (node (ref "X3") (pin "3") (pinfunction "D+_3") (pintype "bidirectional"))
    )
    (net (code "242") (name "USB1_VBUS") (class "Default")
      (node (ref "C45") (pin "1") (pinfunction "1_1") (pintype "passive"))
      (node (ref "C46") (pin "1") (pinfunction "1_1") (pintype "passive"))
      (node (ref "C55") (pin "1") (pinfunction "1_1") (pintype "passive"))
      (node (ref "C61") (pin "2") (pinfunction "2_2") (pintype "passive"))
      (node (ref "L5") (pin "1") (pinfunction "1_1") (pintype "passive"))
      (node (ref "R119") (pin "1") (pinfunction "1_1") (pintype "passive"))
      (node (ref "R121") (pin "1") (pinfunction "1_1") (pintype "passive"))
      (node (ref "R156") (pin "2") (pinfunction "2_2") (pintype "passive"))
      (node (ref "U4") (pin "6") (pinfunction "VBUS_6") (pintype "bidirectional"))
      (node (ref "U8") (pin "4") (pinfunction "OUT_4") (pintype "output"))
    )
    (net (code "243") (name "USB_DC") (class "Default")
      (node (ref "R112") (pin "1") (pinfunction "1_1") (pintype "passive"))
      (node (ref "SIP") (pin "Y8") (pinfunction "VIN_USB_0_Y8") (pintype "power_in"))
      (node (ref "SIP") (pin "Y9") (pinfunction "VIN_USB_1_Y9") (pintype "power_in"))
    )
    (net (code "244") (name "USR_LED0") (class "Default")
      (node (ref "0") (pin "A") (pinfunction "A_A") (pintype "passive"))
      (node (ref "SIP") (pin "V15") (pinfunction "USR0_V15_V15") (pintype "bidirectional"))
    )
    (net (code "245") (name "USR_LED1") (class "Default")
      (node (ref "1") (pin "A") (pinfunction "A_A") (pintype "passive"))
      (node (ref "SIP") (pin "U15") (pinfunction "USR1_U15_U15") (pintype "bidirectional"))
    )
    (net (code "246") (name "USR_LED2") (class "Default")
      (node (ref "2") (pin "A") (pinfunction "A_A") (pintype "passive"))
      (node (ref "SIP") (pin "T15") (pinfunction "USR2_T15_T15") (pintype "bidirectional"))
    )
    (net (code "247") (name "USR_LED3") (class "Default")
      (node (ref "3") (pin "A") (pinfunction "A_A") (pintype "passive"))
      (node (ref "SIP") (pin "V16") (pinfunction "USR3_V16_V16") (pintype "bidirectional"))
    )
    (net (code "248") (name "VCC") (class "Default")
      (node (ref "12V") (pin "IN") (pinfunction "IN_IN") (pintype "bidirectional"))
      (node (ref "C12") (pin "1") (pinfunction "1_1") (pintype "passive"))
      (node (ref "C7") (pin "1") (pinfunction "1_1") (pintype "passive"))
      (node (ref "CHG") (pin "A") (pinfunction "A_A") (pintype "passive"))
      (node (ref "CHGIC") (pin "2") (pinfunction "VIN_2") (pintype "bidirectional"))
      (node (ref "D3") (pin "A") (pinfunction "A_A") (pintype "passive"))
      (node (ref "R1") (pin "1") (pinfunction "1_1") (pintype "passive"))
    )
    (net (code "249") (name "VCC_CHG") (class "Default")
      (node (ref "C4") (pin "2") (pinfunction "2_2") (pintype "passive"))
      (node (ref "CHGIC") (pin "3") (pinfunction "VCC_3") (pintype "bidirectional"))
      (node (ref "R5") (pin "2") (pinfunction "2_2") (pintype "passive"))
    )
    (net (code "250") (name "VDD_1V8") (class "Default")
      (node (ref "C47") (pin "1") (pinfunction "1_1") (pintype "passive"))
      (node (ref "C50") (pin "1") (pinfunction "1_1") (pintype "passive"))
      (node (ref "C52") (pin "1") (pinfunction "1_1") (pintype "passive"))
      (node (ref "C57") (pin "2") (pinfunction "2_2") (pintype "passive"))
      (node (ref "C60") (pin "2") (pinfunction "2_2") (pintype "passive"))
      (node (ref "OSC1") (pin "4") (pinfunction "VCC_4") (pintype "bidirectional"))
      (node (ref "R101") (pin "1") (pinfunction "1_1") (pintype "passive"))
      (node (ref "R102") (pin "1") (pinfunction "1_1") (pintype "passive"))
      (node (ref "R103") (pin "1") (pinfunction "1_1") (pintype "passive"))
      (node (ref "R105") (pin "1") (pinfunction "1_1") (pintype "passive"))
      (node (ref "R9") (pin "1") (pinfunction "1_1") (pintype "passive"))
      (node (ref "R90") (pin "2") (pinfunction "2_2") (pintype "passive"))
      (node (ref "R98") (pin "1") (pinfunction "1_1") (pintype "passive"))
      (node (ref "R99") (pin "1") (pinfunction "1_1") (pintype "passive"))
      (node (ref "SIP") (pin "D10") (pinfunction "VDD_1V84_D10") (pintype "bidirectional"))
      (node (ref "SIP") (pin "E9") (pinfunction "VDD_1V83_E9") (pintype "bidirectional"))
      (node (ref "SIP") (pin "N16") (pinfunction "VOUT_LDO3_1P8V_0_N16") (pintype "power_in"))
      (node (ref "SIP") (pin "R16") (pinfunction "VOUT_LDO3_1P8V_1_R16") (pintype "power_in"))
      (node (ref "U10") (pin "2") (pinfunction "VCCA_2") (pintype "bidirectional"))
      (node (ref "U2") (pin "5") (pinfunction "VCC_5") (pintype "power_in"))
      (node (ref "U7") (pin "38") (pinfunction "VIO_38") (pintype "bidirectional"))
      (node (ref "U9") (pin "2") (pinfunction "VCCA_2") (pintype "bidirectional"))
    )
    (net (code "251") (name "VDD_3V3AUX") (class "Default")
      (node (ref "ON") (pin "A") (pinfunction "A_A") (pintype "passive"))
      (node (ref "SIP") (pin "Y11") (pinfunction "VOUT_LDO2_3P3V_Y11") (pintype "power_in"))
    )
    (net (code "252") (name "VDD_ADC") (class "Default")
      (node (ref "ADC") (pin "2") (pinfunction "2_2") (pintype "bidirectional"))
      (node (ref "C44") (pin "1") (pinfunction "1_1") (pintype "passive"))
      (node (ref "R111") (pin "1") (pinfunction "1_1") (pintype "passive"))
      (node (ref "SIP") (pin "A4") (pinfunction "VOUT_ADC_1P8V_0_A4") (pintype "bidirectional"))
      (node (ref "SIP") (pin "A5") (pinfunction "VOUT_ADC_1P8V_1_A5") (pintype "bidirectional"))
      (node (ref "SIP") (pin "D8") (pinfunction "VDDA_ADC_D8") (pintype "bidirectional"))
    )
    (net (code "253") (name "VDD_RTC") (class "Default")
      (node (ref "SIP") (pin "E14") (pinfunction "VDD_RTC3_E14") (pintype "bidirectional"))
      (node (ref "U6") (pin "5") (pinfunction "VCC_5") (pintype "power_in"))
    )
    (net (code "254") (name "VIN_BAT_0") (class "Default")
      (node (ref "SIP") (pin "Y2") (pinfunction "VIN_BAT_0_Y2") (pintype "power_in"))
    )
    (net (code "255") (name "VIN_BAT_1") (class "Default")
      (node (ref "SIP") (pin "Y3") (pinfunction "VIN_BAT_1_Y3") (pintype "power_in"))
    )
    (net (code "256") (name "V_BATT") (class "Default")
      (node (ref "6VREG") (pin "9") (pinfunction "VIN_9") (pintype "bidirectional"))
      (node (ref "C11") (pin "+") (pinfunction "+_+") (pintype "passive"))
      (node (ref "C20") (pin "2") (pinfunction "2_2") (pintype "passive"))
      (node (ref "C25") (pin "1") (pinfunction "1_1") (pintype "passive"))
      (node (ref "C26") (pin "1") (pinfunction "1_1") (pintype "passive"))
      (node (ref "CHGIC") (pin "9") (pinfunction "BATT_9") (pintype "bidirectional"))
      (node (ref "D2") (pin "A") (pinfunction "A_A") (pintype "passive"))
      (node (ref "H1") (pin "13") (pinfunction "VM2_13") (pintype "bidirectional"))
      (node (ref "H1") (pin "14") (pinfunction "VM3_14") (pintype "bidirectional"))
      (node (ref "H1") (pin "24") (pinfunction "VM1_24") (pintype "bidirectional"))
      (node (ref "H2") (pin "13") (pinfunction "VM2_13") (pintype "bidirectional"))
      (node (ref "H2") (pin "14") (pinfunction "VM3_14") (pintype "bidirectional"))
      (node (ref "H2") (pin "24") (pinfunction "VM1_24") (pintype "bidirectional"))
      (node (ref "LIPO") (pin "P$1") (pinfunction "1_P$1") (pintype "passive"))
      (node (ref "R19") (pin "1") (pinfunction "1_1") (pintype "passive"))
      (node (ref "R28") (pin "1") (pinfunction "1_1") (pintype "passive"))
      (node (ref "R34") (pin "1") (pinfunction "1_1") (pintype "passive"))
      (node (ref "R4") (pin "1") (pinfunction "1_1") (pintype "passive"))
    )
    (net (code "257") (name "V_DIV_BAT") (class "Default")
      (node (ref "R19") (pin "2") (pinfunction "2_2") (pintype "passive"))
      (node (ref "R25") (pin "1") (pinfunction "1_1") (pintype "passive"))
      (node (ref "SIP") (pin "A8") (pinfunction "AIN6_A8") (pintype "bidirectional"))
    )
    (net (code "258") (name "V_DIV_DC") (class "Default")
      (node (ref "R1") (pin "2") (pinfunction "2_2") (pintype "passive"))
      (node (ref "R14") (pin "1") (pinfunction "1_1") (pintype "passive"))
      (node (ref "SIP") (pin "B8") (pinfunction "AIN5_B8") (pintype "bidirectional"))
    )
    (net (code "259") (name "WIFI_LED") (class "Default")
      (node (ref "SIP") (pin "A15") (pinfunction "GPIO0_19_A15_A15") (pintype "bidirectional"))
      (node (ref "WIFI") (pin "A") (pinfunction "A_A") (pintype "passive"))
    )
    (net (code "260") (name "WLAN_IRQ") (class "Default")
      (node (ref "SIP") (pin "K16") (pinfunction "K16_K16") (pintype "bidirectional"))
      (node (ref "U2") (pin "4") (pinfunction "Y_4") (pintype "output"))
    )
    (net (code "261") (name "WL_BT_OE") (class "Default")
      (node (ref "R93") (pin "1") (pinfunction "1_1") (pintype "passive"))
      (node (ref "SIP") (pin "L18") (pinfunction "L18_L18") (pintype "bidirectional"))
    )
    (net (code "262") (name "WL_EN") (class "Default")
      (node (ref "SIP") (pin "K18") (pinfunction "K18_K18") (pintype "bidirectional"))
      (node (ref "U9") (pin "20") (pinfunction "B1_20") (pintype "bidirectional"))
    )
    (net (code "263") (name "WL_EN_1V8") (class "Default")
      (node (ref "R87") (pin "1") (pinfunction "1_1") (pintype "passive"))
      (node (ref "U7") (pin "40") (pinfunction "WLAN_EN_40") (pintype "bidirectional"))
      (node (ref "U9") (pin "1") (pinfunction "A1_1") (pintype "bidirectional"))
    )
    (net (code "264") (name "WL_IRQ") (class "Default")
      (node (ref "R84") (pin "1") (pinfunction "1_1") (pintype "passive"))
      (node (ref "U2") (pin "2") (pinfunction "A_2") (pintype "input"))
    )
    (net (code "265") (name "WL_SDIO_CLK") (class "Default")
      (node (ref "R103") (pin "2") (pinfunction "2_2") (pintype "passive"))
      (node (ref "R78") (pin "1") (pinfunction "1_1") (pintype "passive"))
      (node (ref "U9") (pin "8") (pinfunction "A7_8") (pintype "bidirectional"))
    )
    (net (code "266") (name "WL_SDIO_CMD") (class "Default")
      (node (ref "R105") (pin "2") (pinfunction "2_2") (pintype "passive"))
      (node (ref "R79") (pin "1") (pinfunction "1_1") (pintype "passive"))
      (node (ref "U9") (pin "9") (pinfunction "A8_9") (pintype "bidirectional"))
    )
    (net (code "267") (name "WL_SDIO_D0") (class "Default")
      (node (ref "R80") (pin "1") (pinfunction "1_1") (pintype "passive"))
      (node (ref "R98") (pin "2") (pinfunction "2_2") (pintype "passive"))
      (node (ref "U9") (pin "7") (pinfunction "A6_7") (pintype "bidirectional"))
    )
    (net (code "268") (name "WL_SDIO_D1") (class "Default")
      (node (ref "R81") (pin "1") (pinfunction "1_1") (pintype "passive"))
      (node (ref "R99") (pin "2") (pinfunction "2_2") (pintype "passive"))
      (node (ref "U9") (pin "6") (pinfunction "A5_6") (pintype "bidirectional"))
    )
    (net (code "269") (name "WL_SDIO_D2") (class "Default")
      (node (ref "R101") (pin "2") (pinfunction "2_2") (pintype "passive"))
      (node (ref "R82") (pin "1") (pinfunction "1_1") (pintype "passive"))
      (node (ref "U9") (pin "5") (pinfunction "A4_5") (pintype "bidirectional"))
    )
    (net (code "270") (name "WL_SDIO_D3") (class "Default")
      (node (ref "R102") (pin "2") (pinfunction "2_2") (pintype "passive"))
      (node (ref "R83") (pin "1") (pinfunction "1_1") (pintype "passive"))
      (node (ref "U9") (pin "4") (pinfunction "A3_4") (pintype "bidirectional"))
    )
    (net (code "271") (name "unconnected-(12V-PadOUT_CON)") (class "Default")
      (node (ref "12V") (pin "OUT_CON") (pinfunction "OUT_CON_OUT_CON") (pintype "bidirectional"))
    )
    (net (code "272") (name "unconnected-(CHGIC-ACOK-Pad12)") (class "Default")
      (node (ref "CHGIC") (pin "12") (pinfunction "ACOK_12") (pintype "bidirectional"))
    )
    (net (code "273") (name "unconnected-(CHGIC-CELL-Pad4)") (class "Default")
      (node (ref "CHGIC") (pin "4") (pinfunction "CELL_4") (pintype "bidirectional"))
    )
    (net (code "274") (name "unconnected-(CHGIC-SEL-Pad5)") (class "Default")
      (node (ref "CHGIC") (pin "5") (pinfunction "SEL_5") (pintype "bidirectional"))
    )
    (net (code "275") (name "unconnected-(FUD1-PadP$1)") (class "Default")
      (node (ref "FUD1") (pin "P$1") (pinfunction "P$1_P$1") (pintype "no_connect"))
    )
    (net (code "276") (name "unconnected-(FUD2-PadP$1)") (class "Default")
      (node (ref "FUD2") (pin "P$1") (pinfunction "P$1_P$1") (pintype "no_connect"))
    )
    (net (code "277") (name "unconnected-(FUD3-PadP$1)") (class "Default")
      (node (ref "FUD3") (pin "P$1") (pinfunction "P$1_P$1") (pintype "no_connect"))
    )
    (net (code "278") (name "unconnected-(FUD4-PadP$1)") (class "Default")
      (node (ref "FUD4") (pin "P$1") (pinfunction "P$1_P$1") (pintype "no_connect"))
    )
    (net (code "279") (name "unconnected-(FUD5-PadP$1)") (class "Default")
      (node (ref "FUD5") (pin "P$1") (pinfunction "P$1_P$1") (pintype "no_connect"))
    )
    (net (code "280") (name "unconnected-(FUD6-PadP$1)") (class "Default")
      (node (ref "FUD6") (pin "P$1") (pinfunction "P$1_P$1") (pintype "no_connect"))
    )
    (net (code "281") (name "unconnected-(GPS-Pad1)") (class "Default")
      (node (ref "GPS") (pin "1") (pinfunction "1_1") (pintype "bidirectional"))
    )
    (net (code "282") (name "unconnected-(IMU-AUX_CL-Pad7)") (class "Default")
      (node (ref "IMU") (pin "7") (pinfunction "AUX_CL_7") (pintype "bidirectional"))
    )
    (net (code "283") (name "unconnected-(IMU-AUX_DA-Pad21)") (class "Default")
      (node (ref "IMU") (pin "21") (pinfunction "AUX_DA_21") (pintype "bidirectional"))
    )
    (net (code "284") (name "unconnected-(IMU-FSYNC-Pad11)") (class "Default")
      (node (ref "IMU") (pin "11") (pinfunction "FSYNC_11") (pintype "bidirectional"))
    )
    (net (code "285") (name "unconnected-(IMU-NC-Pad2)") (class "Default")
      (node (ref "IMU") (pin "2") (pinfunction "NC_2") (pintype "bidirectional"))
    )
    (net (code "286") (name "unconnected-(IMU-NC-Pad3)") (class "Default")
      (node (ref "IMU") (pin "3") (pinfunction "NC_3") (pintype "bidirectional"))
    )
    (net (code "287") (name "unconnected-(IMU-NC-Pad4)") (class "Default")
      (node (ref "IMU") (pin "4") (pinfunction "NC_4") (pintype "bidirectional"))
    )
    (net (code "288") (name "unconnected-(IMU-NC-Pad5)") (class "Default")
      (node (ref "IMU") (pin "5") (pinfunction "NC_5") (pintype "bidirectional"))
    )
    (net (code "289") (name "unconnected-(IMU-NC-Pad6)") (class "Default")
      (node (ref "IMU") (pin "6") (pinfunction "NC_6") (pintype "bidirectional"))
    )
    (net (code "290") (name "unconnected-(IMU-NC-Pad14)") (class "Default")
      (node (ref "IMU") (pin "14") (pinfunction "NC_14") (pintype "bidirectional"))
    )
    (net (code "291") (name "unconnected-(IMU-NC-Pad15)") (class "Default")
      (node (ref "IMU") (pin "15") (pinfunction "NC_15") (pintype "bidirectional"))
    )
    (net (code "292") (name "unconnected-(IMU-NC-Pad16)") (class "Default")
      (node (ref "IMU") (pin "16") (pinfunction "NC_16") (pintype "bidirectional"))
    )
    (net (code "293") (name "unconnected-(IMU-NC-Pad17)") (class "Default")
      (node (ref "IMU") (pin "17") (pinfunction "NC_17") (pintype "bidirectional"))
    )
    (net (code "294") (name "unconnected-(IMU-RESV-Pad19)") (class "Default")
      (node (ref "IMU") (pin "19") (pinfunction "RESV_19") (pintype "bidirectional"))
    )
    (net (code "295") (name "unconnected-(PROT-CO-Pad3)") (class "Default")
      (node (ref "PROT") (pin "3") (pinfunction "CO_3") (pintype "bidirectional"))
    )
    (net (code "296") (name "unconnected-(PROT-DP-Pad4)") (class "Default")
      (node (ref "PROT") (pin "4") (pinfunction "DP_4") (pintype "bidirectional"))
    )
    (net (code "297") (name "unconnected-(SIPA-BAT_TEMP-PadW1)") (class "Default")
      (node (ref "SIP") (pin "W1") (pinfunction "BAT_TEMP_W1") (pintype "bidirectional"))
    )
    (net (code "298") (name "unconnected-(SIPA-BAT_VOLT-PadY1)") (class "Default")
      (node (ref "SIP") (pin "Y1") (pinfunction "BAT_VOLT_Y1") (pintype "bidirectional"))
    )
    (net (code "299") (name "unconnected-(SIPA-L1_IN-PadY14)") (class "Default")
      (node (ref "SIP") (pin "Y14") (pinfunction "L1_IN_Y14") (pintype "bidirectional"))
    )
    (net (code "300") (name "unconnected-(SIPA-L1_OUT-PadY13)") (class "Default")
      (node (ref "SIP") (pin "Y13") (pinfunction "L1_OUT_Y13") (pintype "bidirectional"))
    )
    (net (code "301") (name "unconnected-(SIPA-L2_IN-PadY17)") (class "Default")
      (node (ref "SIP") (pin "Y17") (pinfunction "L2_IN_Y17") (pintype "bidirectional"))
    )
    (net (code "302") (name "unconnected-(SIPA-L2_OUT-PadY16)") (class "Default")
      (node (ref "SIP") (pin "Y16") (pinfunction "L2_OUT_Y16") (pintype "bidirectional"))
    )
    (net (code "303") (name "unconnected-(SIPA-L3_IN-PadY20)") (class "Default")
      (node (ref "SIP") (pin "Y20") (pinfunction "L3_IN_Y20") (pintype "bidirectional"))
    )
    (net (code "304") (name "unconnected-(SIPA-L3_OUT-PadY19)") (class "Default")
      (node (ref "SIP") (pin "Y19") (pinfunction "L3_OUT_Y19") (pintype "bidirectional"))
    )
    (net (code "305") (name "unconnected-(SIPC-AIN4-PadC8)") (class "Default")
      (node (ref "SIP") (pin "C8") (pinfunction "AIN4_C8") (pintype "bidirectional"))
    )
    (net (code "306") (name "unconnected-(SIPC-USB0_CE-PadM15)") (class "Default")
      (node (ref "SIP") (pin "M15") (pinfunction "USB0_CE_M15") (pintype "bidirectional"))
    )
    (net (code "307") (name "unconnected-(SIPC-USB0_DRVVBUS-PadF16)") (class "Default")
      (node (ref "SIP") (pin "F16") (pinfunction "USB0_DRVVBUS_F16") (pintype "bidirectional"))
    )
    (net (code "308") (name "unconnected-(SIPC-USB1_CE-PadP18)") (class "Default")
      (node (ref "SIP") (pin "P18") (pinfunction "USB1_CE_P18") (pintype "bidirectional"))
    )
    (net (code "309") (name "unconnected-(SIPC-USB1_DRVVBUS-PadF15)") (class "Default")
      (node (ref "SIP") (pin "F15") (pinfunction "USB1_DRVVBUS_F15") (pintype "bidirectional"))
    )
    (net (code "310") (name "unconnected-(SIPD-NC1-PadV11)") (class "Default")
      (node (ref "SIP") (pin "V11") (pinfunction "NC1_V11") (pintype "bidirectional"))
    )
    (net (code "311") (name "unconnected-(SIPD-NC2-PadU11)") (class "Default")
      (node (ref "SIP") (pin "U11") (pinfunction "NC2_U11") (pintype "bidirectional"))
    )
    (net (code "312") (name "unconnected-(SIPD-NC3-PadV10)") (class "Default")
      (node (ref "SIP") (pin "V10") (pinfunction "NC3_V10") (pintype "bidirectional"))
    )
    (net (code "313") (name "unconnected-(SIPD-NC4-PadB1)") (class "Default")
      (node (ref "SIP") (pin "B1") (pinfunction "NC4_B1") (pintype "bidirectional"))
    )
    (net (code "314") (name "unconnected-(SIPD-NC5-PadB2)") (class "Default")
      (node (ref "SIP") (pin "B2") (pinfunction "NC5_B2") (pintype "bidirectional"))
    )
    (net (code "315") (name "unconnected-(SIPD-NC6-PadB3)") (class "Default")
      (node (ref "SIP") (pin "B3") (pinfunction "NC6_B3") (pintype "bidirectional"))
    )
    (net (code "316") (name "unconnected-(SIPD-NC12-PadC1)") (class "Default")
      (node (ref "SIP") (pin "C1") (pinfunction "NC12_C1") (pintype "bidirectional"))
    )
    (net (code "317") (name "unconnected-(SIPD-NC20-PadC2)") (class "Default")
      (node (ref "SIP") (pin "C2") (pinfunction "NC20_C2") (pintype "bidirectional"))
    )
    (net (code "318") (name "unconnected-(SIPD-NC21-PadC3)") (class "Default")
      (node (ref "SIP") (pin "C3") (pinfunction "NC21_C3") (pintype "bidirectional"))
    )
    (net (code "319") (name "unconnected-(SIPD-NC22-PadC4)") (class "Default")
      (node (ref "SIP") (pin "C4") (pinfunction "NC22_C4") (pintype "bidirectional"))
    )
    (net (code "320") (name "unconnected-(SIPD-NC23-PadP2)") (class "Default")
      (node (ref "SIP") (pin "P2") (pinfunction "NC23_P2") (pintype "bidirectional"))
    )
    (net (code "321") (name "unconnected-(SIPD-NC24-PadD1)") (class "Default")
      (node (ref "SIP") (pin "D1") (pinfunction "NC24_D1") (pintype "bidirectional"))
    )
    (net (code "322") (name "unconnected-(SIPD-NC31-PadD2)") (class "Default")
      (node (ref "SIP") (pin "D2") (pinfunction "NC31_D2") (pintype "bidirectional"))
    )
    (net (code "323") (name "unconnected-(SIPD-NC32-PadD3)") (class "Default")
      (node (ref "SIP") (pin "D3") (pinfunction "NC32_D3") (pintype "bidirectional"))
    )
    (net (code "324") (name "unconnected-(SIPD-NC33-PadD4)") (class "Default")
      (node (ref "SIP") (pin "D4") (pinfunction "NC33_D4") (pintype "bidirectional"))
    )
    (net (code "325") (name "unconnected-(SIPD-NC34-PadD5)") (class "Default")
      (node (ref "SIP") (pin "D5") (pinfunction "NC34_D5") (pintype "bidirectional"))
    )
    (net (code "326") (name "unconnected-(SIPD-NC45-PadP3)") (class "Default")
      (node (ref "SIP") (pin "P3") (pinfunction "NC45_P3") (pintype "bidirectional"))
    )
    (net (code "327") (name "unconnected-(SIPD-NC46-PadE1)") (class "Default")
      (node (ref "SIP") (pin "E1") (pinfunction "NC46_E1") (pintype "bidirectional"))
    )
    (net (code "328") (name "unconnected-(SIPD-NC47-PadE2)") (class "Default")
      (node (ref "SIP") (pin "E2") (pinfunction "NC47_E2") (pintype "bidirectional"))
    )
    (net (code "329") (name "unconnected-(SIPD-NC48-PadE3)") (class "Default")
      (node (ref "SIP") (pin "E3") (pinfunction "NC48_E3") (pintype "bidirectional"))
    )
    (net (code "330") (name "unconnected-(SIPD-NC58-PadE4)") (class "Default")
      (node (ref "SIP") (pin "E4") (pinfunction "NC58_E4") (pintype "bidirectional"))
    )
    (net (code "331") (name "unconnected-(SIPD-NC59-PadF1)") (class "Default")
      (node (ref "SIP") (pin "F1") (pinfunction "NC59_F1") (pintype "bidirectional"))
    )
    (net (code "332") (name "unconnected-(SIPD-NC60-PadF2)") (class "Default")
      (node (ref "SIP") (pin "F2") (pinfunction "NC60_F2") (pintype "bidirectional"))
    )
    (net (code "333") (name "unconnected-(SIPD-NC61-PadF3)") (class "Default")
      (node (ref "SIP") (pin "F3") (pinfunction "NC61_F3") (pintype "bidirectional"))
    )
    (net (code "334") (name "unconnected-(SIPD-NC68-PadF4)") (class "Default")
      (node (ref "SIP") (pin "F4") (pinfunction "NC68_F4") (pintype "bidirectional"))
    )
    (net (code "335") (name "unconnected-(SIPD-NC69-PadG1)") (class "Default")
      (node (ref "SIP") (pin "G1") (pinfunction "NC69_G1") (pintype "bidirectional"))
    )
    (net (code "336") (name "unconnected-(SIPD-NC70-PadG2)") (class "Default")
      (node (ref "SIP") (pin "G2") (pinfunction "NC70_G2") (pintype "bidirectional"))
    )
    (net (code "337") (name "unconnected-(SIPD-NC71-PadG3)") (class "Default")
      (node (ref "SIP") (pin "G3") (pinfunction "NC71_G3") (pintype "bidirectional"))
    )
    (net (code "338") (name "unconnected-(SIPD-NC76-PadG4)") (class "Default")
      (node (ref "SIP") (pin "G4") (pinfunction "NC76_G4") (pintype "bidirectional"))
    )
    (net (code "339") (name "unconnected-(SIPD-NC77-PadH1)") (class "Default")
      (node (ref "SIP") (pin "H1") (pinfunction "NC77_H1") (pintype "bidirectional"))
    )
    (net (code "340") (name "unconnected-(SIPD-NC78-PadH2)") (class "Default")
      (node (ref "SIP") (pin "H2") (pinfunction "NC78_H2") (pintype "bidirectional"))
    )
    (net (code "341") (name "unconnected-(SIPD-NC79-PadH3)") (class "Default")
      (node (ref "SIP") (pin "H3") (pinfunction "NC79_H3") (pintype "bidirectional"))
    )
    (net (code "342") (name "unconnected-(SIPD-NC84-PadH4)") (class "Default")
      (node (ref "SIP") (pin "H4") (pinfunction "NC84_H4") (pintype "bidirectional"))
    )
    (net (code "343") (name "unconnected-(SIPD-NC85-PadJ1)") (class "Default")
      (node (ref "SIP") (pin "J1") (pinfunction "NC85_J1") (pintype "bidirectional"))
    )
    (net (code "344") (name "unconnected-(SIPD-NC86-PadJ2)") (class "Default")
      (node (ref "SIP") (pin "J2") (pinfunction "NC86_J2") (pintype "bidirectional"))
    )
    (net (code "345") (name "unconnected-(SIPD-NC87-PadJ3)") (class "Default")
      (node (ref "SIP") (pin "J3") (pinfunction "NC87_J3") (pintype "bidirectional"))
    )
    (net (code "346") (name "unconnected-(SIPD-NC94-PadJ4)") (class "Default")
      (node (ref "SIP") (pin "J4") (pinfunction "NC94_J4") (pintype "bidirectional"))
    )
    (net (code "347") (name "unconnected-(SIPD-NC95-PadK1)") (class "Default")
      (node (ref "SIP") (pin "K1") (pinfunction "NC95_K1") (pintype "bidirectional"))
    )
    (net (code "348") (name "unconnected-(SIPD-NC96-PadK2)") (class "Default")
      (node (ref "SIP") (pin "K2") (pinfunction "NC96_K2") (pintype "bidirectional"))
    )
    (net (code "349") (name "unconnected-(SIPD-NC97-PadK3)") (class "Default")
      (node (ref "SIP") (pin "K3") (pinfunction "NC97_K3") (pintype "bidirectional"))
    )
    (net (code "350") (name "unconnected-(SIPD-NC104-PadK4)") (class "Default")
      (node (ref "SIP") (pin "K4") (pinfunction "NC104_K4") (pintype "bidirectional"))
    )
    (net (code "351") (name "unconnected-(SIPD-NC105-PadL1)") (class "Default")
      (node (ref "SIP") (pin "L1") (pinfunction "NC105_L1") (pintype "bidirectional"))
    )
    (net (code "352") (name "unconnected-(SIPD-NC106-PadL2)") (class "Default")
      (node (ref "SIP") (pin "L2") (pinfunction "NC106_L2") (pintype "bidirectional"))
    )
    (net (code "353") (name "unconnected-(SIPD-NC107-PadL3)") (class "Default")
      (node (ref "SIP") (pin "L3") (pinfunction "NC107_L3") (pintype "bidirectional"))
    )
    (net (code "354") (name "unconnected-(SIPD-NC111-PadL4)") (class "Default")
      (node (ref "SIP") (pin "L4") (pinfunction "NC111_L4") (pintype "bidirectional"))
    )
    (net (code "355") (name "unconnected-(SIPD-NC112-PadM1)") (class "Default")
      (node (ref "SIP") (pin "M1") (pinfunction "NC112_M1") (pintype "bidirectional"))
    )
    (net (code "356") (name "unconnected-(SIPD-NC113-PadM2)") (class "Default")
      (node (ref "SIP") (pin "M2") (pinfunction "NC113_M2") (pintype "bidirectional"))
    )
    (net (code "357") (name "unconnected-(SIPD-NC114-PadM3)") (class "Default")
      (node (ref "SIP") (pin "M3") (pinfunction "NC114_M3") (pintype "bidirectional"))
    )
    (net (code "358") (name "unconnected-(SIPD-NC121-PadM4)") (class "Default")
      (node (ref "SIP") (pin "M4") (pinfunction "NC121_M4") (pintype "bidirectional"))
    )
    (net (code "359") (name "unconnected-(SIPD-NC122-PadP4)") (class "Default")
      (node (ref "SIP") (pin "P4") (pinfunction "NC122_P4") (pintype "bidirectional"))
    )
    (net (code "360") (name "unconnected-(SIPD-NC123-PadN1)") (class "Default")
      (node (ref "SIP") (pin "N1") (pinfunction "NC123_N1") (pintype "bidirectional"))
    )
    (net (code "361") (name "unconnected-(SIPD-NC124-PadN2)") (class "Default")
      (node (ref "SIP") (pin "N2") (pinfunction "NC124_N2") (pintype "bidirectional"))
    )
    (net (code "362") (name "unconnected-(SIPD-NC136-PadN3)") (class "Default")
      (node (ref "SIP") (pin "N3") (pinfunction "NC136_N3") (pintype "bidirectional"))
    )
    (net (code "363") (name "unconnected-(SIPD-NC137-PadN4)") (class "Default")
      (node (ref "SIP") (pin "N4") (pinfunction "NC137_N4") (pintype "bidirectional"))
    )
    (net (code "364") (name "unconnected-(SIPD-NC138-PadP1)") (class "Default")
      (node (ref "SIP") (pin "P1") (pinfunction "NC138_P1") (pintype "bidirectional"))
    )
    (net (code "365") (name "unconnected-(SIPE-CAP_VBB_MPU-PadC10)") (class "Default")
      (node (ref "SIP") (pin "C10") (pinfunction "CAP_VBB_MPU_C10") (pintype "bidirectional"))
    )
    (net (code "366") (name "unconnected-(SIPE-CAP_VDD_RTC-PadD6)") (class "Default")
      (node (ref "SIP") (pin "D6") (pinfunction "CAP_VDD_RTC_D6") (pintype "bidirectional"))
    )
    (net (code "367") (name "unconnected-(SIPE-CAP_VDD_SRAM_COR-PadD9)") (class "Default")
      (node (ref "SIP") (pin "D9") (pinfunction "CAP_VDD_SRAM_COR_D9") (pintype "bidirectional"))
    )
    (net (code "368") (name "unconnected-(SIPE-CAP_VDD_SRAM_MPU-PadD11)") (class "Default")
      (node (ref "SIP") (pin "D11") (pinfunction "CAP_VDD_SRAM_MPU_D11") (pintype "bidirectional"))
    )
    (net (code "369") (name "unconnected-(SIPE-TESTOUT-PadA3)") (class "Default")
      (node (ref "SIP") (pin "A3") (pinfunction "TESTOUT_A3") (pintype "bidirectional"))
    )
    (net (code "370") (name "unconnected-(SIPE-VDDS_DDR1-PadE5)") (class "Default")
      (node (ref "SIP") (pin "E5") (pinfunction "VDDS_DDR1_E5") (pintype "bidirectional"))
    )
    (net (code "371") (name "unconnected-(SIPE-VDDS_DDR2-PadF5)") (class "Default")
      (node (ref "SIP") (pin "F5") (pinfunction "VDDS_DDR2_F5") (pintype "bidirectional"))
    )
    (net (code "372") (name "unconnected-(SIPE-VDDS_DDR3-PadG5)") (class "Default")
      (node (ref "SIP") (pin "G5") (pinfunction "VDDS_DDR3_G5") (pintype "bidirectional"))
    )
    (net (code "373") (name "unconnected-(SIPE-VDDS_DDR4-PadH5)") (class "Default")
      (node (ref "SIP") (pin "H5") (pinfunction "VDDS_DDR4_H5") (pintype "bidirectional"))
    )
    (net (code "374") (name "unconnected-(SIPE-VDDS_DDR5-PadJ5)") (class "Default")
      (node (ref "SIP") (pin "J5") (pinfunction "VDDS_DDR5_J5") (pintype "bidirectional"))
    )
    (net (code "375") (name "unconnected-(SIPE-VDDS_DDR6-PadK5)") (class "Default")
      (node (ref "SIP") (pin "K5") (pinfunction "VDDS_DDR6_K5") (pintype "bidirectional"))
    )
    (net (code "376") (name "unconnected-(SIPE-VDDS_DDR7-PadL5)") (class "Default")
      (node (ref "SIP") (pin "L5") (pinfunction "VDDS_DDR7_L5") (pintype "bidirectional"))
    )
    (net (code "377") (name "unconnected-(SIPE-VDD_3V3A1-PadE10)") (class "Default")
      (node (ref "SIP") (pin "E10") (pinfunction "VDD_3V3A1_E10") (pintype "bidirectional"))
    )
    (net (code "378") (name "unconnected-(SIPE-VDD_3V3A2-PadE11)") (class "Default")
      (node (ref "SIP") (pin "E11") (pinfunction "VDD_3V3A2_E11") (pintype "bidirectional"))
    )
    (net (code "379") (name "unconnected-(SIPE-VDD_3V3A3-PadE12)") (class "Default")
      (node (ref "SIP") (pin "E12") (pinfunction "VDD_3V3A3_E12") (pintype "bidirectional"))
    )
    (net (code "380") (name "unconnected-(SIPE-VDD_3V3A4-PadE13)") (class "Default")
      (node (ref "SIP") (pin "E13") (pinfunction "VDD_3V3A4_E13") (pintype "bidirectional"))
    )
    (net (code "381") (name "unconnected-(SIPE-VDD_3V3A5-PadF14)") (class "Default")
      (node (ref "SIP") (pin "F14") (pinfunction "VDD_3V3A5_F14") (pintype "bidirectional"))
    )
    (net (code "382") (name "unconnected-(SIPE-VDD_3V3A6-PadG14)") (class "Default")
      (node (ref "SIP") (pin "G14") (pinfunction "VDD_3V3A6_G14") (pintype "bidirectional"))
    )
    (net (code "383") (name "unconnected-(SIPE-VDD_3V3A7-PadH14)") (class "Default")
      (node (ref "SIP") (pin "H14") (pinfunction "VDD_3V3A7_H14") (pintype "bidirectional"))
    )
    (net (code "384") (name "unconnected-(SIPE-VDD_3V3A8-PadJ14)") (class "Default")
      (node (ref "SIP") (pin "J14") (pinfunction "VDD_3V3A8_J14") (pintype "bidirectional"))
    )
    (net (code "385") (name "unconnected-(SIPE-VDD_3V3A9-PadK14)") (class "Default")
      (node (ref "SIP") (pin "K14") (pinfunction "VDD_3V3A9_K14") (pintype "bidirectional"))
    )
    (net (code "386") (name "unconnected-(SIPE-VDD_3V3A10-PadL14)") (class "Default")
      (node (ref "SIP") (pin "L14") (pinfunction "VDD_3V3A10_L14") (pintype "bidirectional"))
    )
    (net (code "387") (name "unconnected-(SIPE-VDD_3V3A11-PadN5)") (class "Default")
      (node (ref "SIP") (pin "N5") (pinfunction "VDD_3V3A11_N5") (pintype "bidirectional"))
    )
    (net (code "388") (name "unconnected-(SIPE-VDD_3V3A12-PadN15)") (class "Default")
      (node (ref "SIP") (pin "N15") (pinfunction "VDD_3V3A12_N15") (pintype "bidirectional"))
    )
    (net (code "389") (name "unconnected-(SIPE-VDD_3V3A13-PadP5)") (class "Default")
      (node (ref "SIP") (pin "P5") (pinfunction "VDD_3V3A13_P5") (pintype "bidirectional"))
    )
    (net (code "390") (name "unconnected-(SIPE-VDD_3V3A14-PadP6)") (class "Default")
      (node (ref "SIP") (pin "P6") (pinfunction "VDD_3V3A14_P6") (pintype "bidirectional"))
    )
    (net (code "391") (name "unconnected-(SIPE-VDD_3V3A15-PadP7)") (class "Default")
      (node (ref "SIP") (pin "P7") (pinfunction "VDD_3V3A15_P7") (pintype "bidirectional"))
    )
    (net (code "392") (name "unconnected-(SIPE-VDD_3V3A16-PadP8)") (class "Default")
      (node (ref "SIP") (pin "P8") (pinfunction "VDD_3V3A16_P8") (pintype "bidirectional"))
    )
    (net (code "393") (name "unconnected-(SIPE-VDD_3V3A17-PadP10)") (class "Default")
      (node (ref "SIP") (pin "P10") (pinfunction "VDD_3V3A17_P10") (pintype "bidirectional"))
    )
    (net (code "394") (name "unconnected-(SIPE-VDD_3V3A18-PadP11)") (class "Default")
      (node (ref "SIP") (pin "P11") (pinfunction "VDD_3V3A18_P11") (pintype "bidirectional"))
    )
    (net (code "395") (name "unconnected-(SIPE-VDD_3V3A19-PadP12)") (class "Default")
      (node (ref "SIP") (pin "P12") (pinfunction "VDD_3V3A19_P12") (pintype "bidirectional"))
    )
    (net (code "396") (name "unconnected-(SIPE-VDD_3V3A20-PadP13)") (class "Default")
      (node (ref "SIP") (pin "P13") (pinfunction "VDD_3V3A20_P13") (pintype "bidirectional"))
    )
    (net (code "397") (name "unconnected-(SIPE-VDD_3V3A21-PadR15)") (class "Default")
      (node (ref "SIP") (pin "R15") (pinfunction "VDD_3V3A21_R15") (pintype "bidirectional"))
    )
    (net (code "398") (name "unconnected-(SIPE-VDD_CORE1-PadF6)") (class "Default")
      (node (ref "SIP") (pin "F6") (pinfunction "VDD_CORE1_F6") (pintype "bidirectional"))
    )
    (net (code "399") (name "unconnected-(SIPE-VDD_CORE2-PadF7)") (class "Default")
      (node (ref "SIP") (pin "F7") (pinfunction "VDD_CORE2_F7") (pintype "bidirectional"))
    )
    (net (code "400") (name "unconnected-(SIPE-VDD_CORE3-PadG6)") (class "Default")
      (node (ref "SIP") (pin "G6") (pinfunction "VDD_CORE3_G6") (pintype "bidirectional"))
    )
    (net (code "401") (name "unconnected-(SIPE-VDD_CORE4-PadG7)") (class "Default")
      (node (ref "SIP") (pin "G7") (pinfunction "VDD_CORE4_G7") (pintype "bidirectional"))
    )
    (net (code "402") (name "unconnected-(SIPE-VDD_CORE5-PadG10)") (class "Default")
      (node (ref "SIP") (pin "G10") (pinfunction "VDD_CORE5_G10") (pintype "bidirectional"))
    )
    (net (code "403") (name "unconnected-(SIPE-VDD_CORE6-PadH11)") (class "Default")
      (node (ref "SIP") (pin "H11") (pinfunction "VDD_CORE6_H11") (pintype "bidirectional"))
    )
    (net (code "404") (name "unconnected-(SIPE-VDD_CORE7-PadJ12)") (class "Default")
      (node (ref "SIP") (pin "J12") (pinfunction "VDD_CORE7_J12") (pintype "bidirectional"))
    )
    (net (code "405") (name "unconnected-(SIPE-VDD_CORE8-PadK6)") (class "Default")
      (node (ref "SIP") (pin "K6") (pinfunction "VDD_CORE8_K6") (pintype "bidirectional"))
    )
    (net (code "406") (name "unconnected-(SIPE-VDD_CORE9-PadK8)") (class "Default")
      (node (ref "SIP") (pin "K8") (pinfunction "VDD_CORE9_K8") (pintype "bidirectional"))
    )
    (net (code "407") (name "unconnected-(SIPE-VDD_CORE10-PadK12)") (class "Default")
      (node (ref "SIP") (pin "K12") (pinfunction "VDD_CORE10_K12") (pintype "bidirectional"))
    )
    (net (code "408") (name "unconnected-(SIPE-VDD_CORE11-PadL6)") (class "Default")
      (node (ref "SIP") (pin "L6") (pinfunction "VDD_CORE11_L6") (pintype "bidirectional"))
    )
    (net (code "409") (name "unconnected-(SIPE-VDD_CORE12-PadL7)") (class "Default")
      (node (ref "SIP") (pin "L7") (pinfunction "VDD_CORE12_L7") (pintype "bidirectional"))
    )
    (net (code "410") (name "unconnected-(SIPE-VDD_CORE13-PadL8)") (class "Default")
      (node (ref "SIP") (pin "L8") (pinfunction "VDD_CORE13_L8") (pintype "bidirectional"))
    )
    (net (code "411") (name "unconnected-(SIPE-VDD_CORE14-PadL9)") (class "Default")
      (node (ref "SIP") (pin "L9") (pinfunction "VDD_CORE14_L9") (pintype "bidirectional"))
    )
    (net (code "412") (name "unconnected-(SIPE-VDD_CORE15-PadM11)") (class "Default")
      (node (ref "SIP") (pin "M11") (pinfunction "VDD_CORE15_M11") (pintype "bidirectional"))
    )
    (net (code "413") (name "unconnected-(SIPE-VDD_CORE16-PadM13)") (class "Default")
      (node (ref "SIP") (pin "M13") (pinfunction "VDD_CORE16_M13") (pintype "bidirectional"))
    )
    (net (code "414") (name "unconnected-(SIPE-VDD_CORE17-PadN8)") (class "Default")
      (node (ref "SIP") (pin "N8") (pinfunction "VDD_CORE17_N8") (pintype "bidirectional"))
    )
    (net (code "415") (name "unconnected-(SIPE-VDD_CORE18-PadN9)") (class "Default")
      (node (ref "SIP") (pin "N9") (pinfunction "VDD_CORE18_N9") (pintype "bidirectional"))
    )
    (net (code "416") (name "unconnected-(SIPE-VDD_CORE19-PadN12)") (class "Default")
      (node (ref "SIP") (pin "N12") (pinfunction "VDD_CORE19_N12") (pintype "bidirectional"))
    )
    (net (code "417") (name "unconnected-(SIPE-VDD_CORE20-PadN13)") (class "Default")
      (node (ref "SIP") (pin "N13") (pinfunction "VDD_CORE20_N13") (pintype "bidirectional"))
    )
    (net (code "418") (name "unconnected-(SIPE-VDD_MPU0-PadF10)") (class "Default")
      (node (ref "SIP") (pin "F10") (pinfunction "VDD_MPU0_F10") (pintype "bidirectional"))
    )
    (net (code "419") (name "unconnected-(SIPE-VDD_MPU1-PadF11)") (class "Default")
      (node (ref "SIP") (pin "F11") (pinfunction "VDD_MPU1_F11") (pintype "bidirectional"))
    )
    (net (code "420") (name "unconnected-(SIPE-VDD_MPU2-PadF12)") (class "Default")
      (node (ref "SIP") (pin "F12") (pinfunction "VDD_MPU2_F12") (pintype "bidirectional"))
    )
    (net (code "421") (name "unconnected-(SIPE-VDD_MPU3-PadF13)") (class "Default")
      (node (ref "SIP") (pin "F13") (pinfunction "VDD_MPU3_F13") (pintype "bidirectional"))
    )
    (net (code "422") (name "unconnected-(SIPE-VDD_MPU4-PadG13)") (class "Default")
      (node (ref "SIP") (pin "G13") (pinfunction "VDD_MPU4_G13") (pintype "bidirectional"))
    )
    (net (code "423") (name "unconnected-(SIPE-VDD_MPU5-PadH13)") (class "Default")
      (node (ref "SIP") (pin "H13") (pinfunction "VDD_MPU5_H13") (pintype "bidirectional"))
    )
    (net (code "424") (name "unconnected-(SIPE-VDD_MPU6-PadJ13)") (class "Default")
      (node (ref "SIP") (pin "J13") (pinfunction "VDD_MPU6_J13") (pintype "bidirectional"))
    )
    (net (code "425") (name "unconnected-(SIPE-VDD_MPU_MON-PadA2)") (class "Default")
      (node (ref "SIP") (pin "A2") (pinfunction "VDD_MPU_MON_A2") (pintype "bidirectional"))
    )
    (net (code "426") (name "unconnected-(SIPE-VDD_PLL1-PadE7)") (class "Default")
      (node (ref "SIP") (pin "E7") (pinfunction "VDD_PLL1_E7") (pintype "bidirectional"))
    )
    (net (code "427") (name "unconnected-(SIPE-VDD_PLL2-PadH15)") (class "Default")
      (node (ref "SIP") (pin "H15") (pinfunction "VDD_PLL2_H15") (pintype "bidirectional"))
    )
    (net (code "428") (name "unconnected-(SIPE-VDD_PLL3-PadR10)") (class "Default")
      (node (ref "SIP") (pin "R10") (pinfunction "VDD_PLL3_R10") (pintype "bidirectional"))
    )
    (net (code "429") (name "unconnected-(SIPE-VDD_PLL4-PadR11)") (class "Default")
      (node (ref "SIP") (pin "R11") (pinfunction "VDD_PLL4_R11") (pintype "bidirectional"))
    )
    (net (code "430") (name "unconnected-(SIPE-VDD_RTC1-PadD7)") (class "Default")
      (node (ref "SIP") (pin "D7") (pinfunction "VDD_RTC1_D7") (pintype "bidirectional"))
    )
    (net (code "431") (name "unconnected-(SIPE-VDD_RTC2-PadE6)") (class "Default")
      (node (ref "SIP") (pin "E6") (pinfunction "VDD_RTC2_E6") (pintype "bidirectional"))
    )
    (net (code "432") (name "unconnected-(SIPE-VDD_RTC4-PadF9)") (class "Default")
      (node (ref "SIP") (pin "F9") (pinfunction "VDD_RTC4_F9") (pintype "bidirectional"))
    )
    (net (code "433") (name "unconnected-(SIPE-VDD_RTC5-PadK13)") (class "Default")
      (node (ref "SIP") (pin "K13") (pinfunction "VDD_RTC5_K13") (pintype "bidirectional"))
    )
    (net (code "434") (name "unconnected-(SIPE-VDD_RTC6-PadN6)") (class "Default")
      (node (ref "SIP") (pin "N6") (pinfunction "VDD_RTC6_N6") (pintype "bidirectional"))
    )
    (net (code "435") (name "unconnected-(SIPE-VDD_RTC7-PadP9)") (class "Default")
      (node (ref "SIP") (pin "P9") (pinfunction "VDD_RTC7_P9") (pintype "bidirectional"))
    )
    (net (code "436") (name "unconnected-(SIPE-VDD_RTC8-PadP14)") (class "Default")
      (node (ref "SIP") (pin "P14") (pinfunction "VDD_RTC8_P14") (pintype "bidirectional"))
    )
    (net (code "437") (name "unconnected-(SIPE-VPP-PadM5)") (class "Default")
      (node (ref "SIP") (pin "M5") (pinfunction "VPP_M5") (pintype "bidirectional"))
    )
    (net (code "438") (name "unconnected-(U3-NC-Pad5)") (class "Default")
      (node (ref "U3") (pin "5") (pinfunction "NC_5") (pintype "bidirectional"))
    )
    (net (code "439") (name "unconnected-(U4-ID-Pad3)") (class "Default")
      (node (ref "U4") (pin "3") (pinfunction "ID_3") (pintype "bidirectional"))
    )
    (net (code "440") (name "unconnected-(U4-NC-Pad5)") (class "Default")
      (node (ref "U4") (pin "5") (pinfunction "NC_5") (pintype "bidirectional"))
    )
    (net (code "441") (name "unconnected-(U6-NC-Pad1)") (class "Default")
      (node (ref "U6") (pin "1") (pinfunction "NC_1") (pintype "passive"))
    )
    (net (code "442") (name "unconnected-(U7-BT_UART_DBG-Pad43)") (class "Default")
      (node (ref "U7") (pin "43") (pinfunction "BT_UART_DBG_43") (pintype "bidirectional"))
    )
    (net (code "443") (name "unconnected-(U7-GPIO1-Pad27)") (class "Default")
      (node (ref "U7") (pin "27") (pinfunction "GPIO1_27") (pintype "bidirectional"))
    )
    (net (code "444") (name "unconnected-(U7-GPIO2-Pad26)") (class "Default")
      (node (ref "U7") (pin "26") (pinfunction "GPIO2_26") (pintype "bidirectional"))
    )
    (net (code "445") (name "unconnected-(U7-GPIO4-Pad25)") (class "Default")
      (node (ref "U7") (pin "25") (pinfunction "GPIO4_25") (pintype "bidirectional"))
    )
    (net (code "446") (name "unconnected-(U7-GPIO9-Pad3)") (class "Default")
      (node (ref "U7") (pin "3") (pinfunction "GPIO9_3") (pintype "bidirectional"))
    )
    (net (code "447") (name "unconnected-(U7-GPIO10-Pad4)") (class "Default")
      (node (ref "U7") (pin "4") (pinfunction "GPIO10_4") (pintype "bidirectional"))
    )
    (net (code "448") (name "unconnected-(U7-GPIO11-Pad2)") (class "Default")
      (node (ref "U7") (pin "2") (pinfunction "GPIO11_2") (pintype "bidirectional"))
    )
    (net (code "449") (name "unconnected-(U7-GPIO12-Pad5)") (class "Default")
      (node (ref "U7") (pin "5") (pinfunction "GPIO12_5") (pintype "bidirectional"))
    )
    (net (code "450") (name "unconnected-(U7-RESERVED1-Pad21)") (class "Default")
      (node (ref "U7") (pin "21") (pinfunction "RESERVED1_21") (pintype "bidirectional"))
    )
    (net (code "451") (name "unconnected-(U7-RESERVED2-Pad22)") (class "Default")
      (node (ref "U7") (pin "22") (pinfunction "RESERVED2_22") (pintype "bidirectional"))
    )
    (net (code "452") (name "unconnected-(U7-RESERVED3-Pad62)") (class "Default")
      (node (ref "U7") (pin "62") (pinfunction "RESERVED3_62") (pintype "bidirectional"))
    )
    (net (code "453") (name "unconnected-(U7-WL_UART_DBG-Pad42)") (class "Default")
      (node (ref "U7") (pin "42") (pinfunction "WL_UART_DBG_42") (pintype "bidirectional"))
    )
  )
)
